# RefOsc10MHz_3V0_bga-escaped.net
KiCad netlist of a schematic drawn in EAGLE
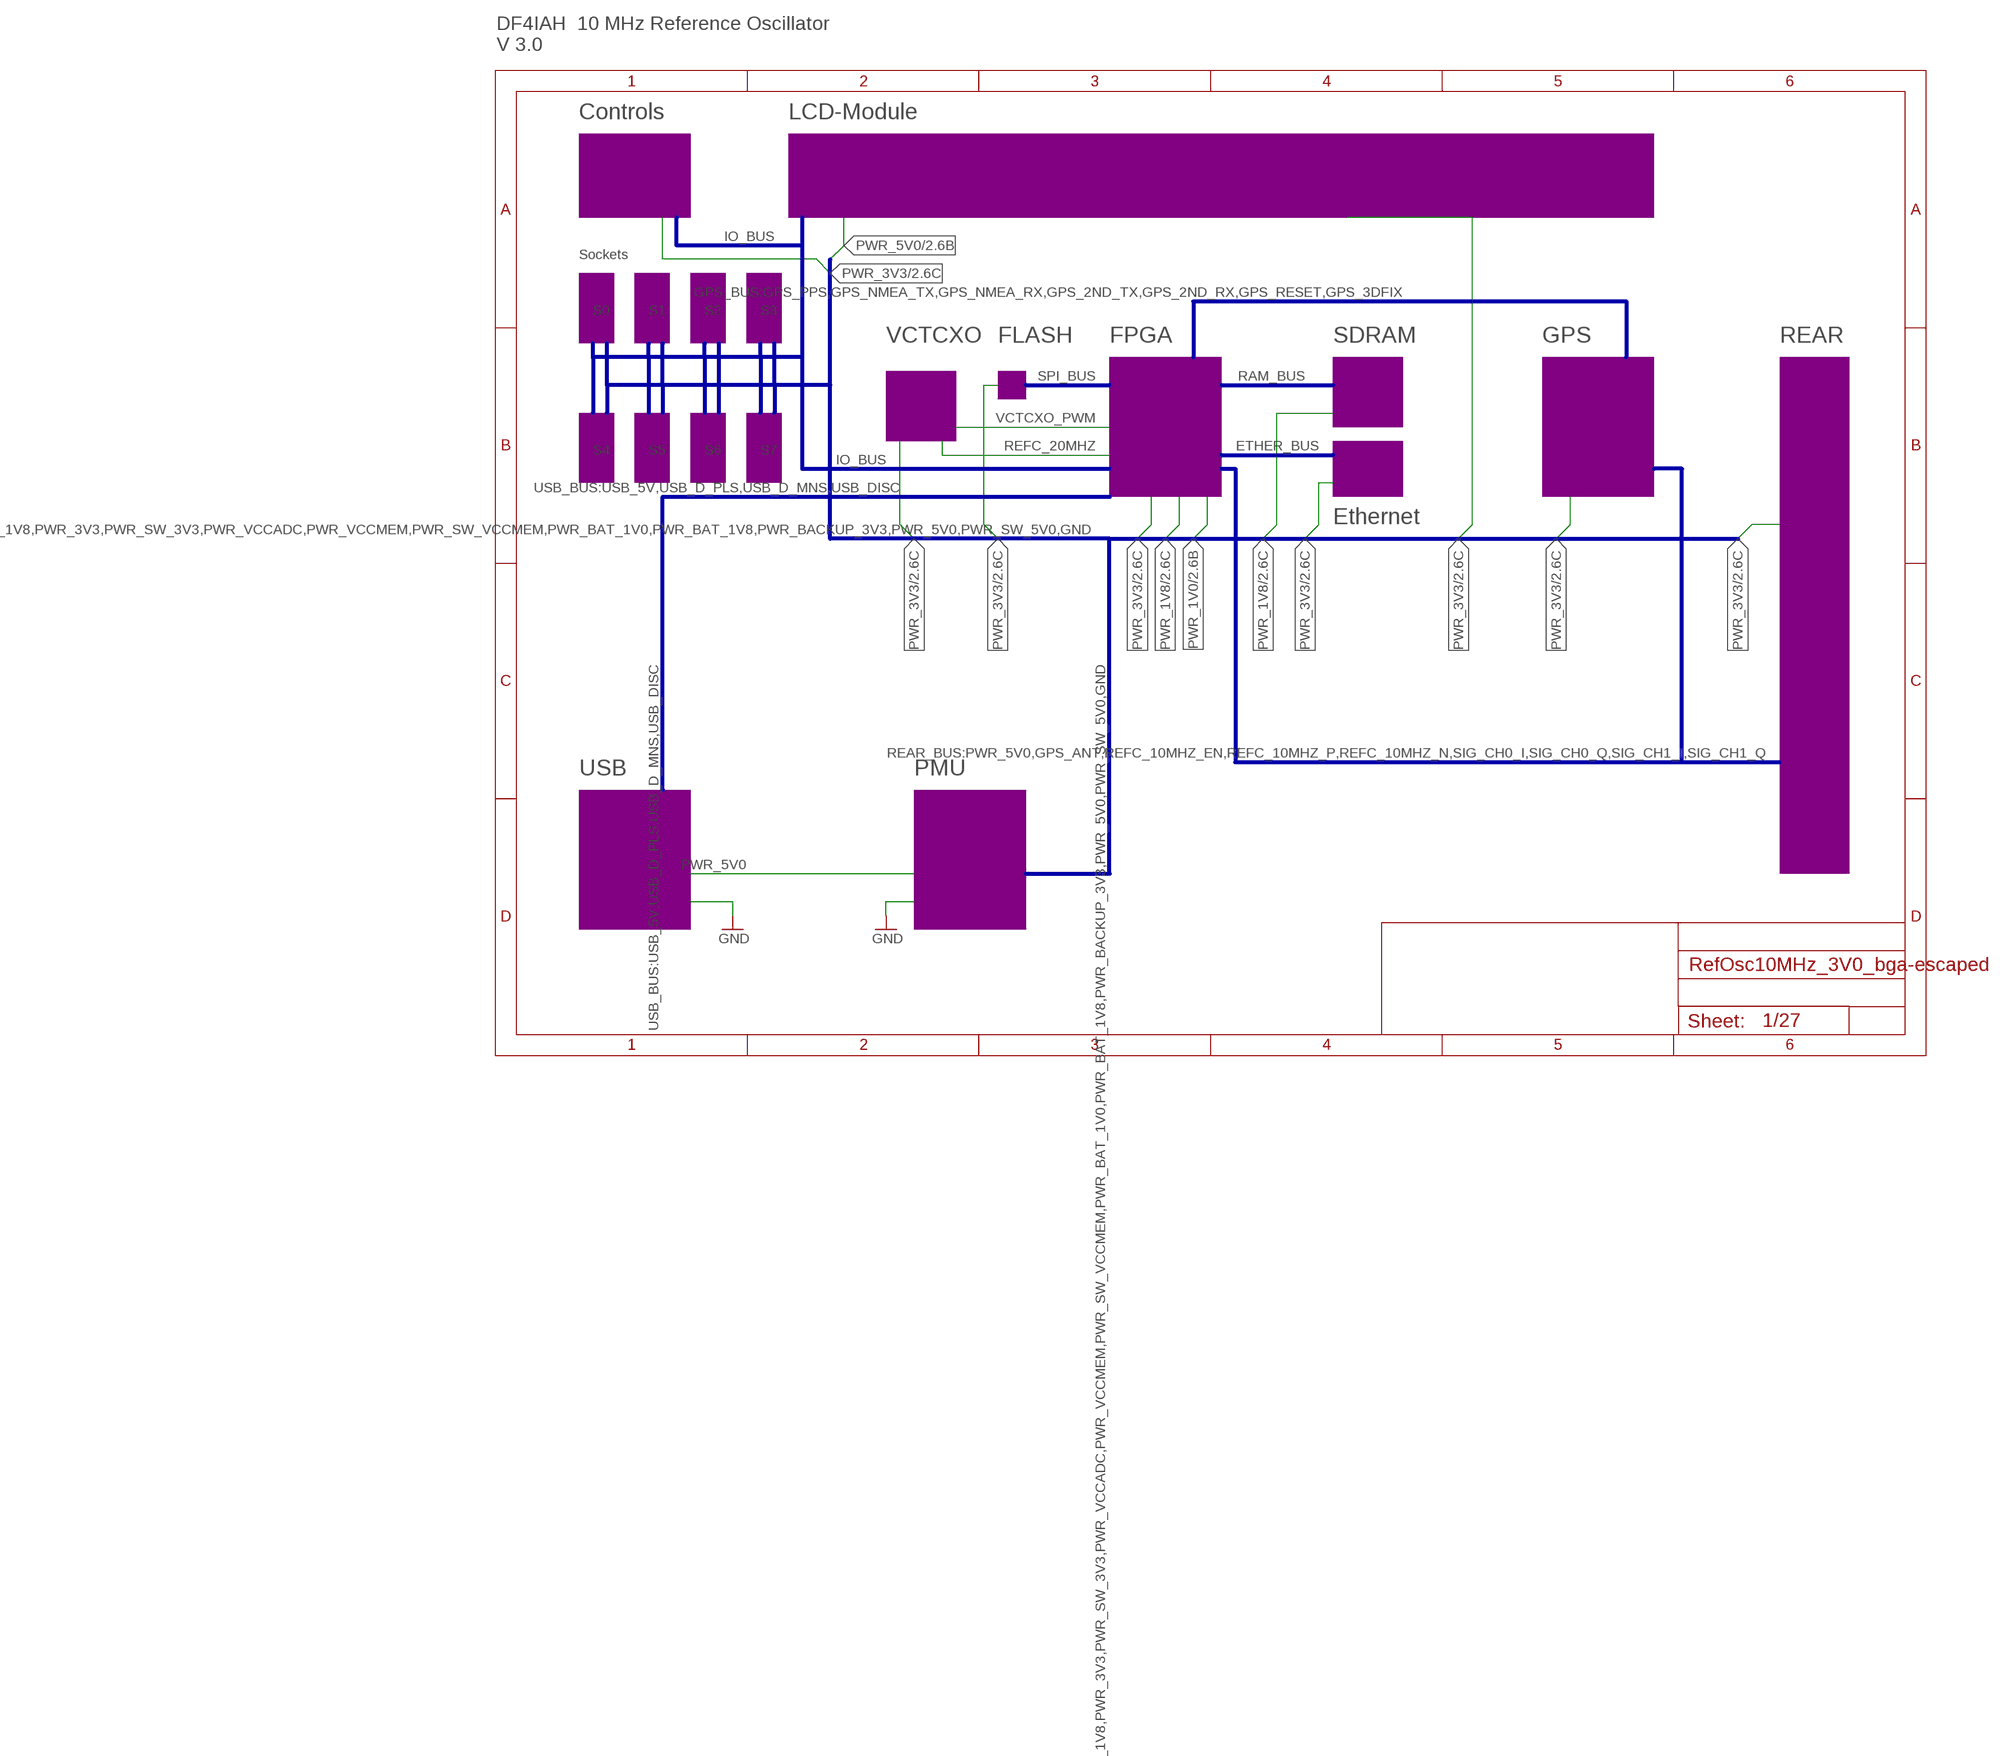
[diagram p0: schematic, sheet 1]
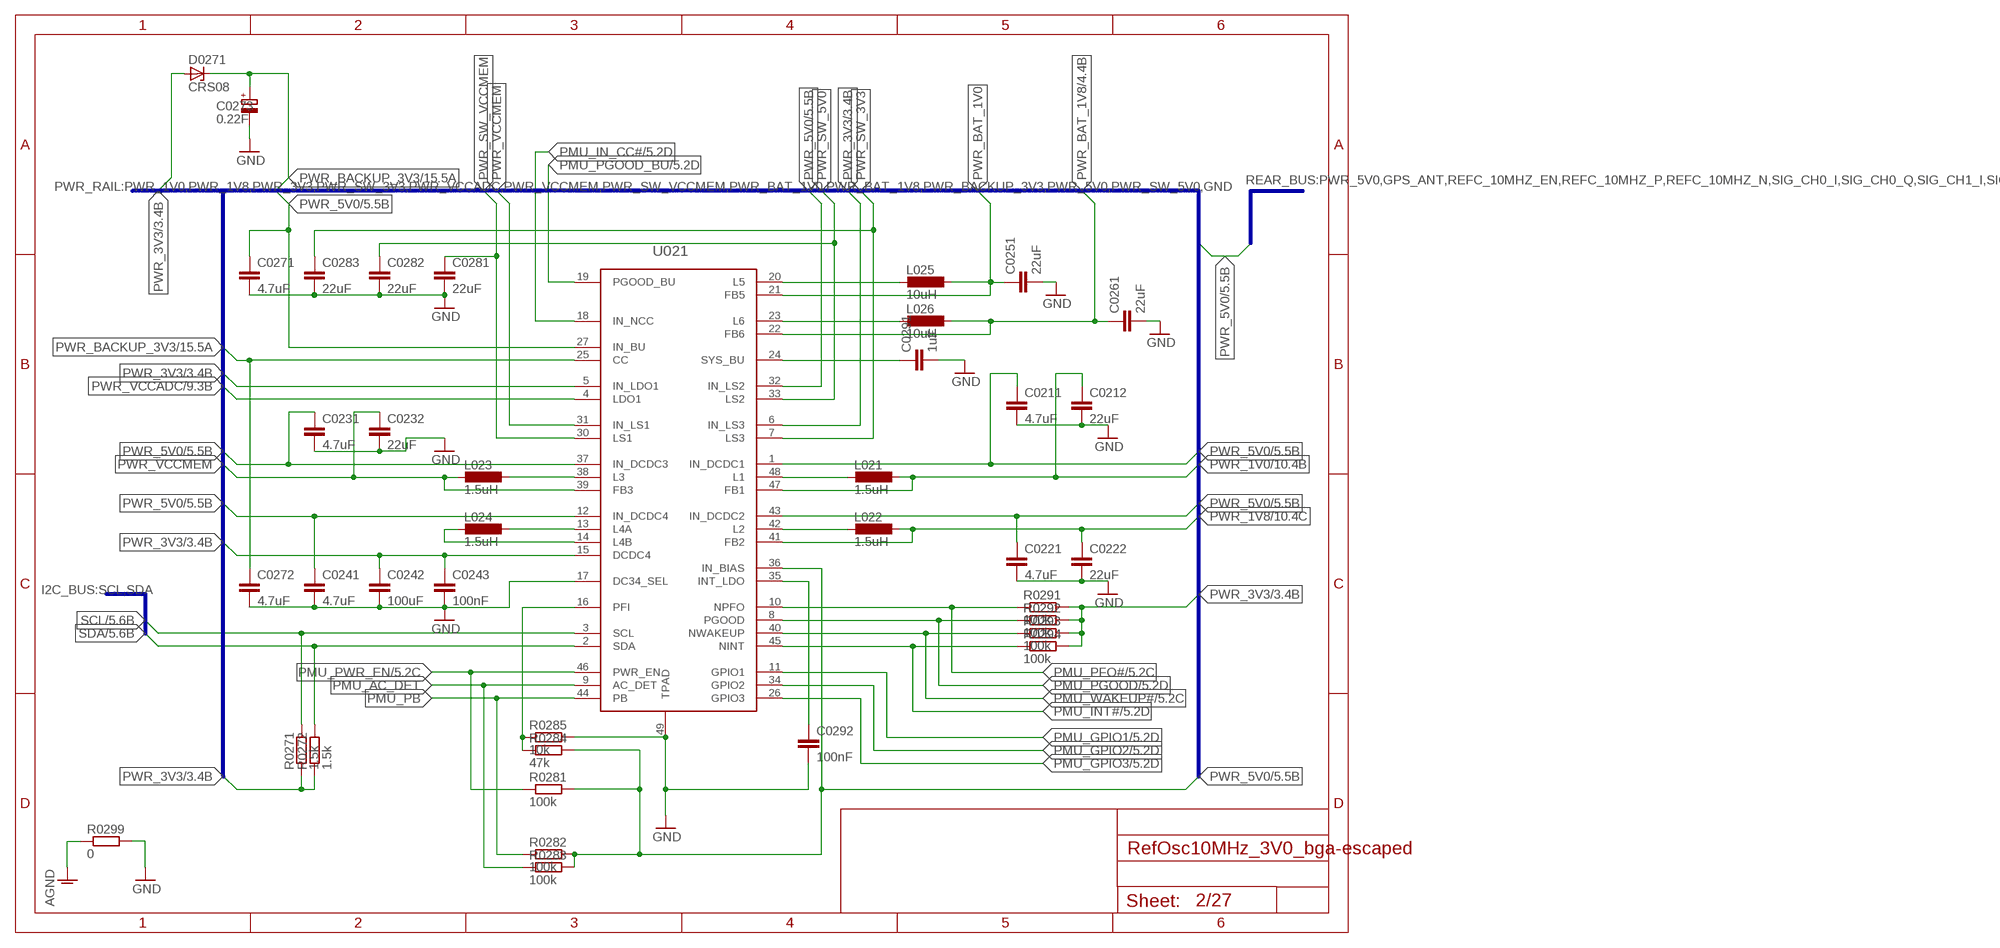
[diagram p1: schematic, sheet 2]
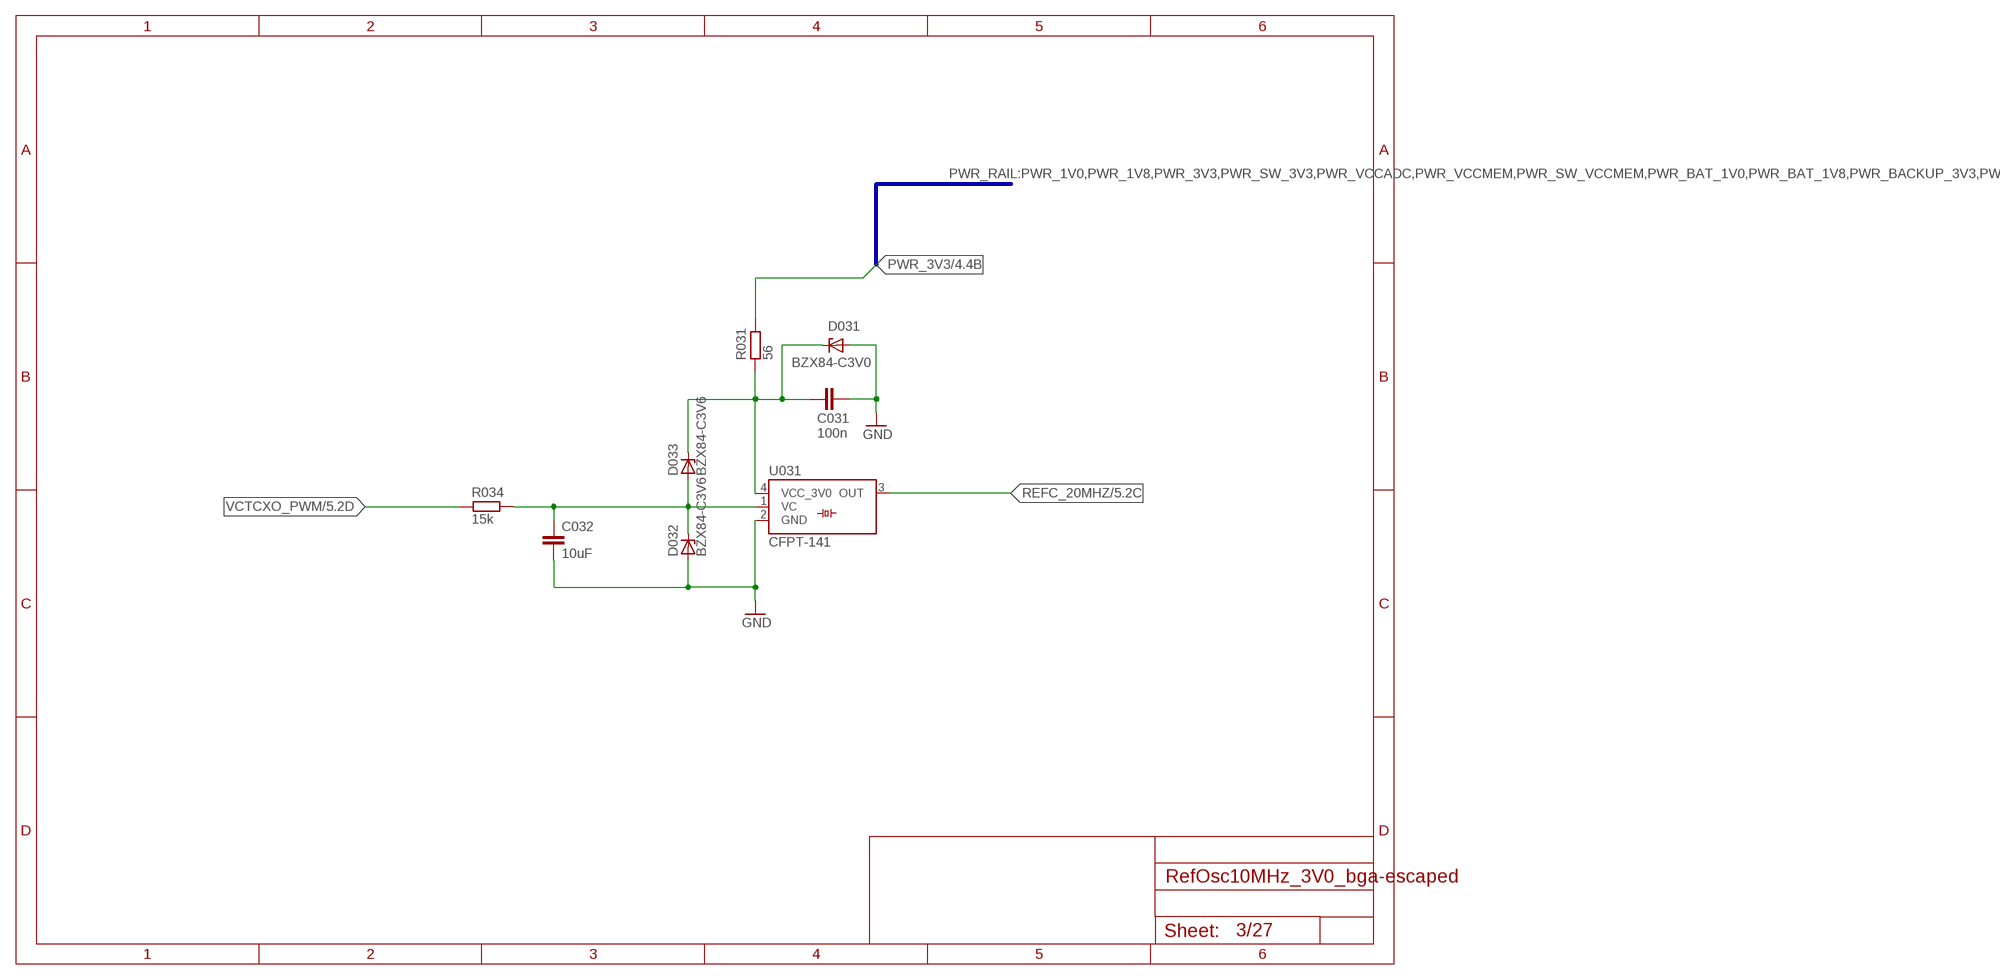
[diagram p2: schematic, sheet 3]
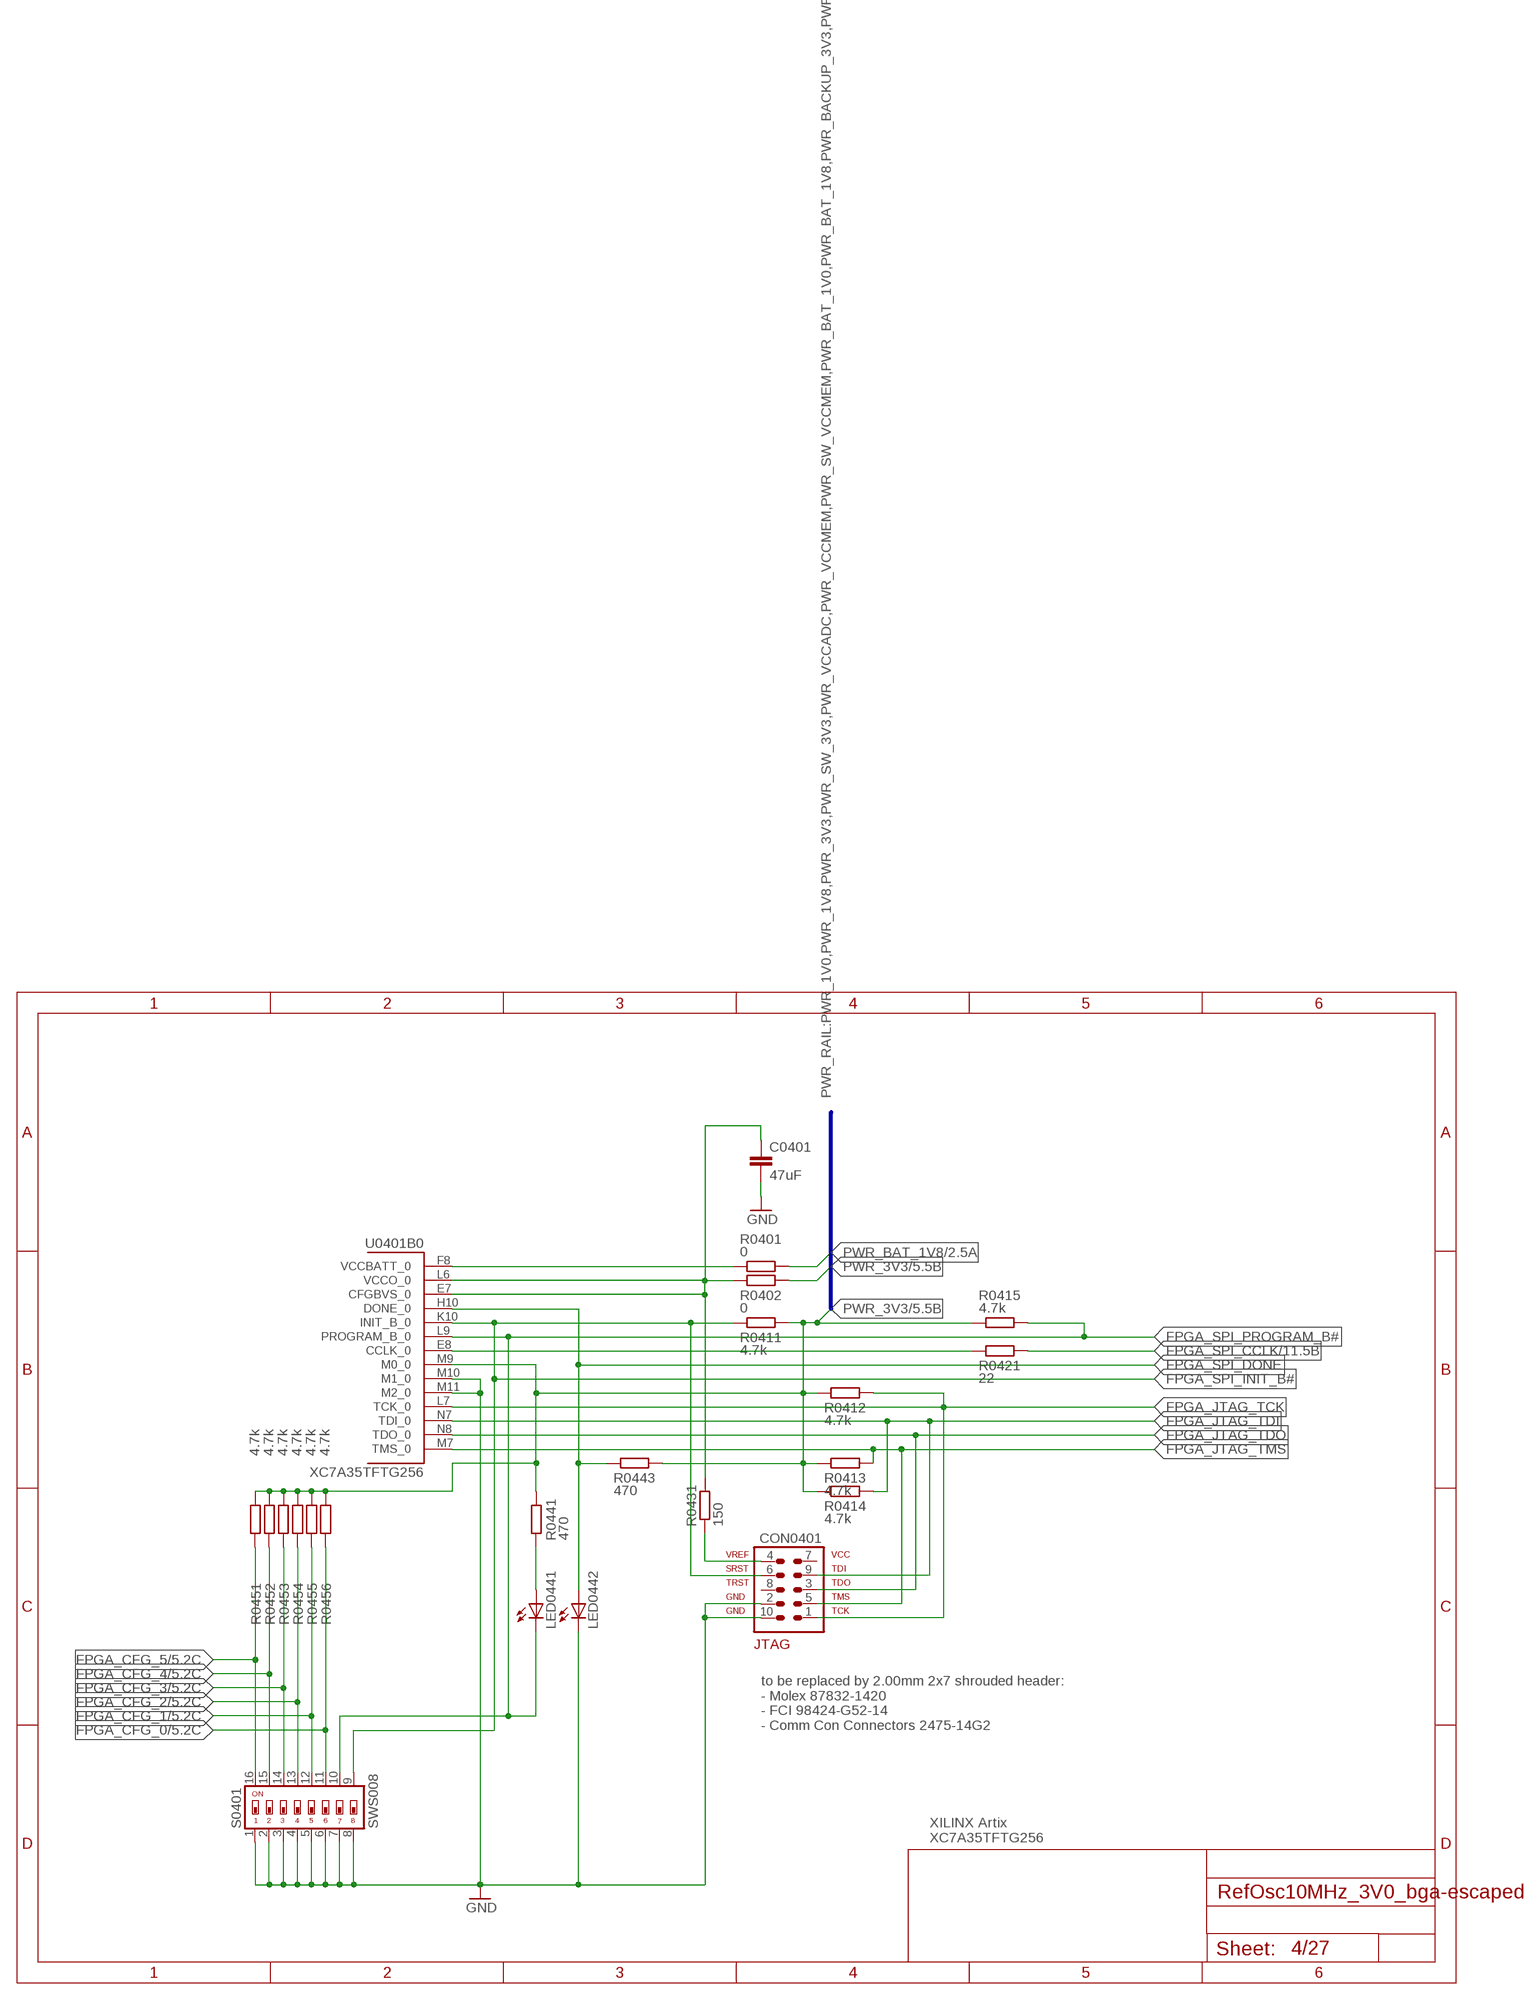
[diagram p3: schematic, sheet 4]
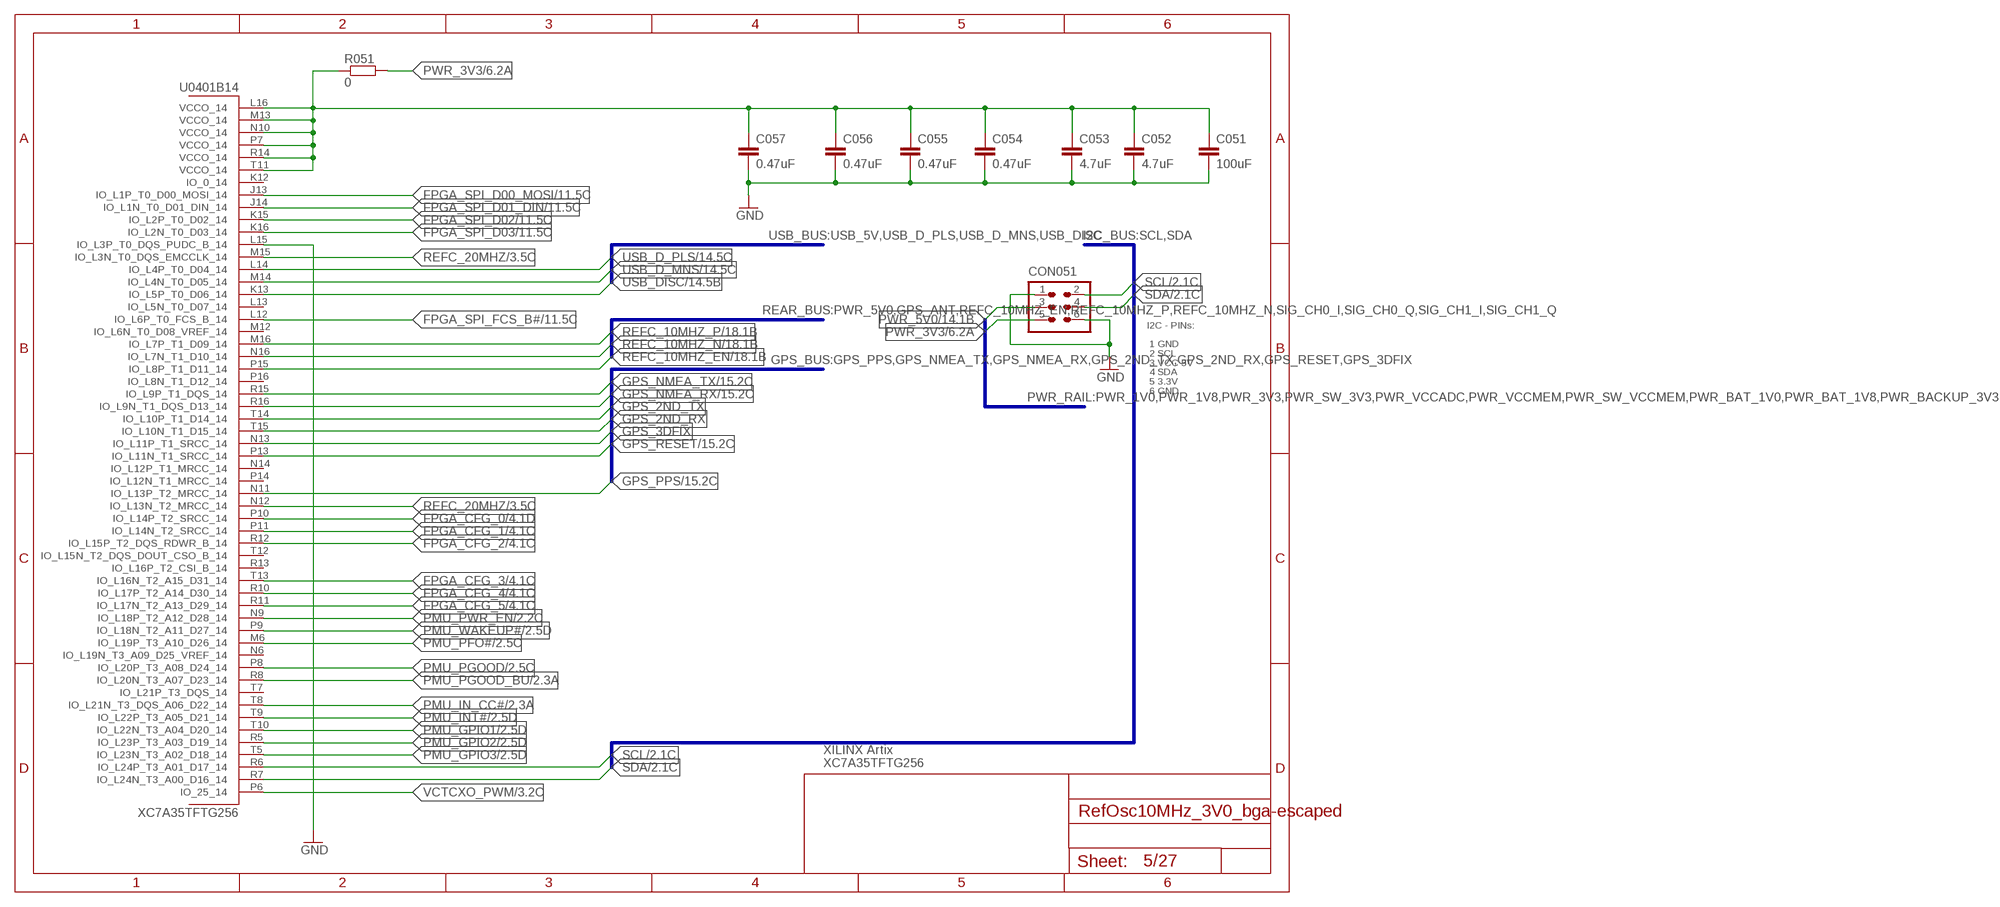
[diagram p4: schematic, sheet 5]
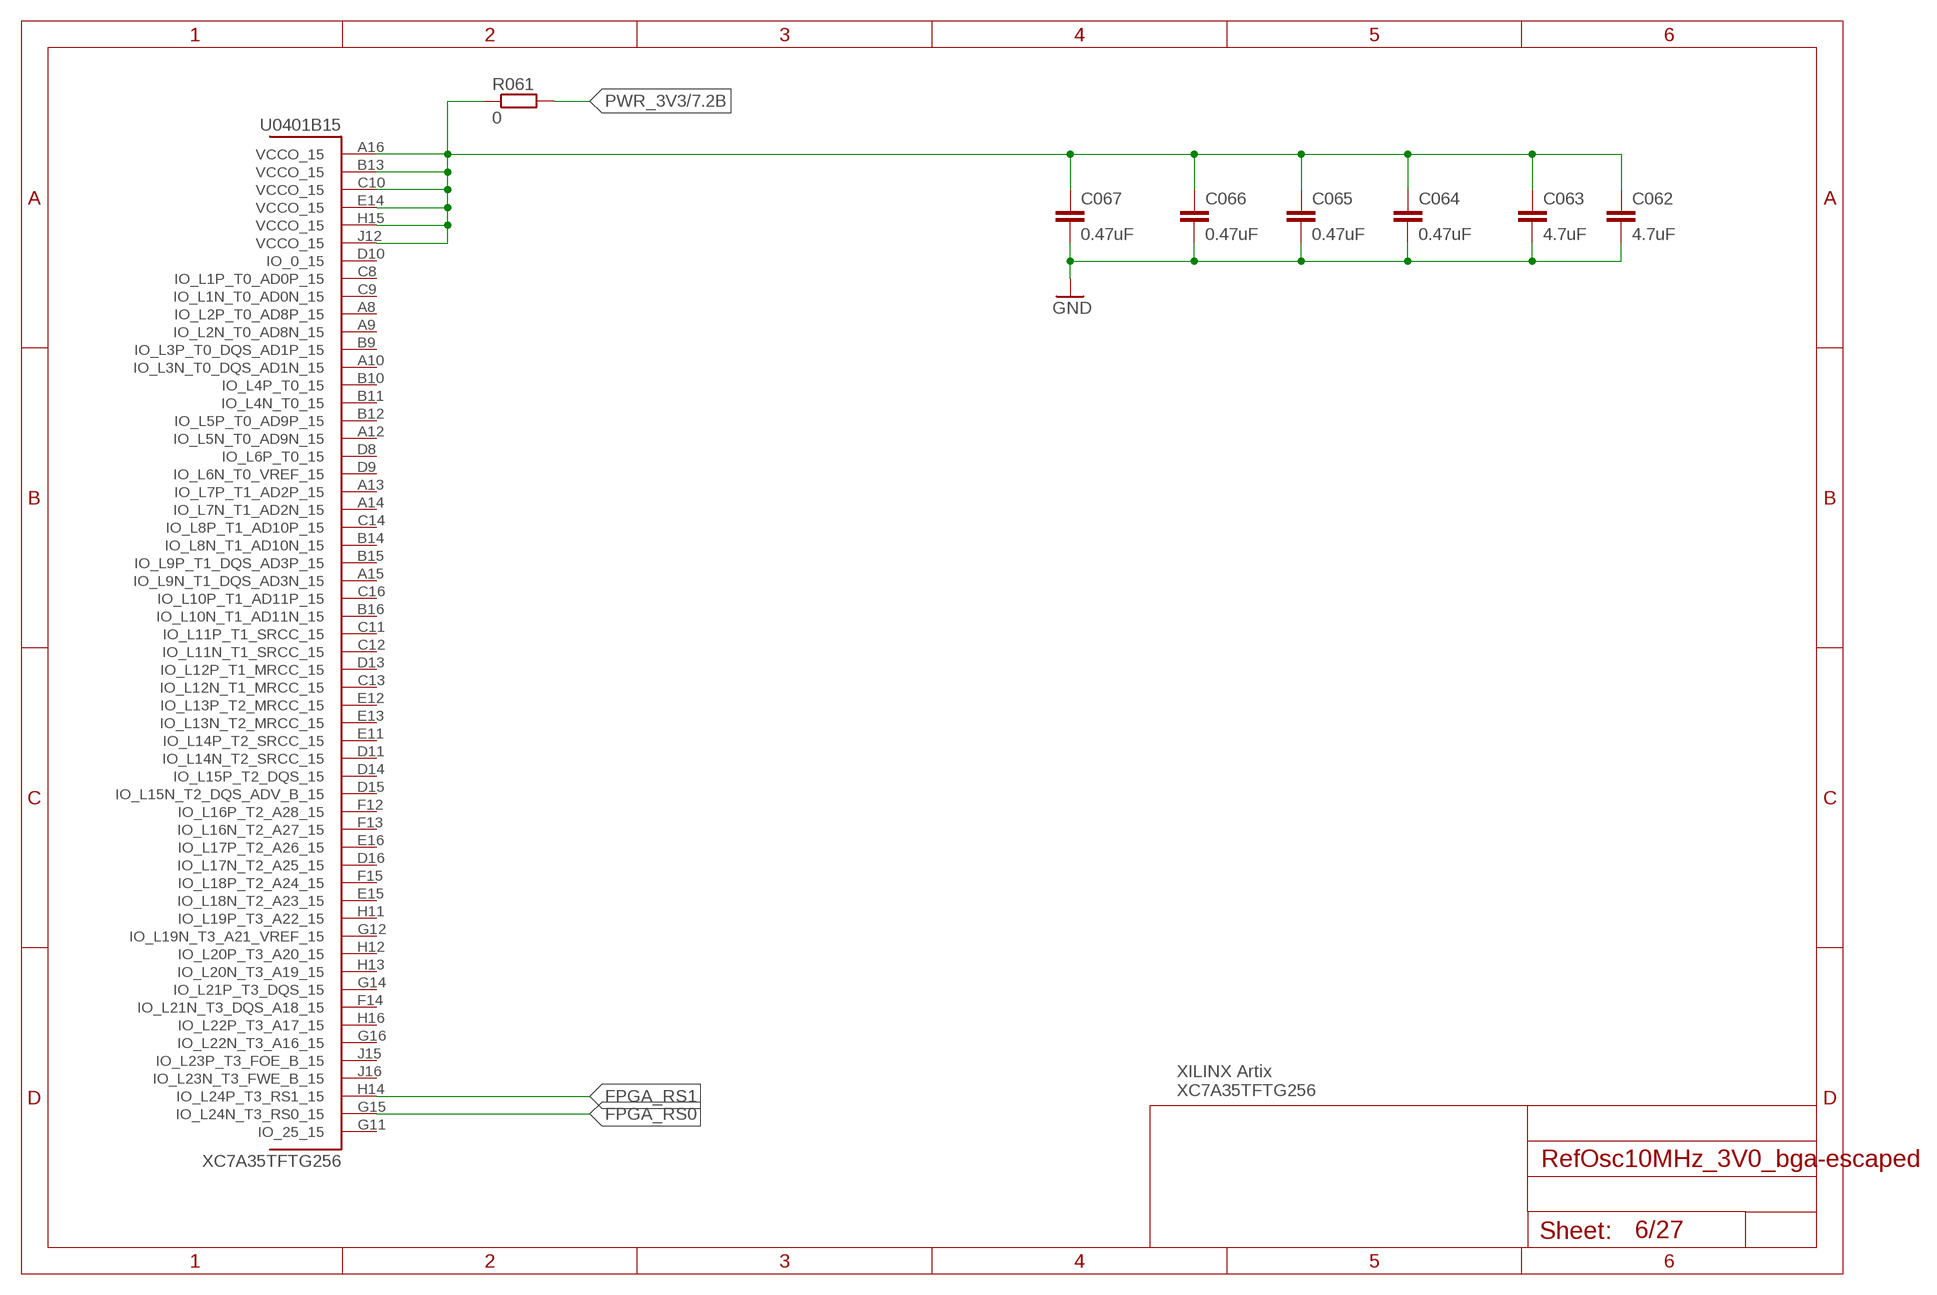
[diagram p5: schematic, sheet 6]
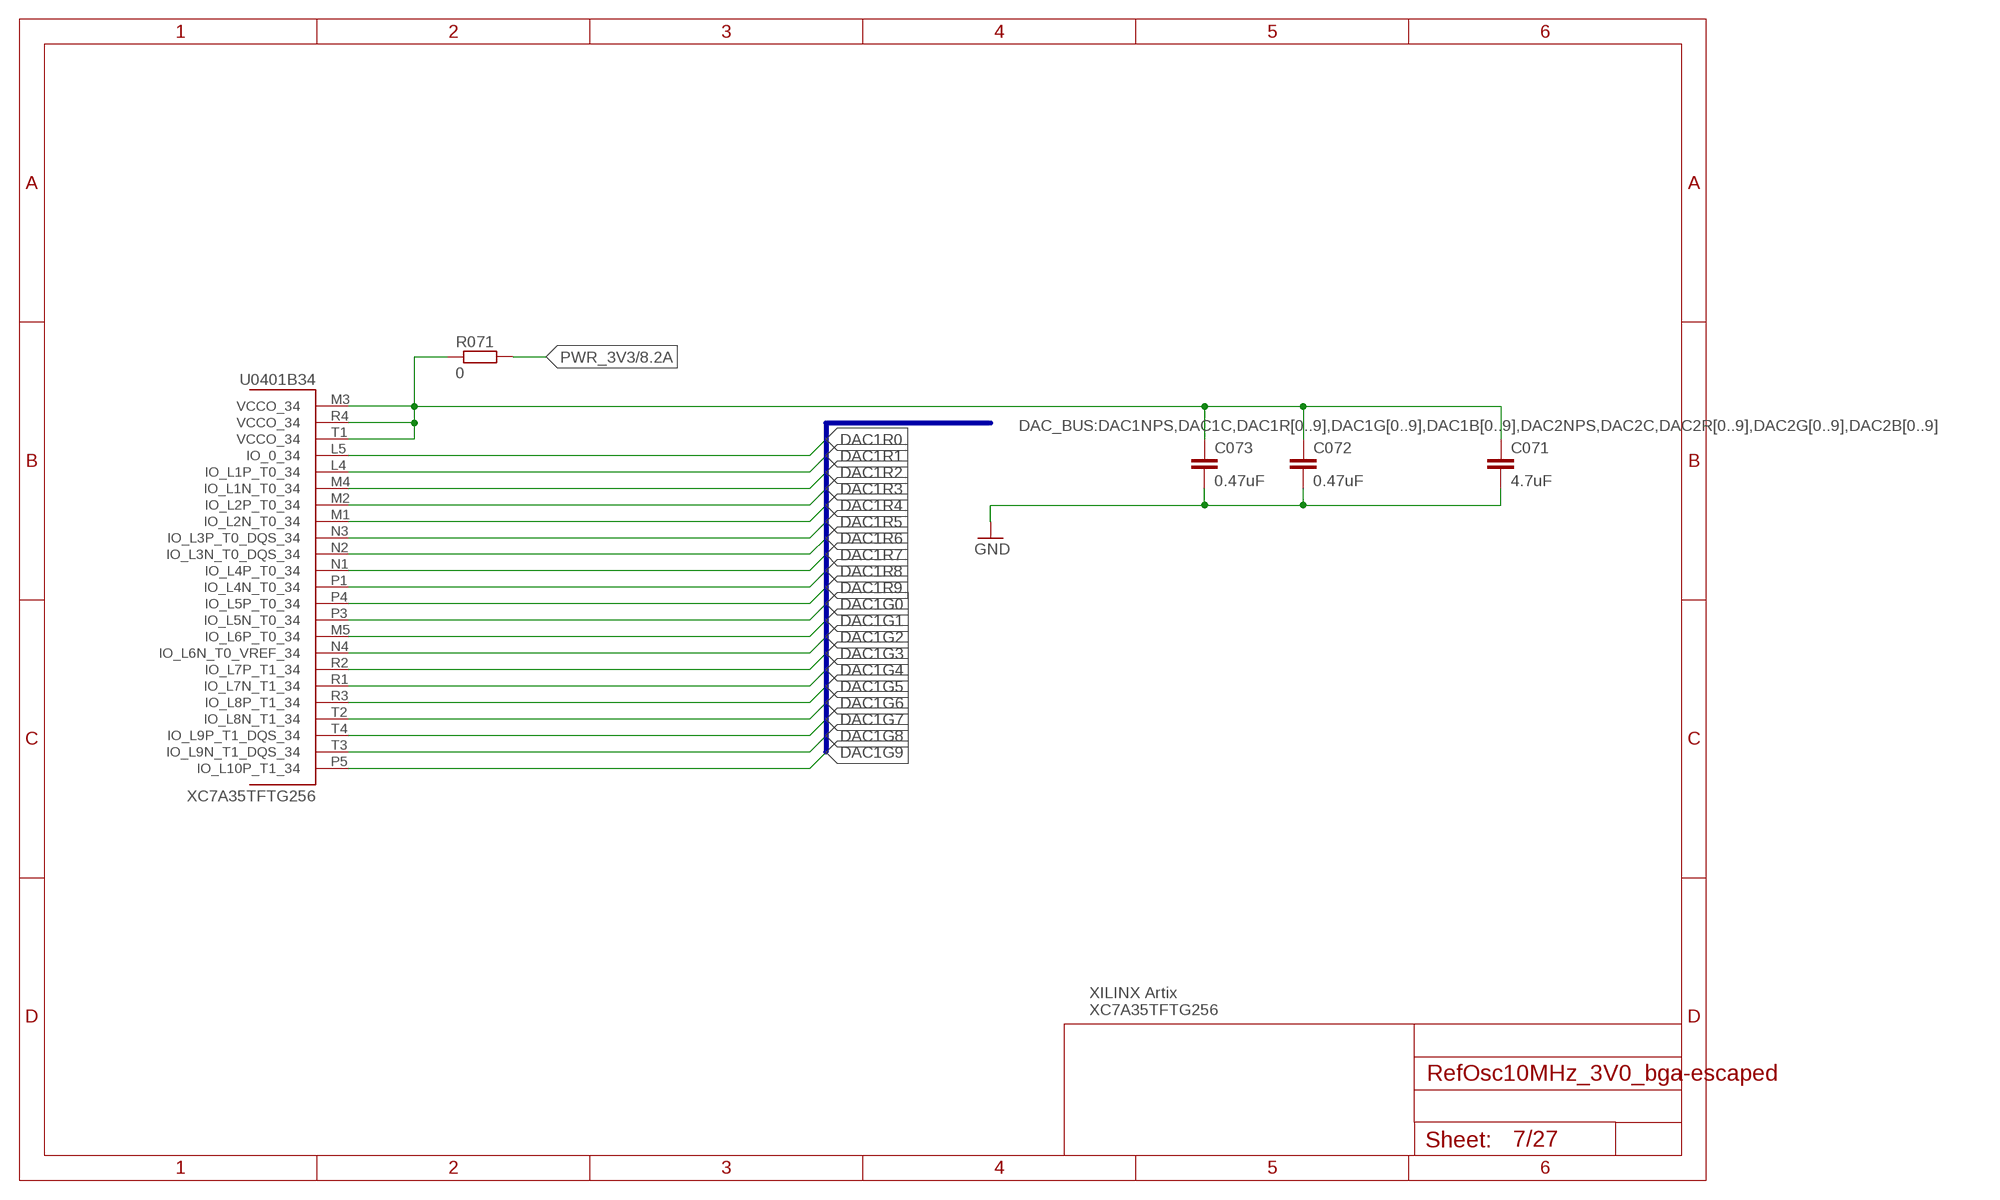
[diagram p6: schematic, sheet 7]
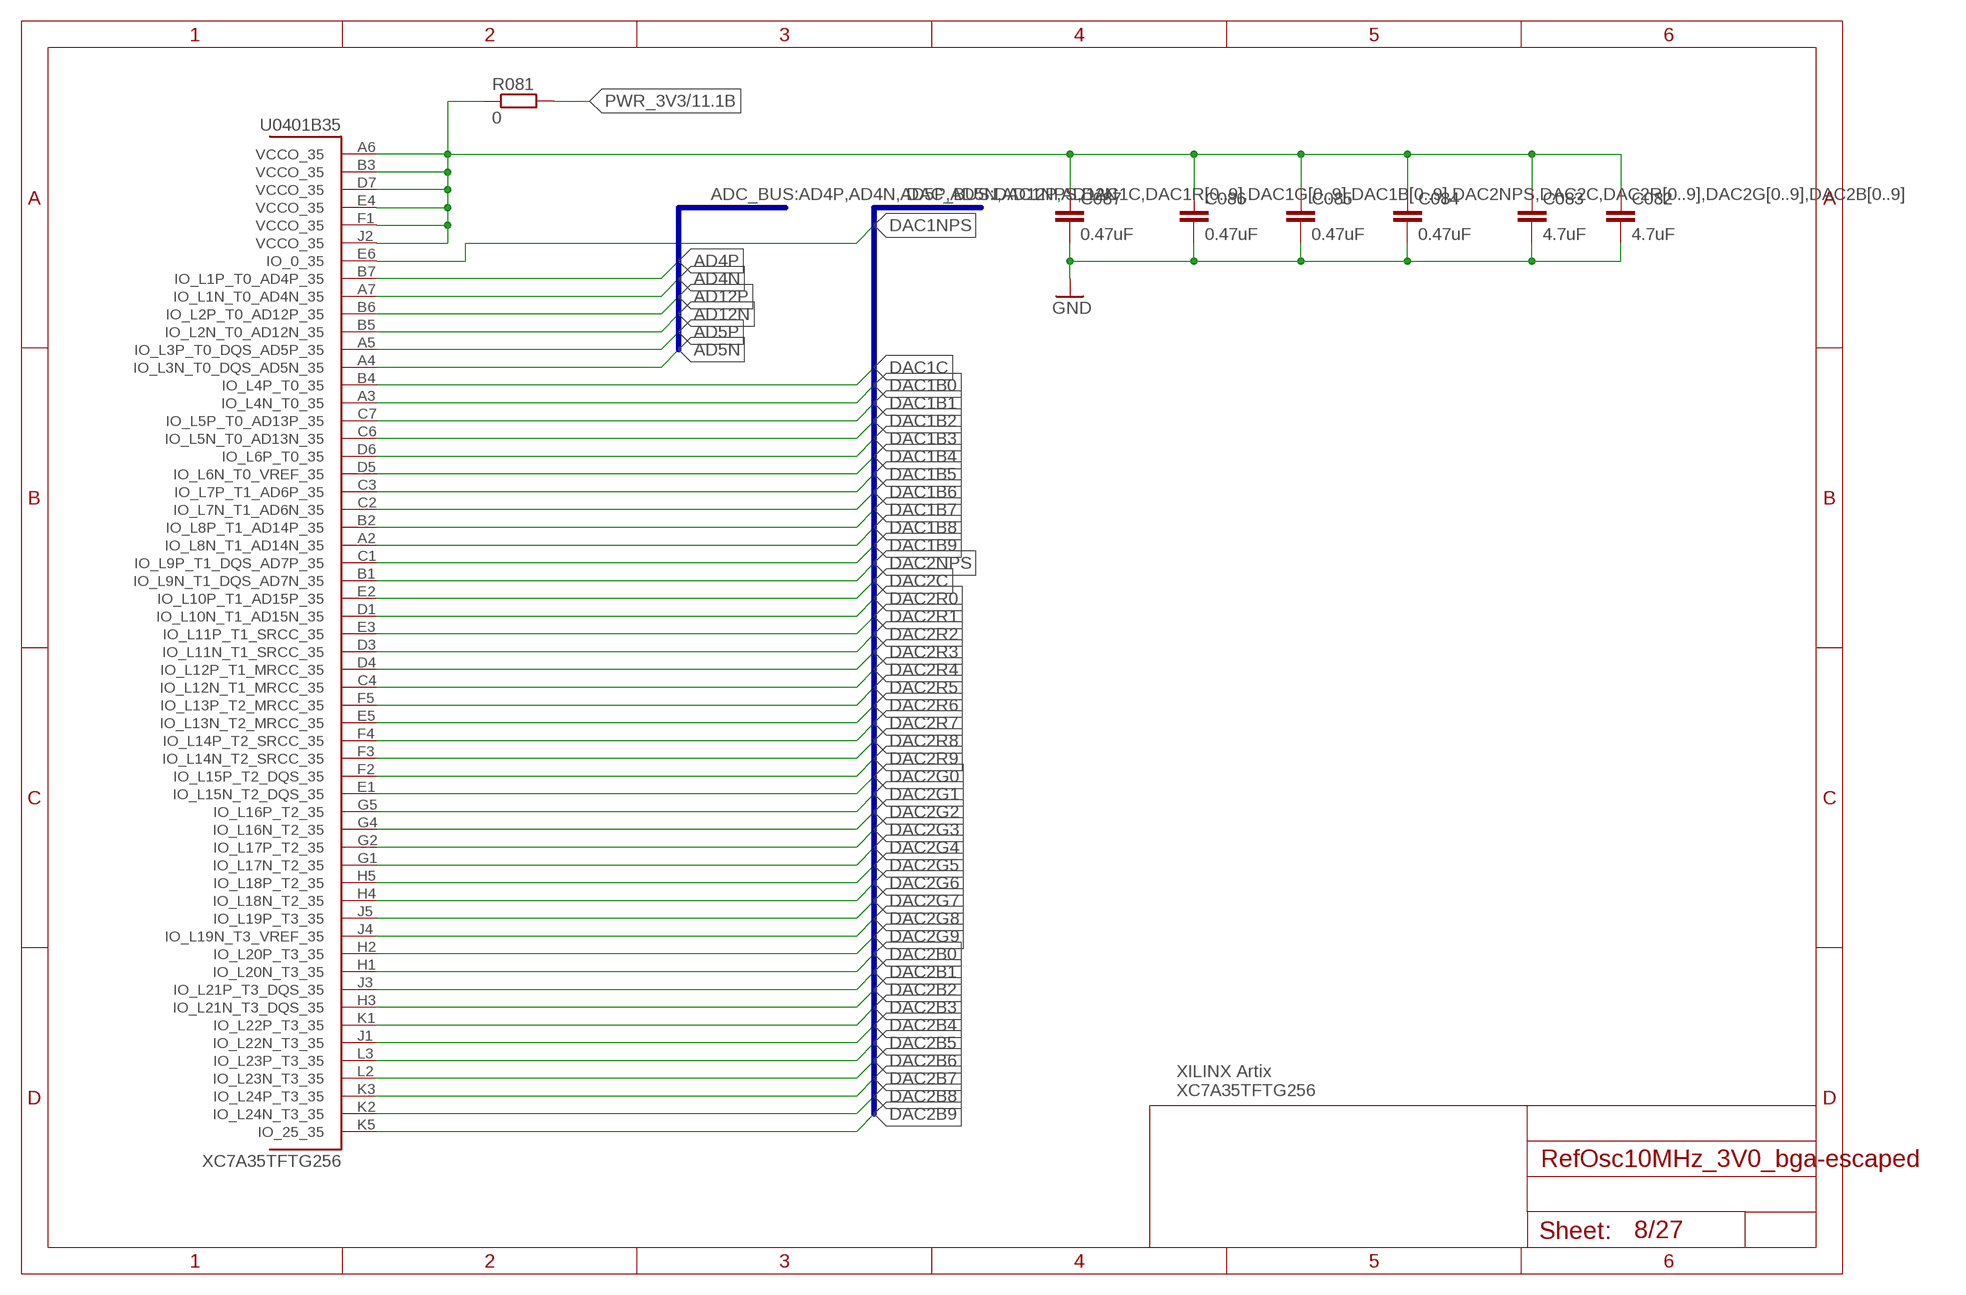
[diagram p7: schematic, sheet 8]
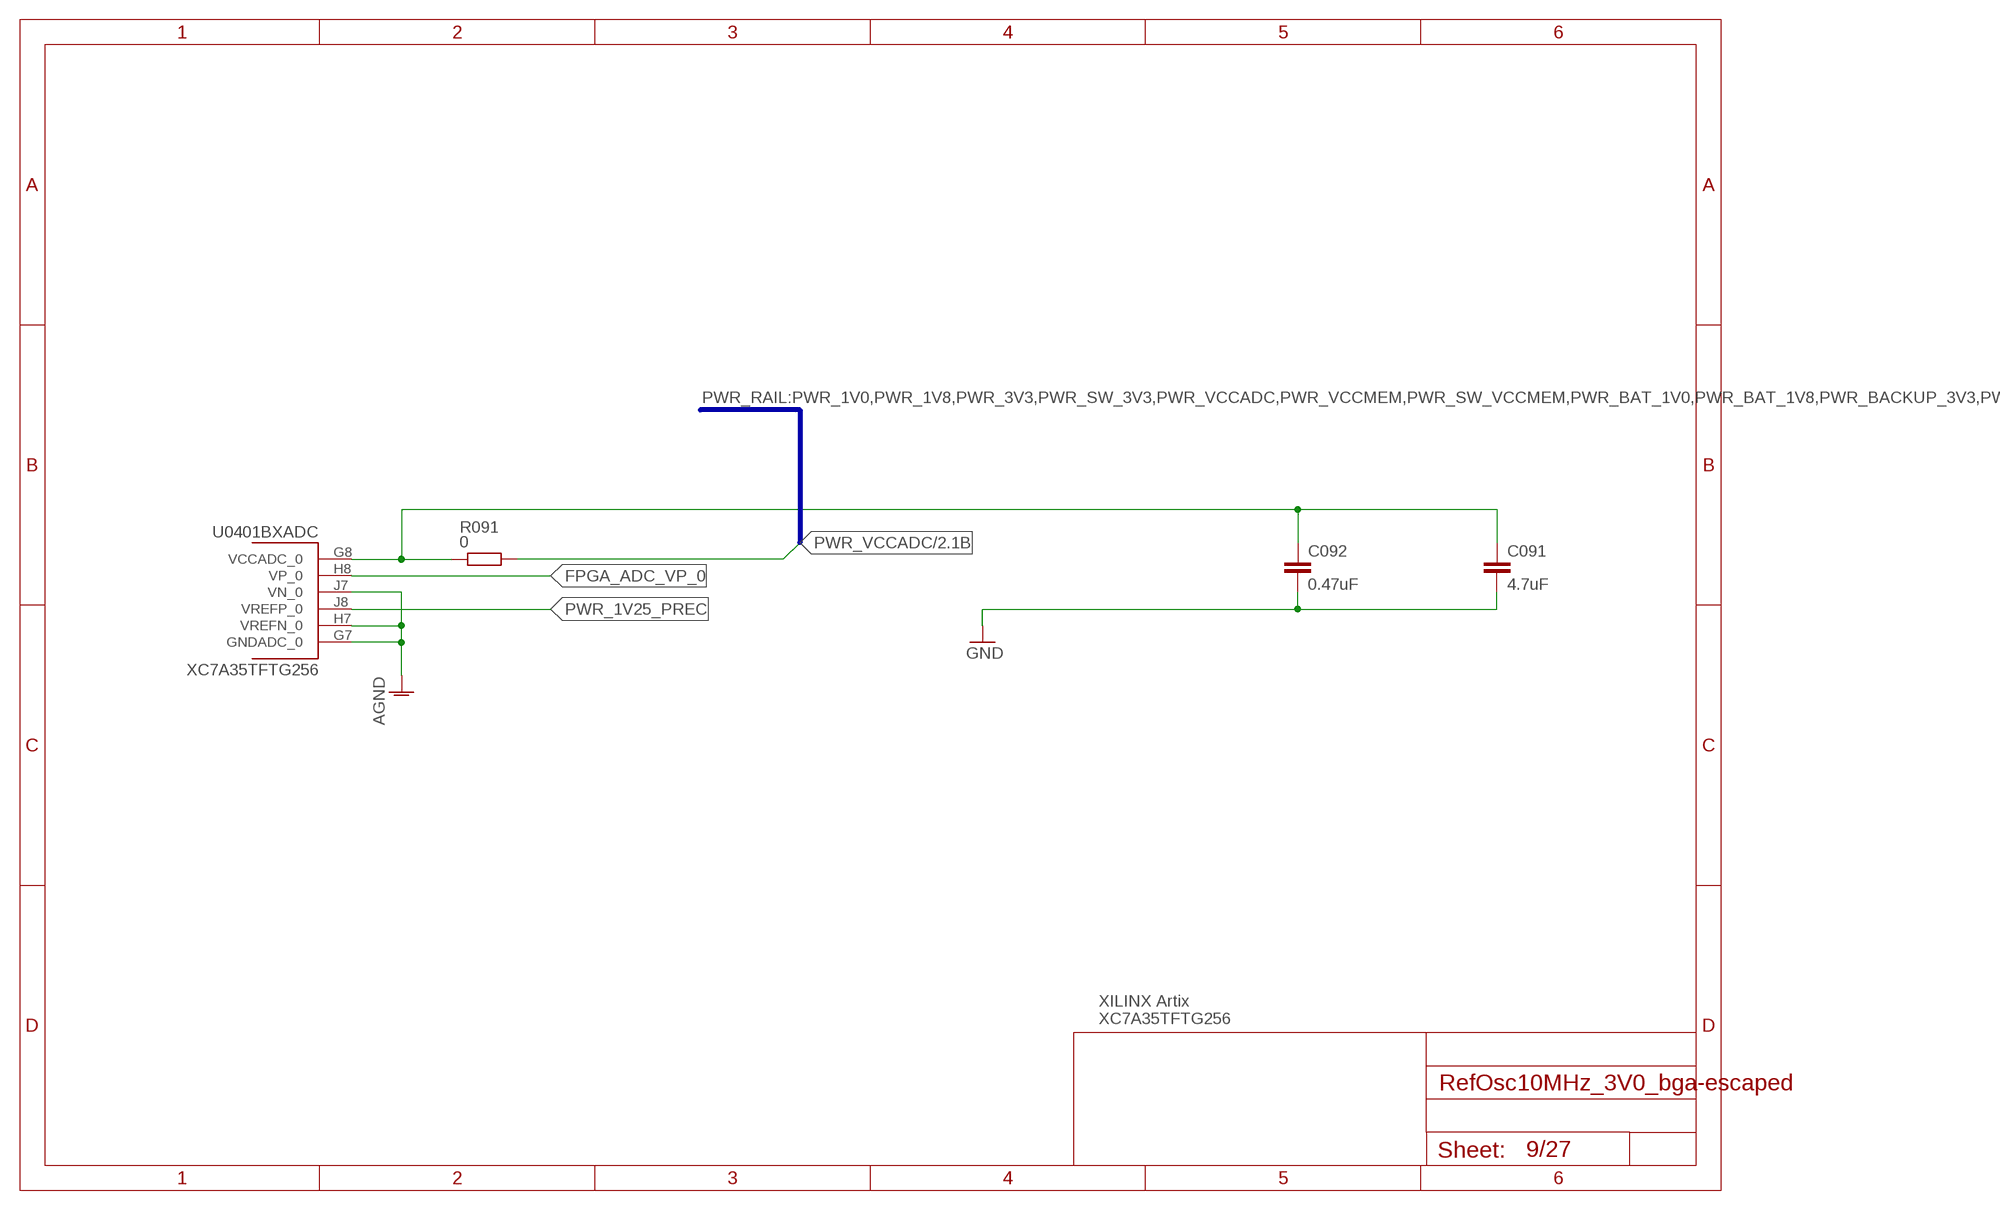
[diagram p8: schematic, sheet 9]
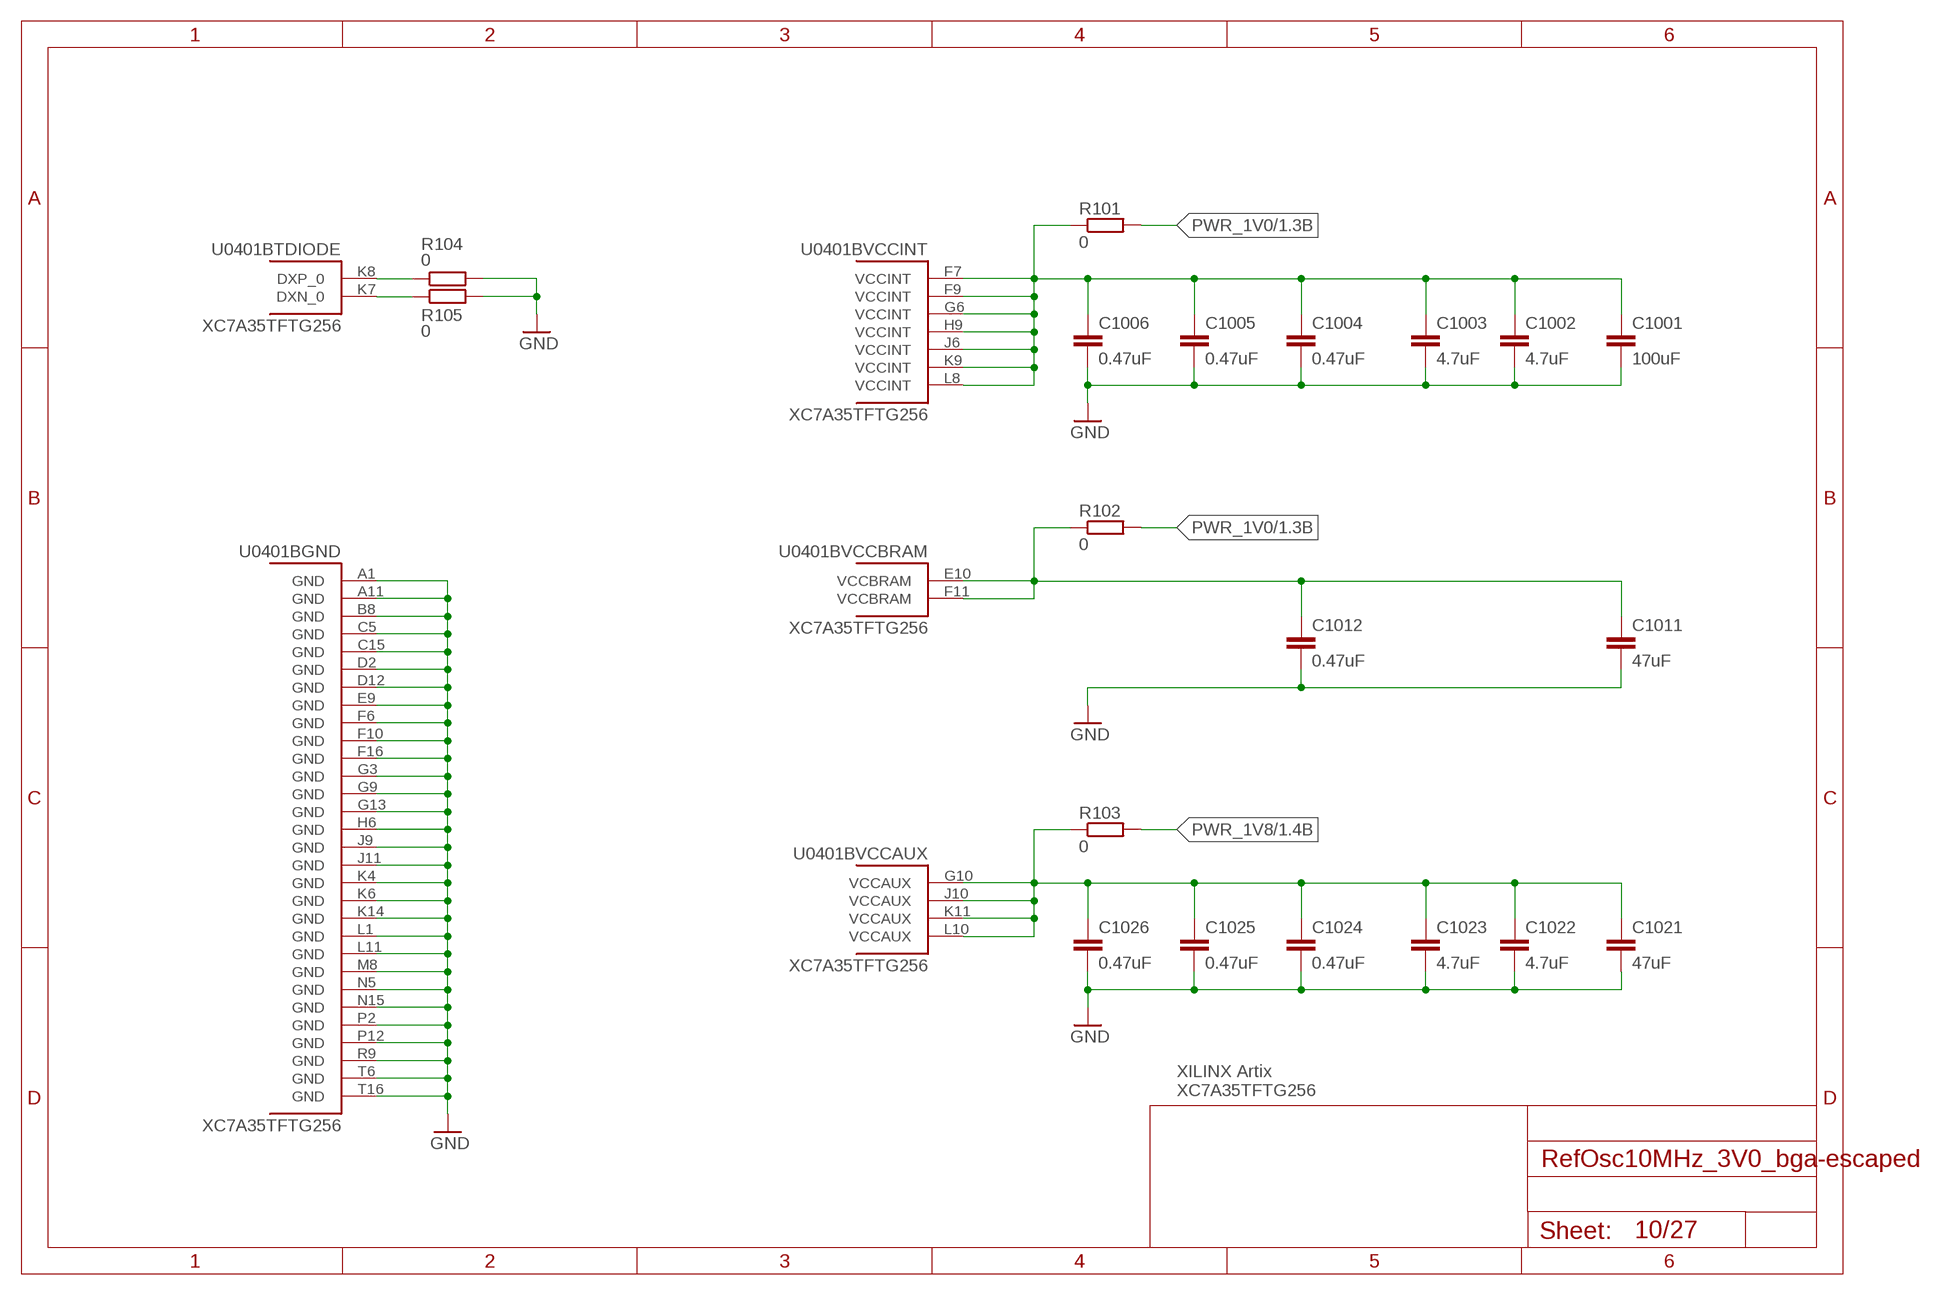
[diagram p9: schematic, sheet 10]
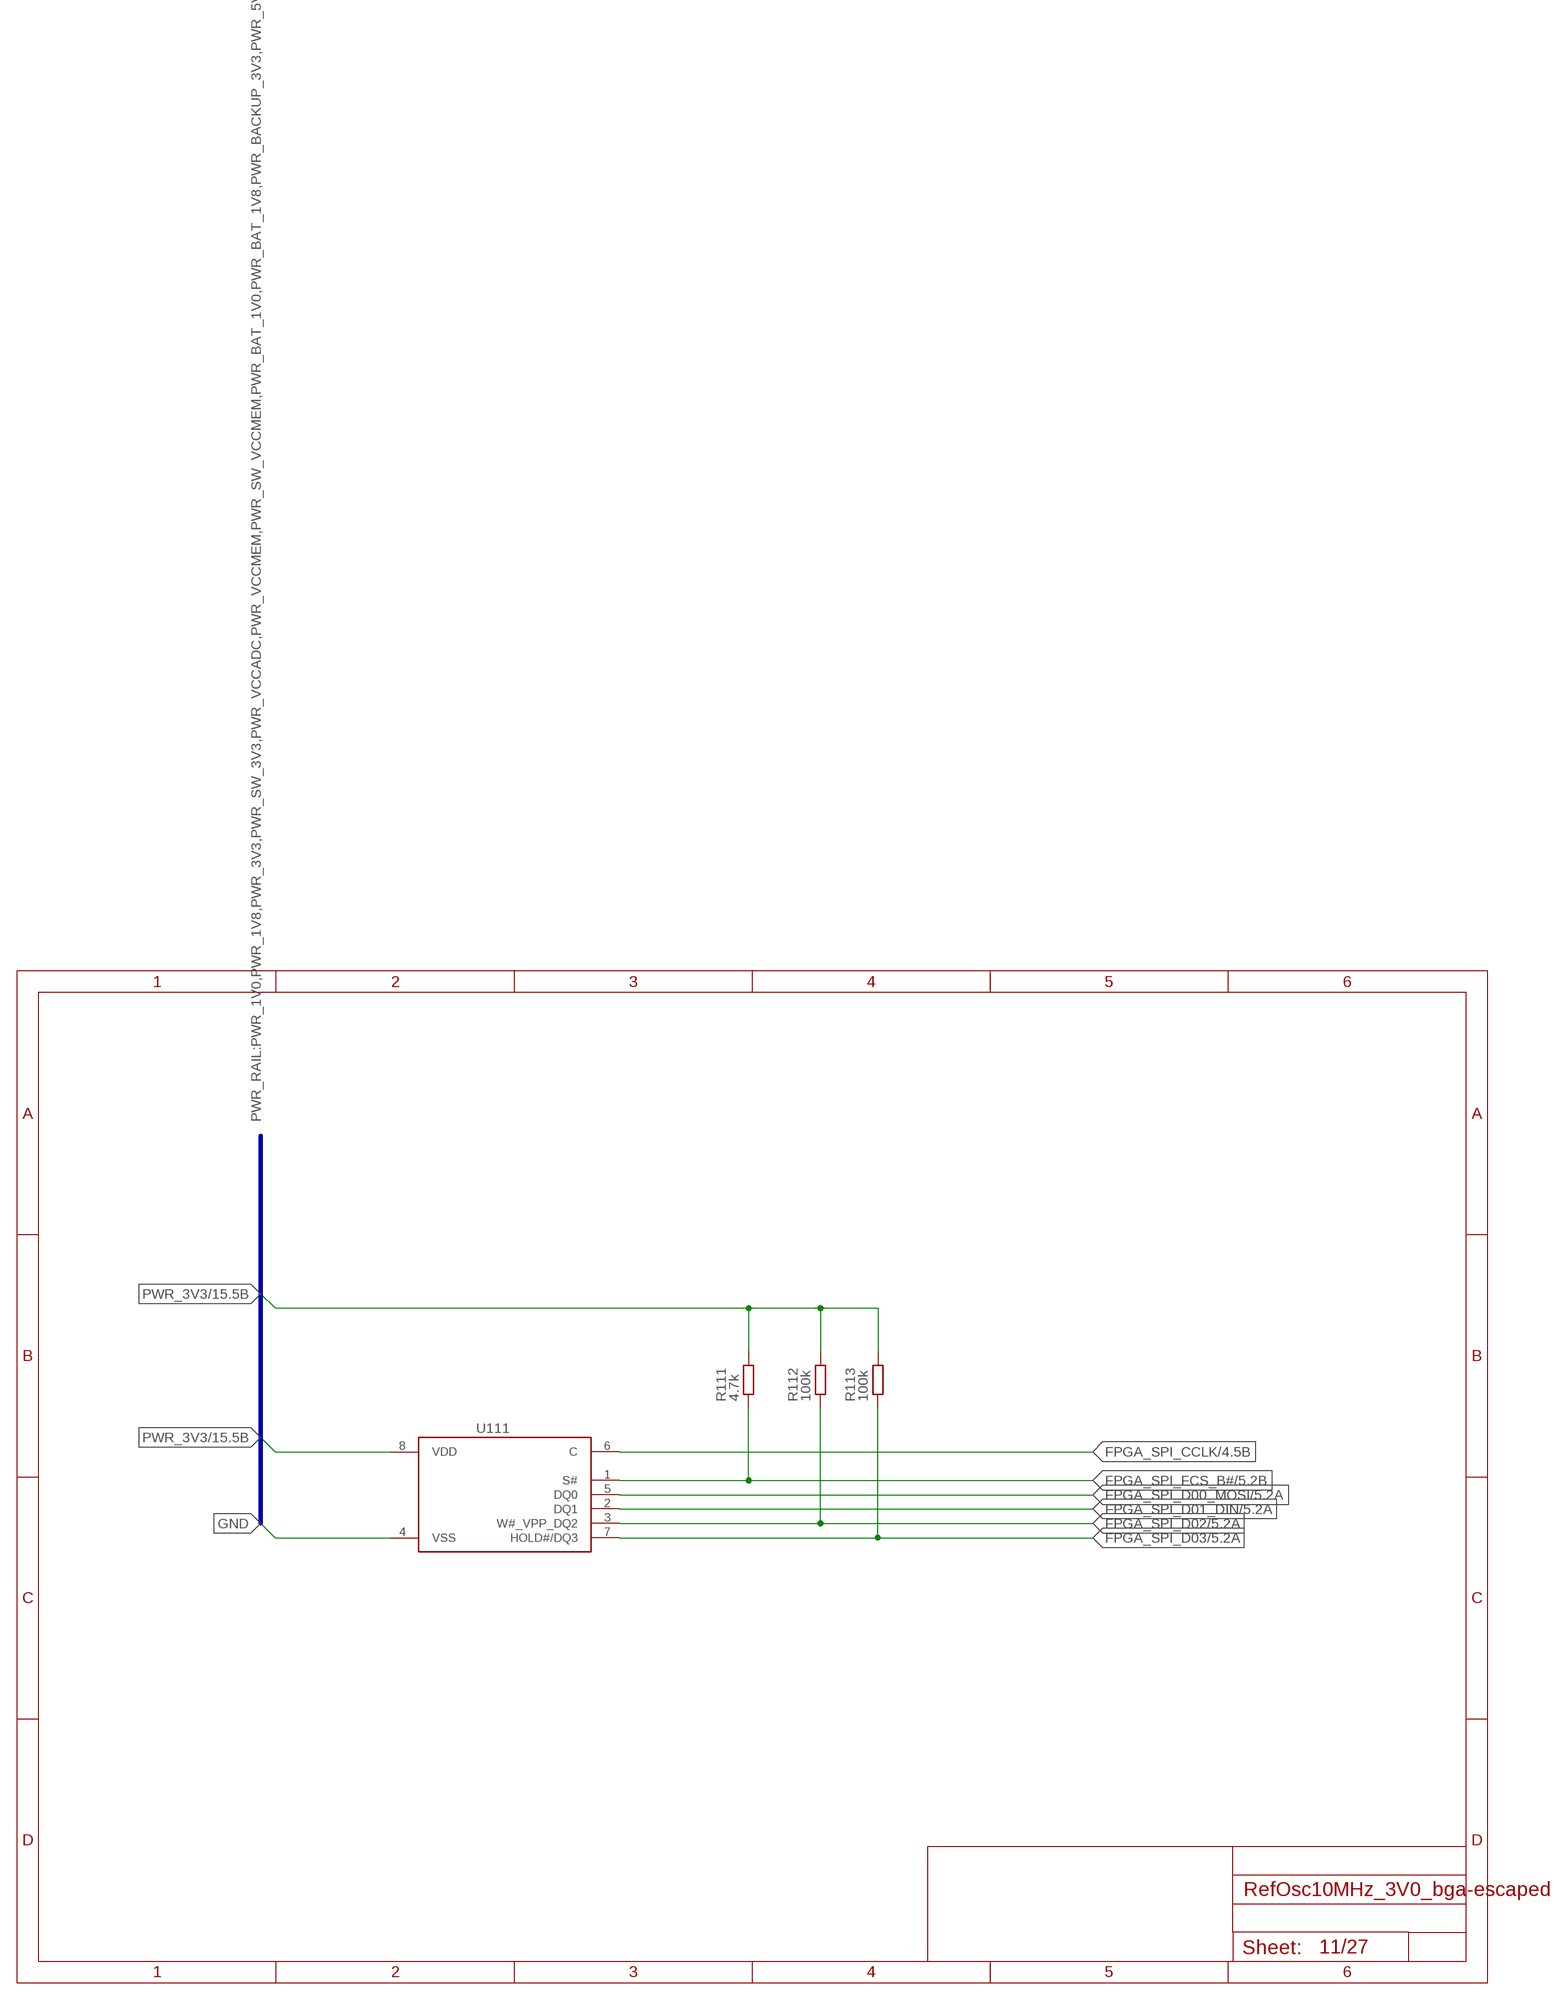
[diagram p10: schematic, sheet 11]
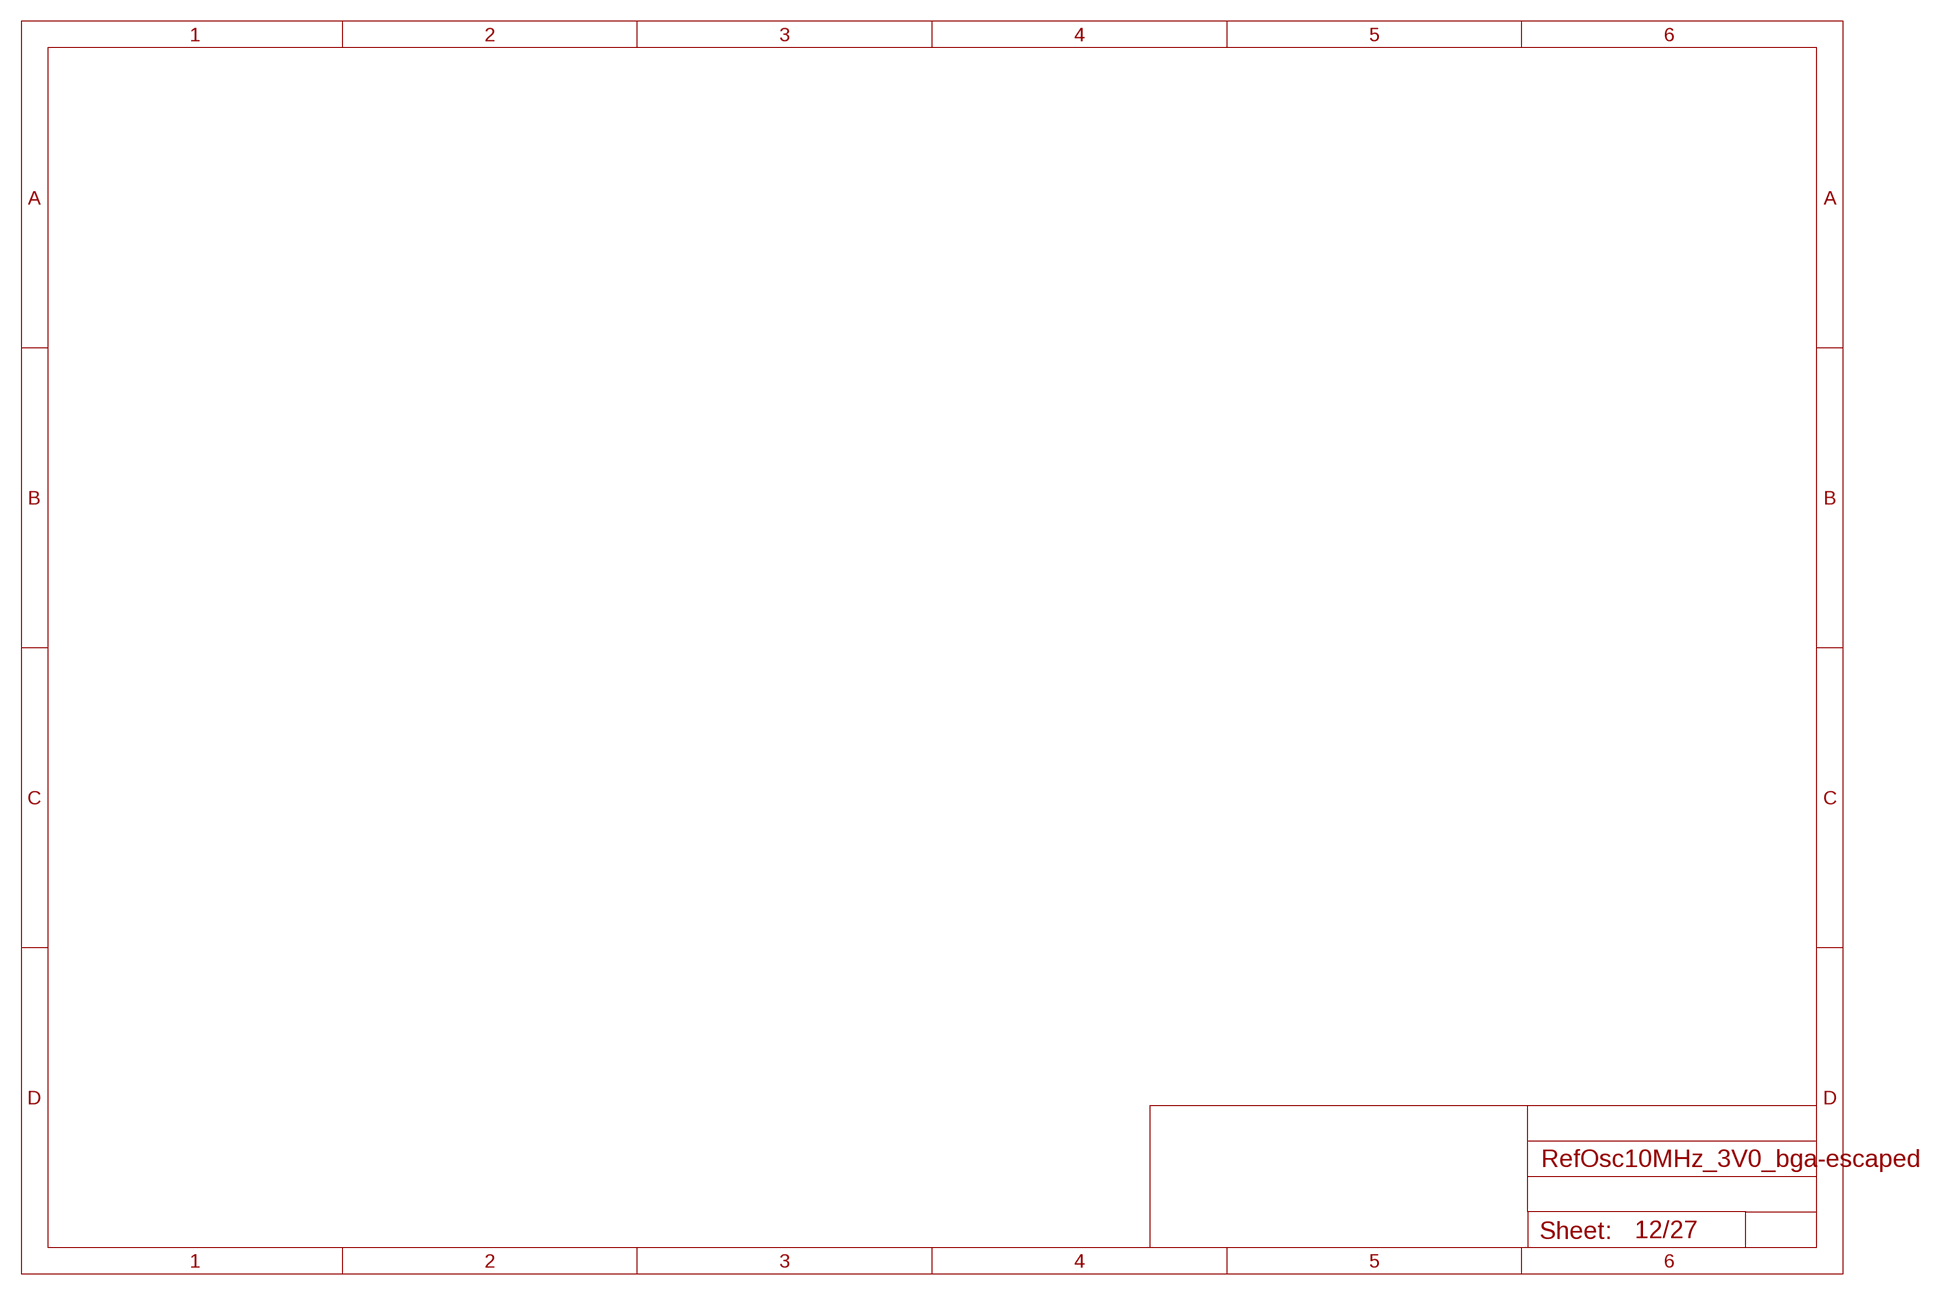
[diagram p11: schematic, sheet 12]
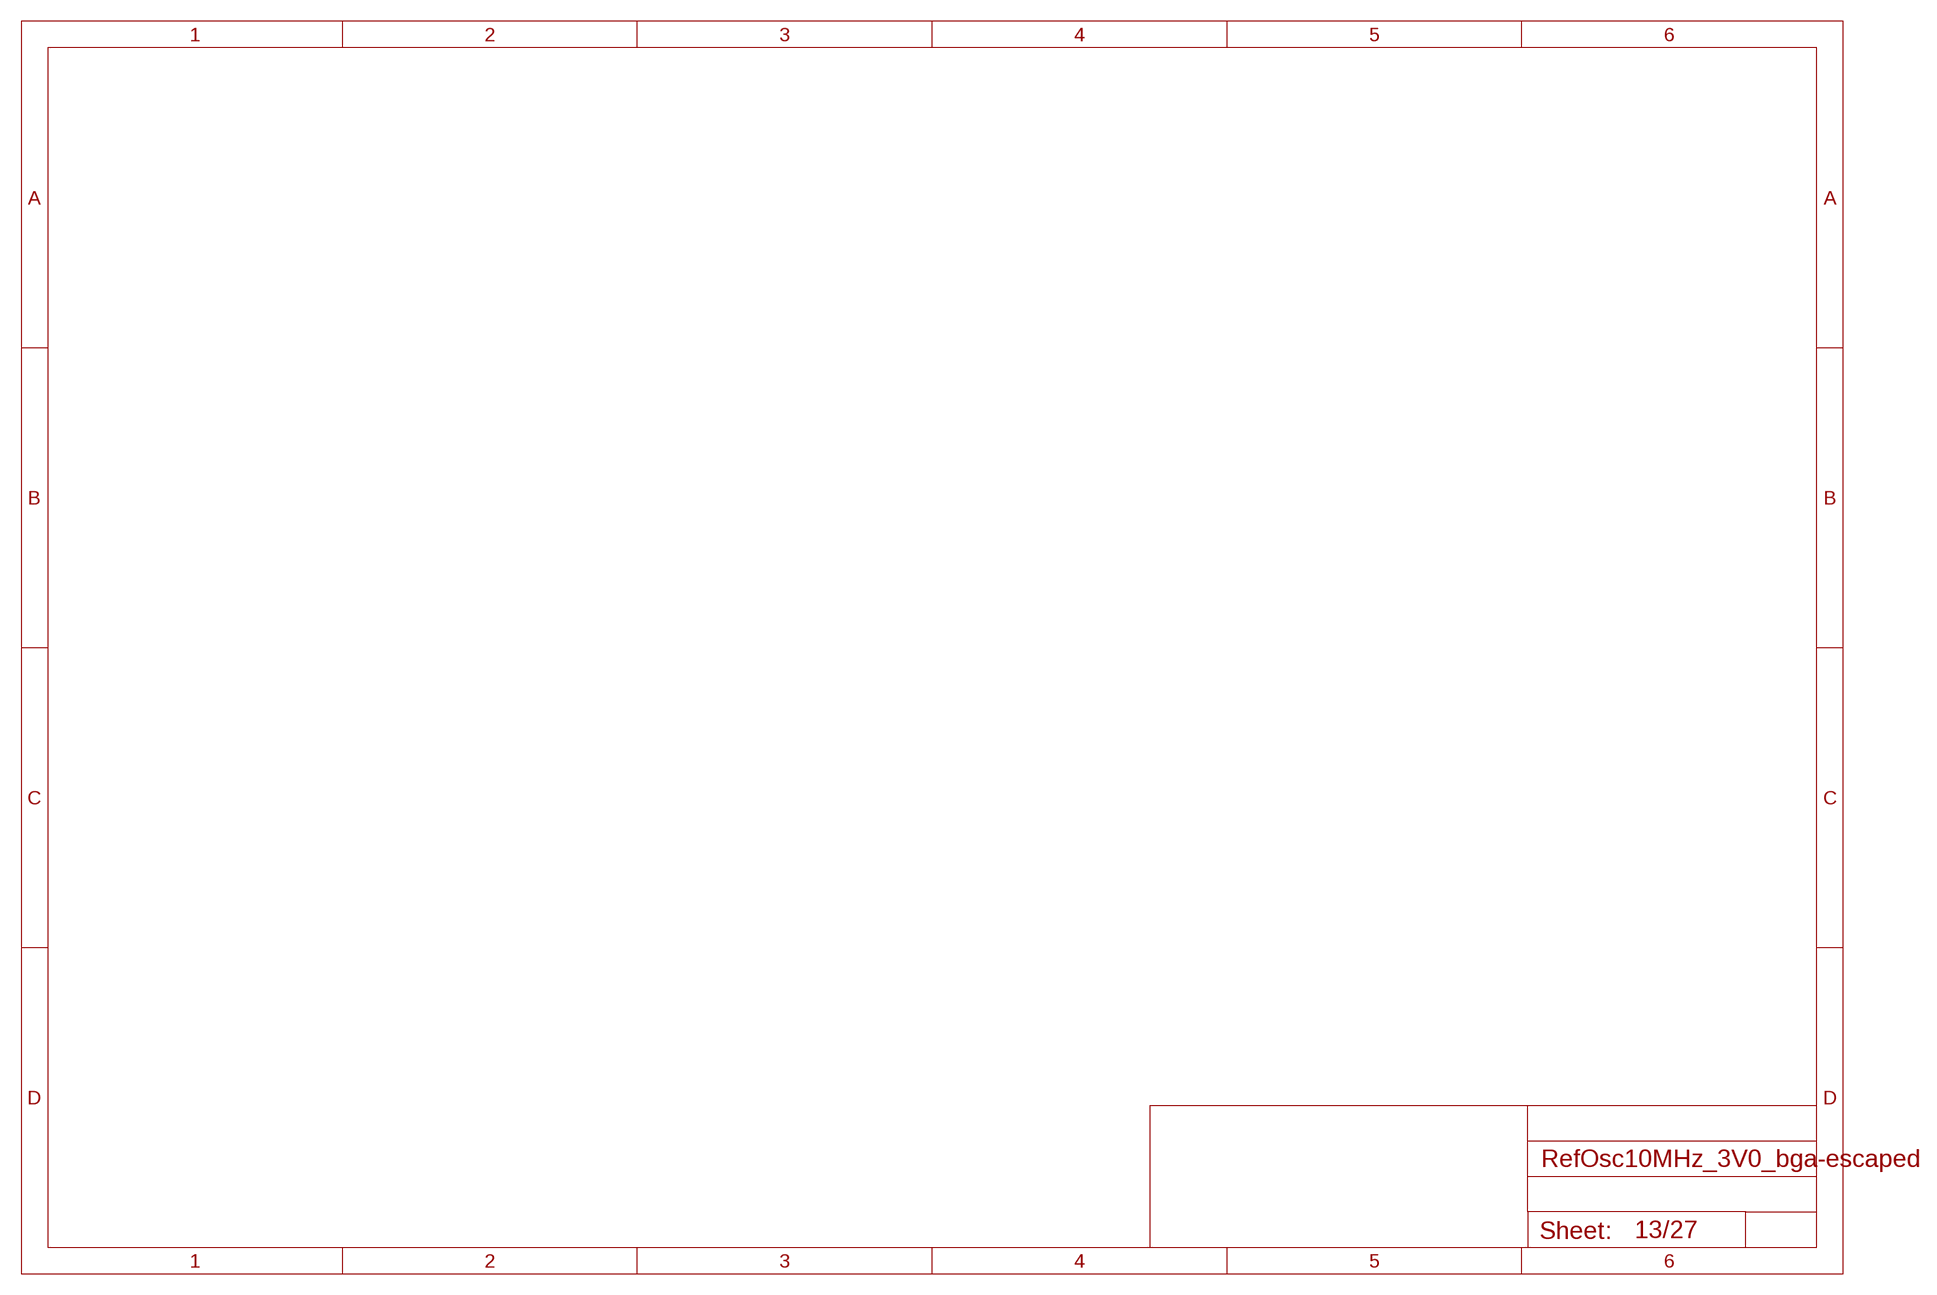
[diagram p12: schematic, sheet 13]
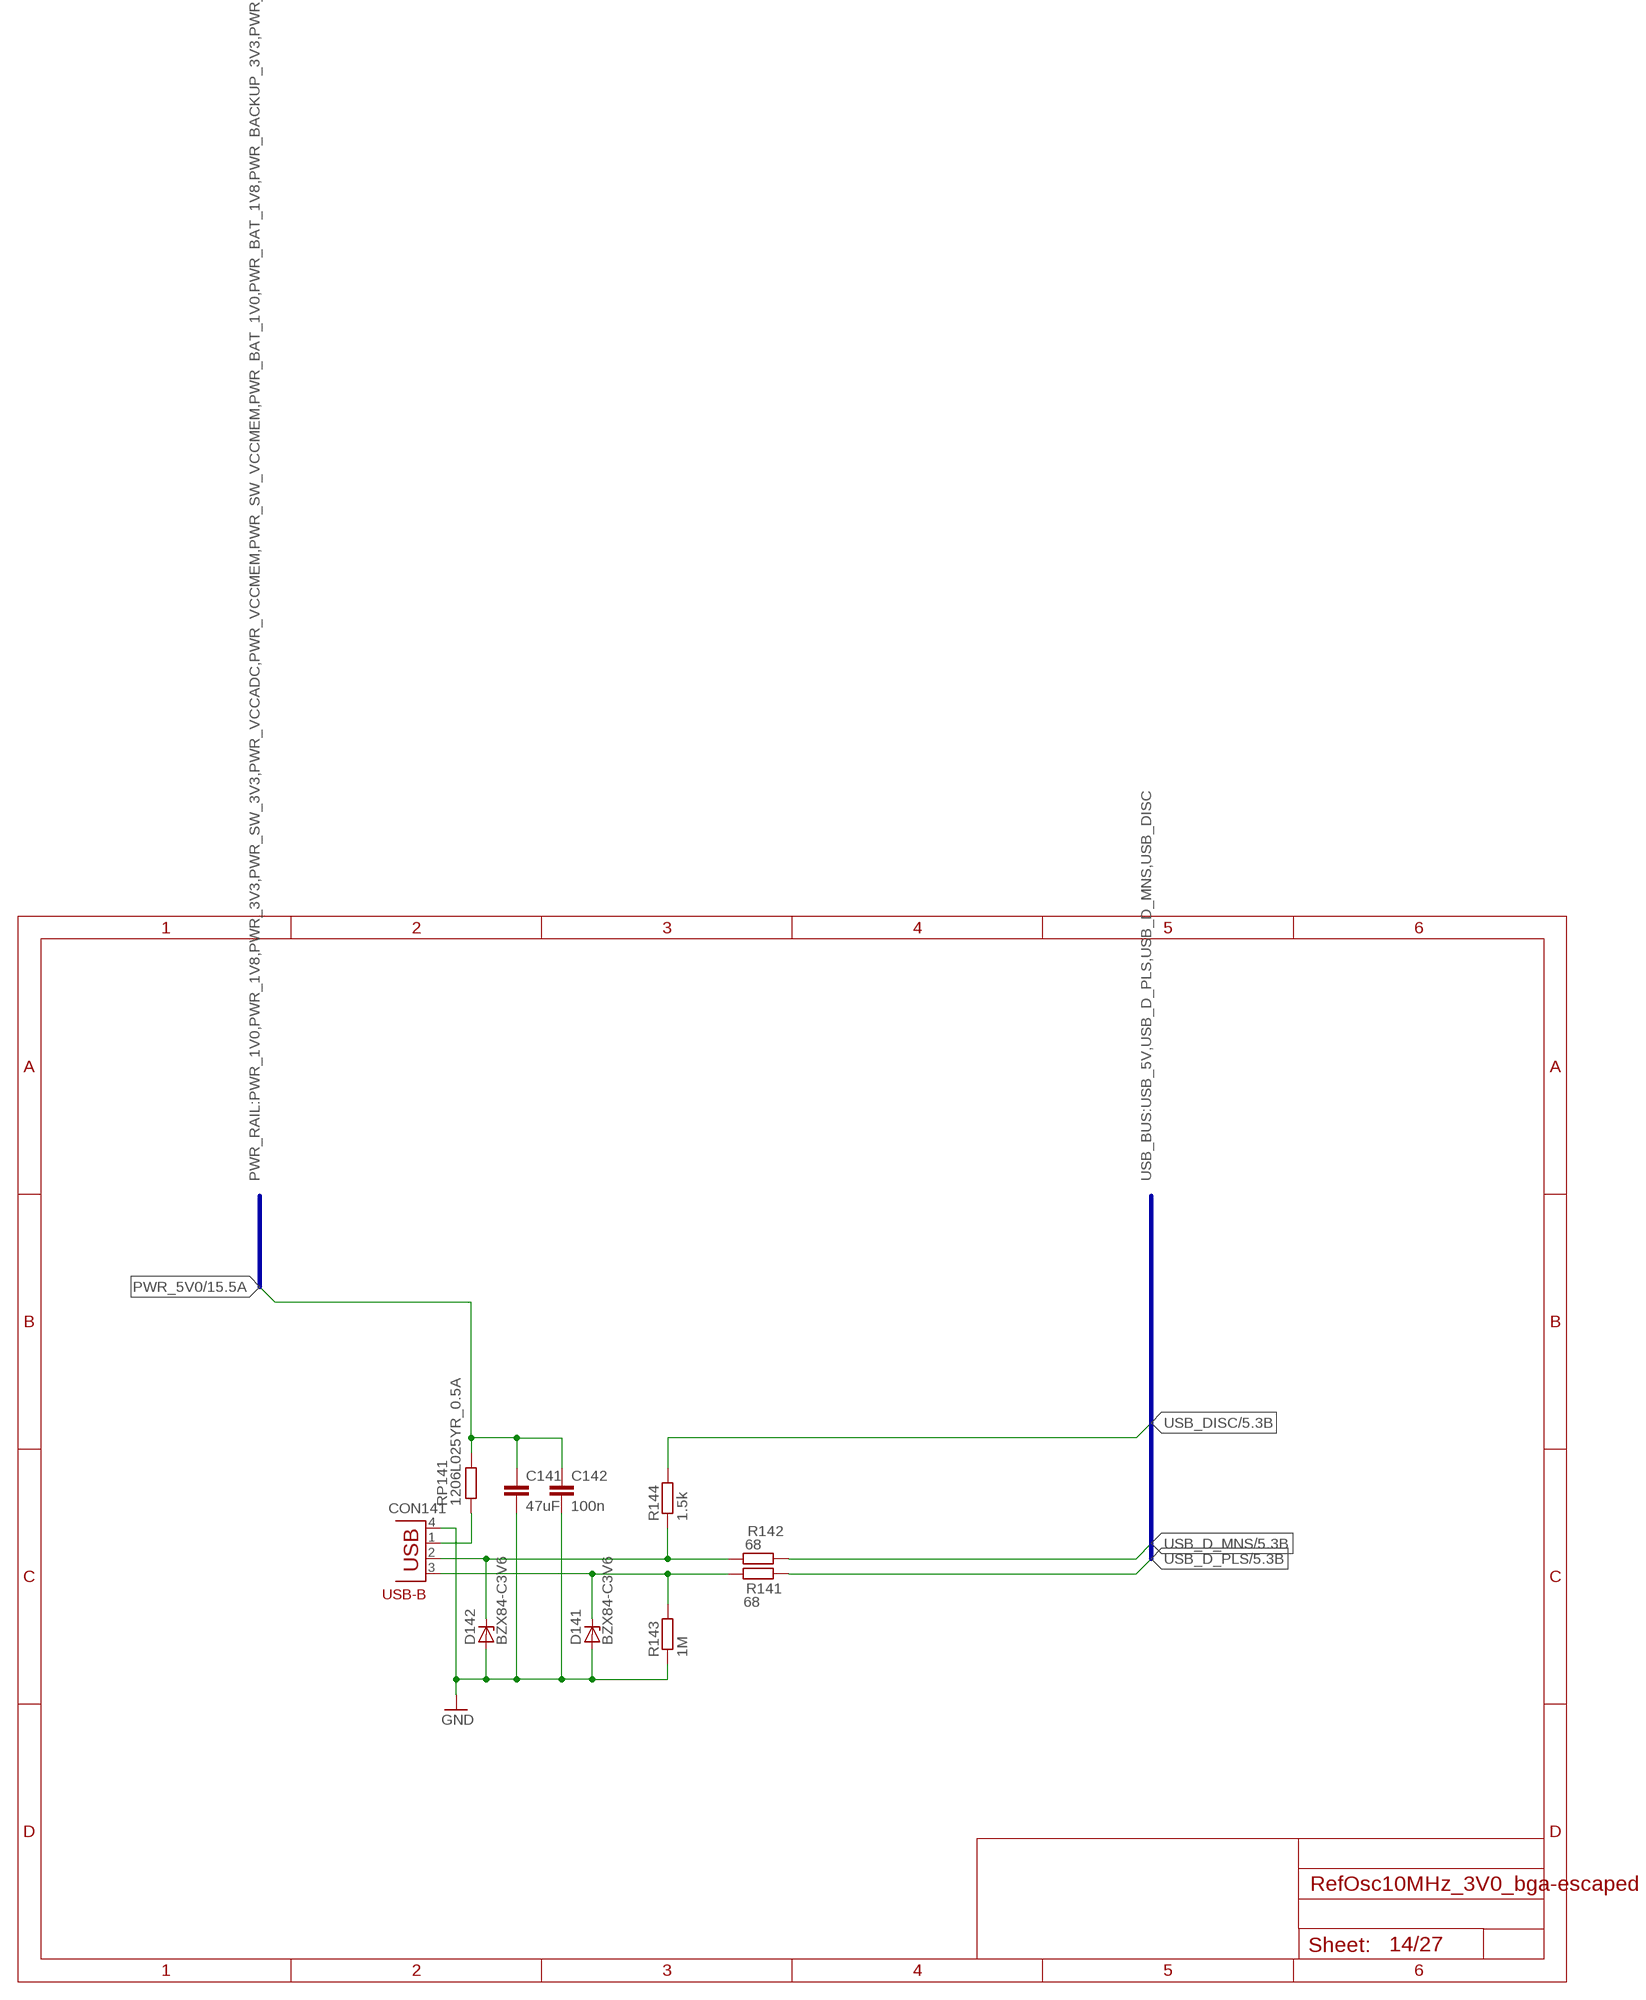
[diagram p13: schematic, sheet 14]
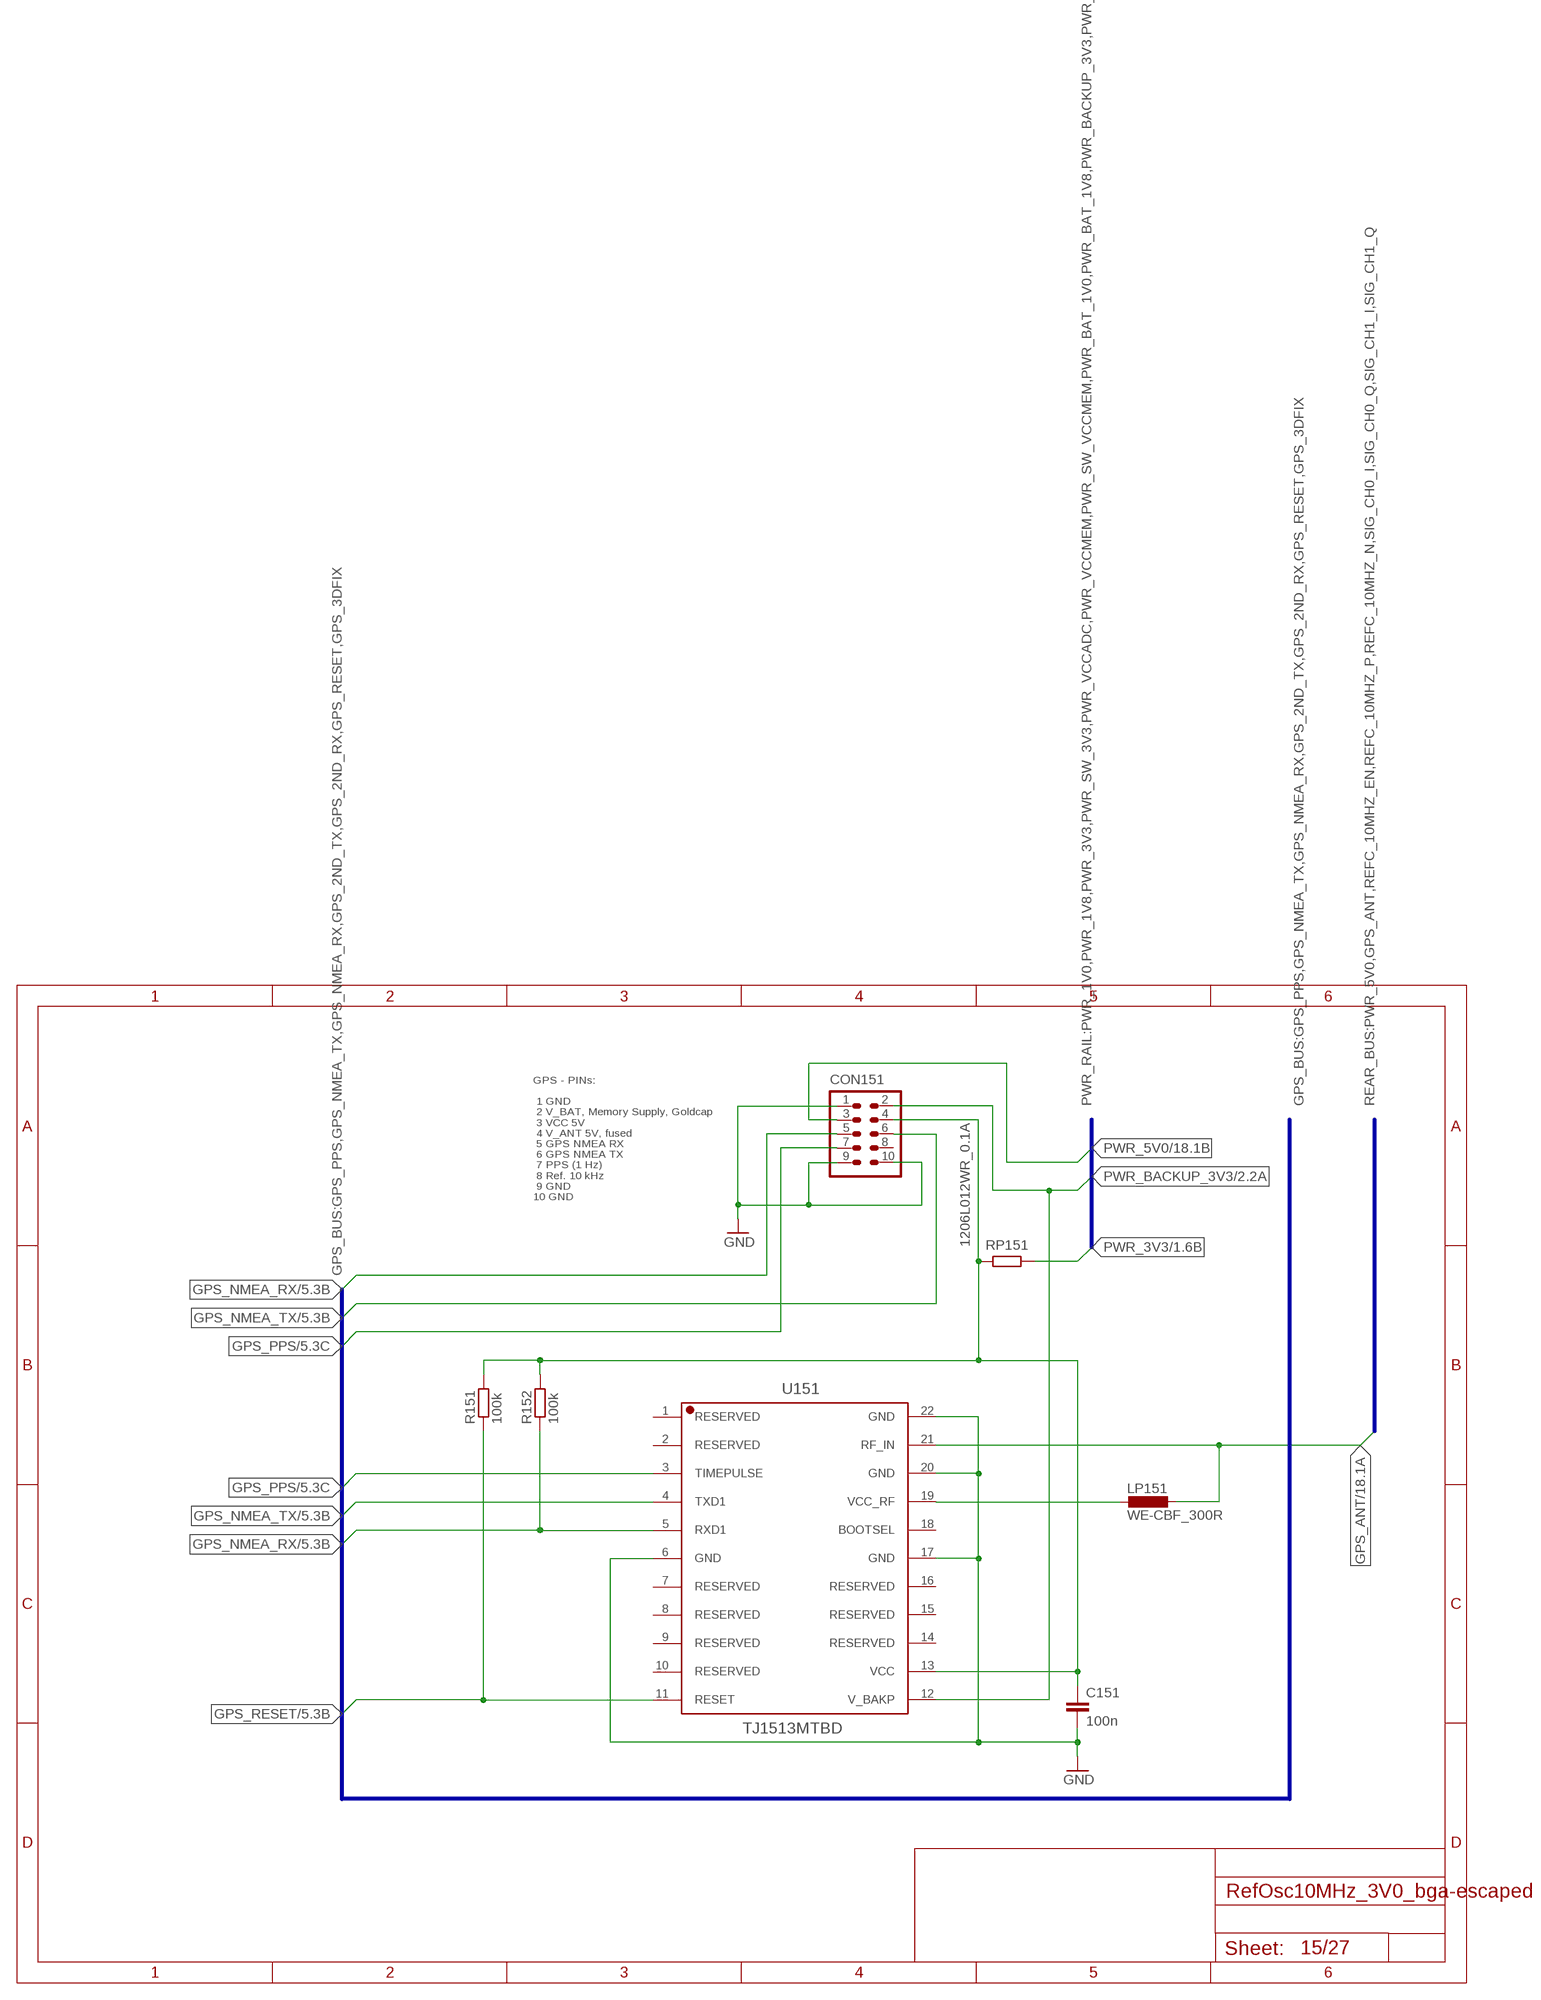
[diagram p14: schematic, sheet 15]
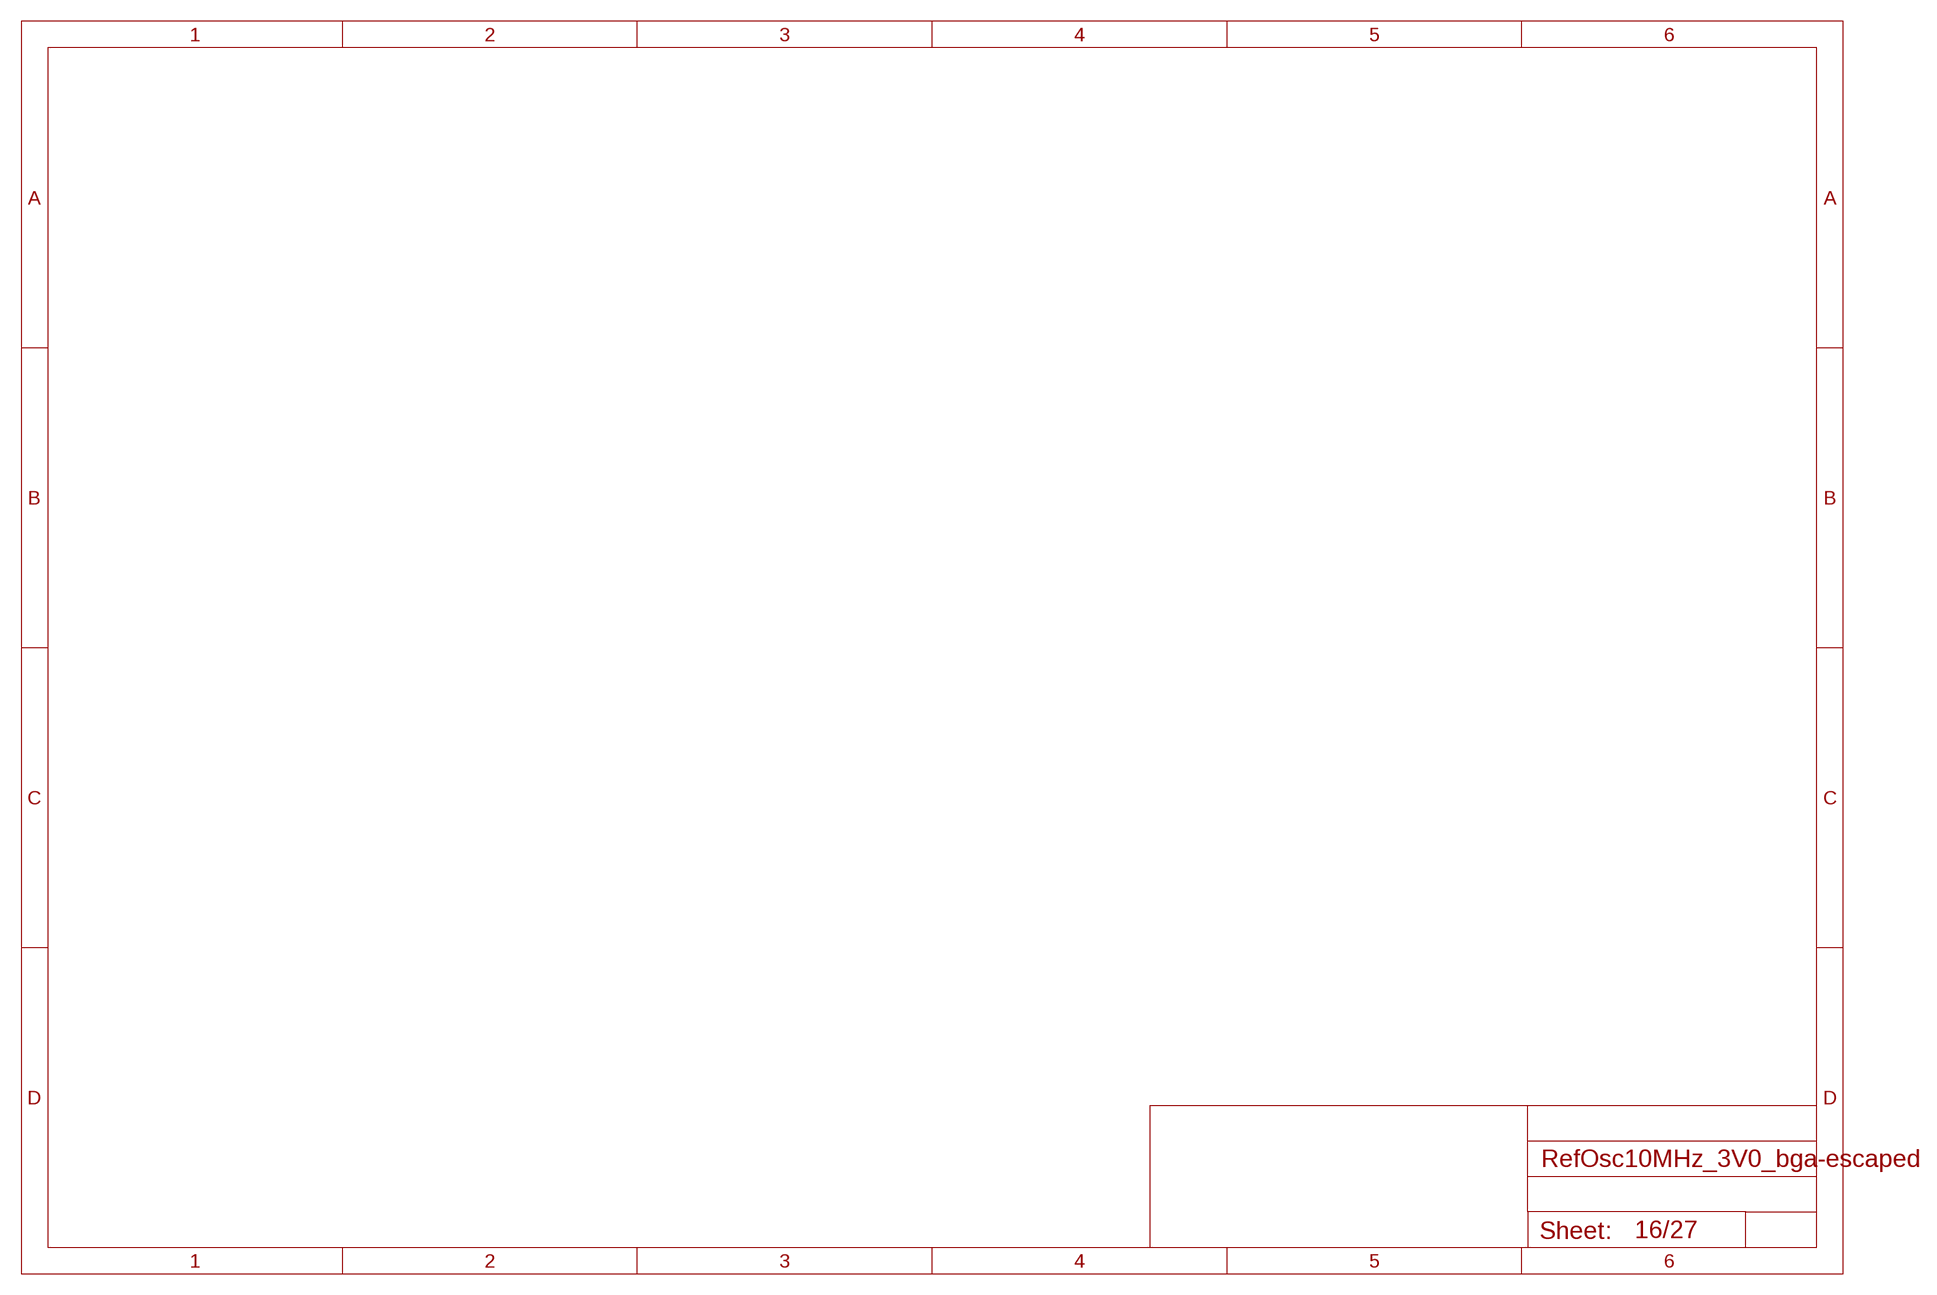
[diagram p15: schematic, sheet 16]
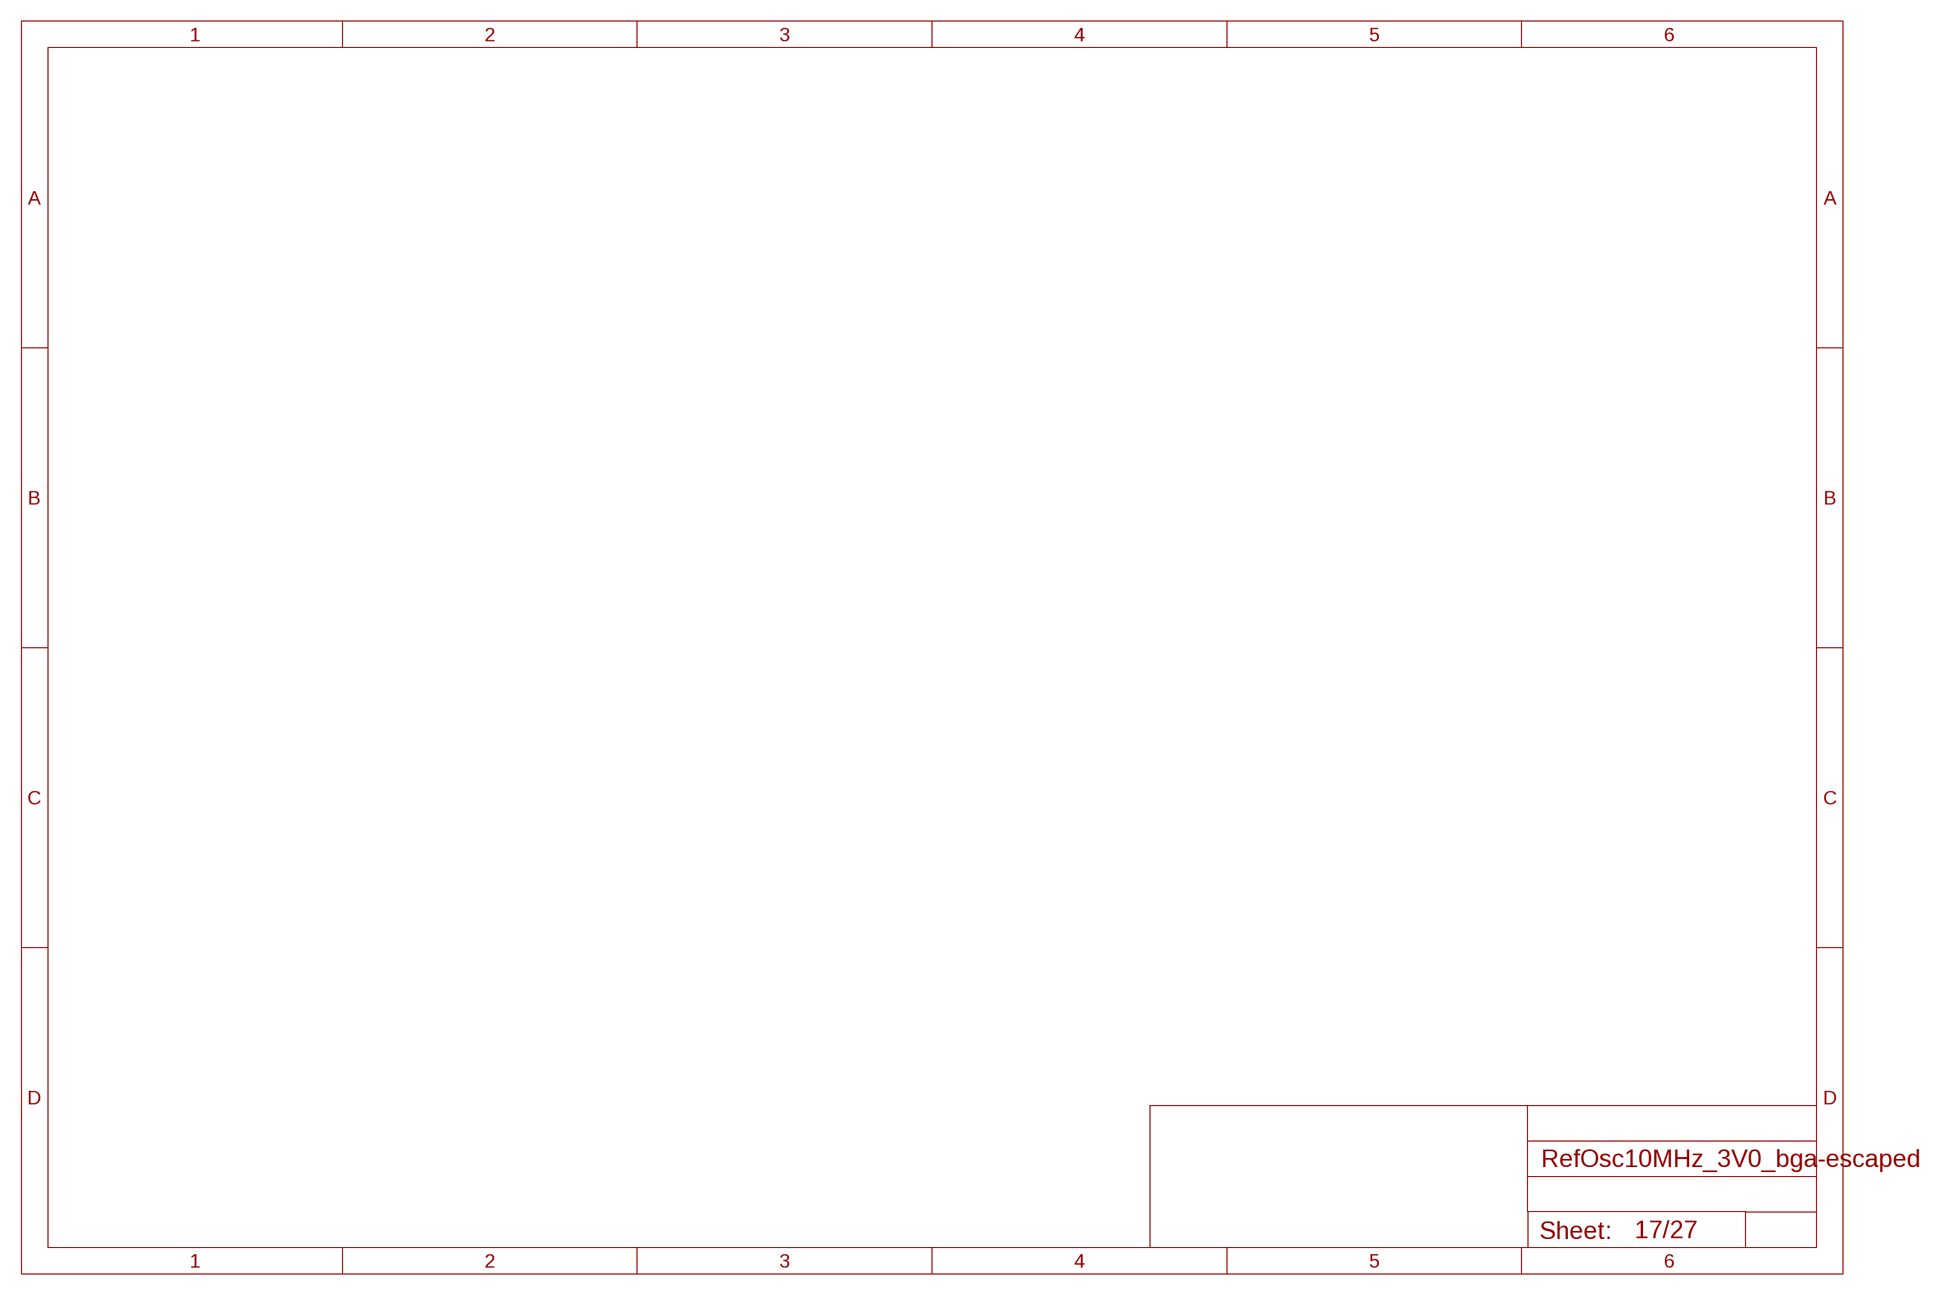
[diagram p16: schematic, sheet 17]
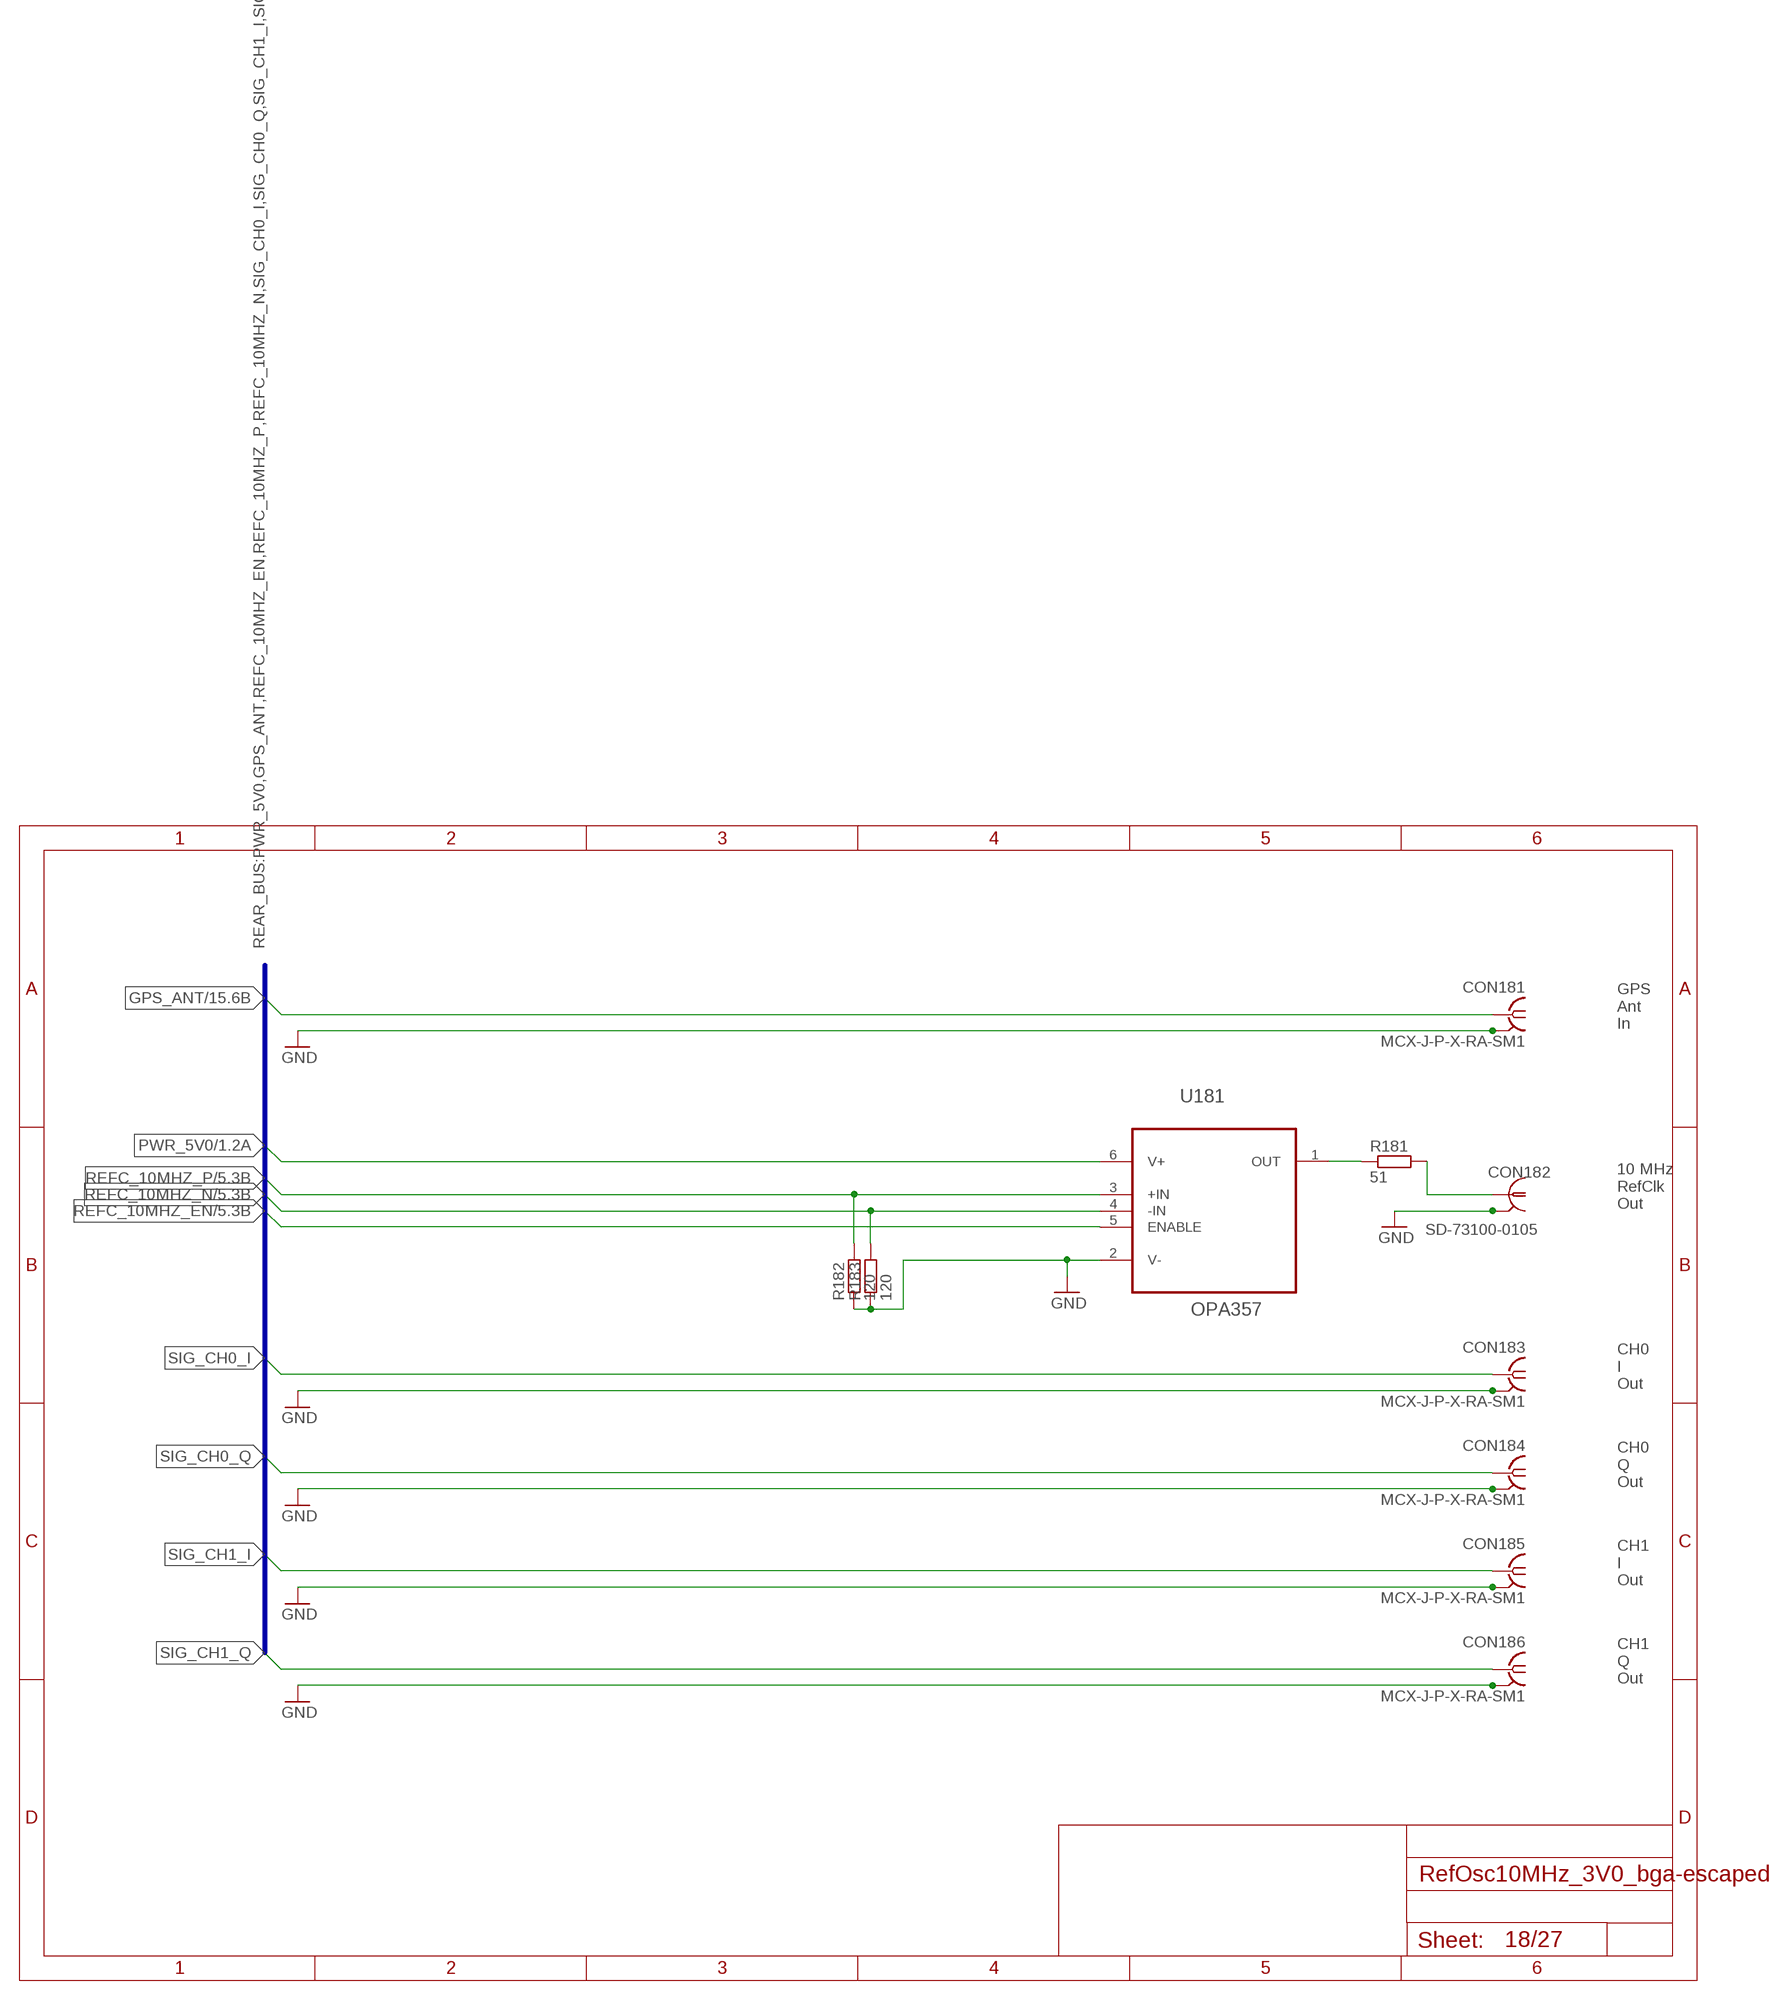
[diagram p17: schematic, sheet 18]
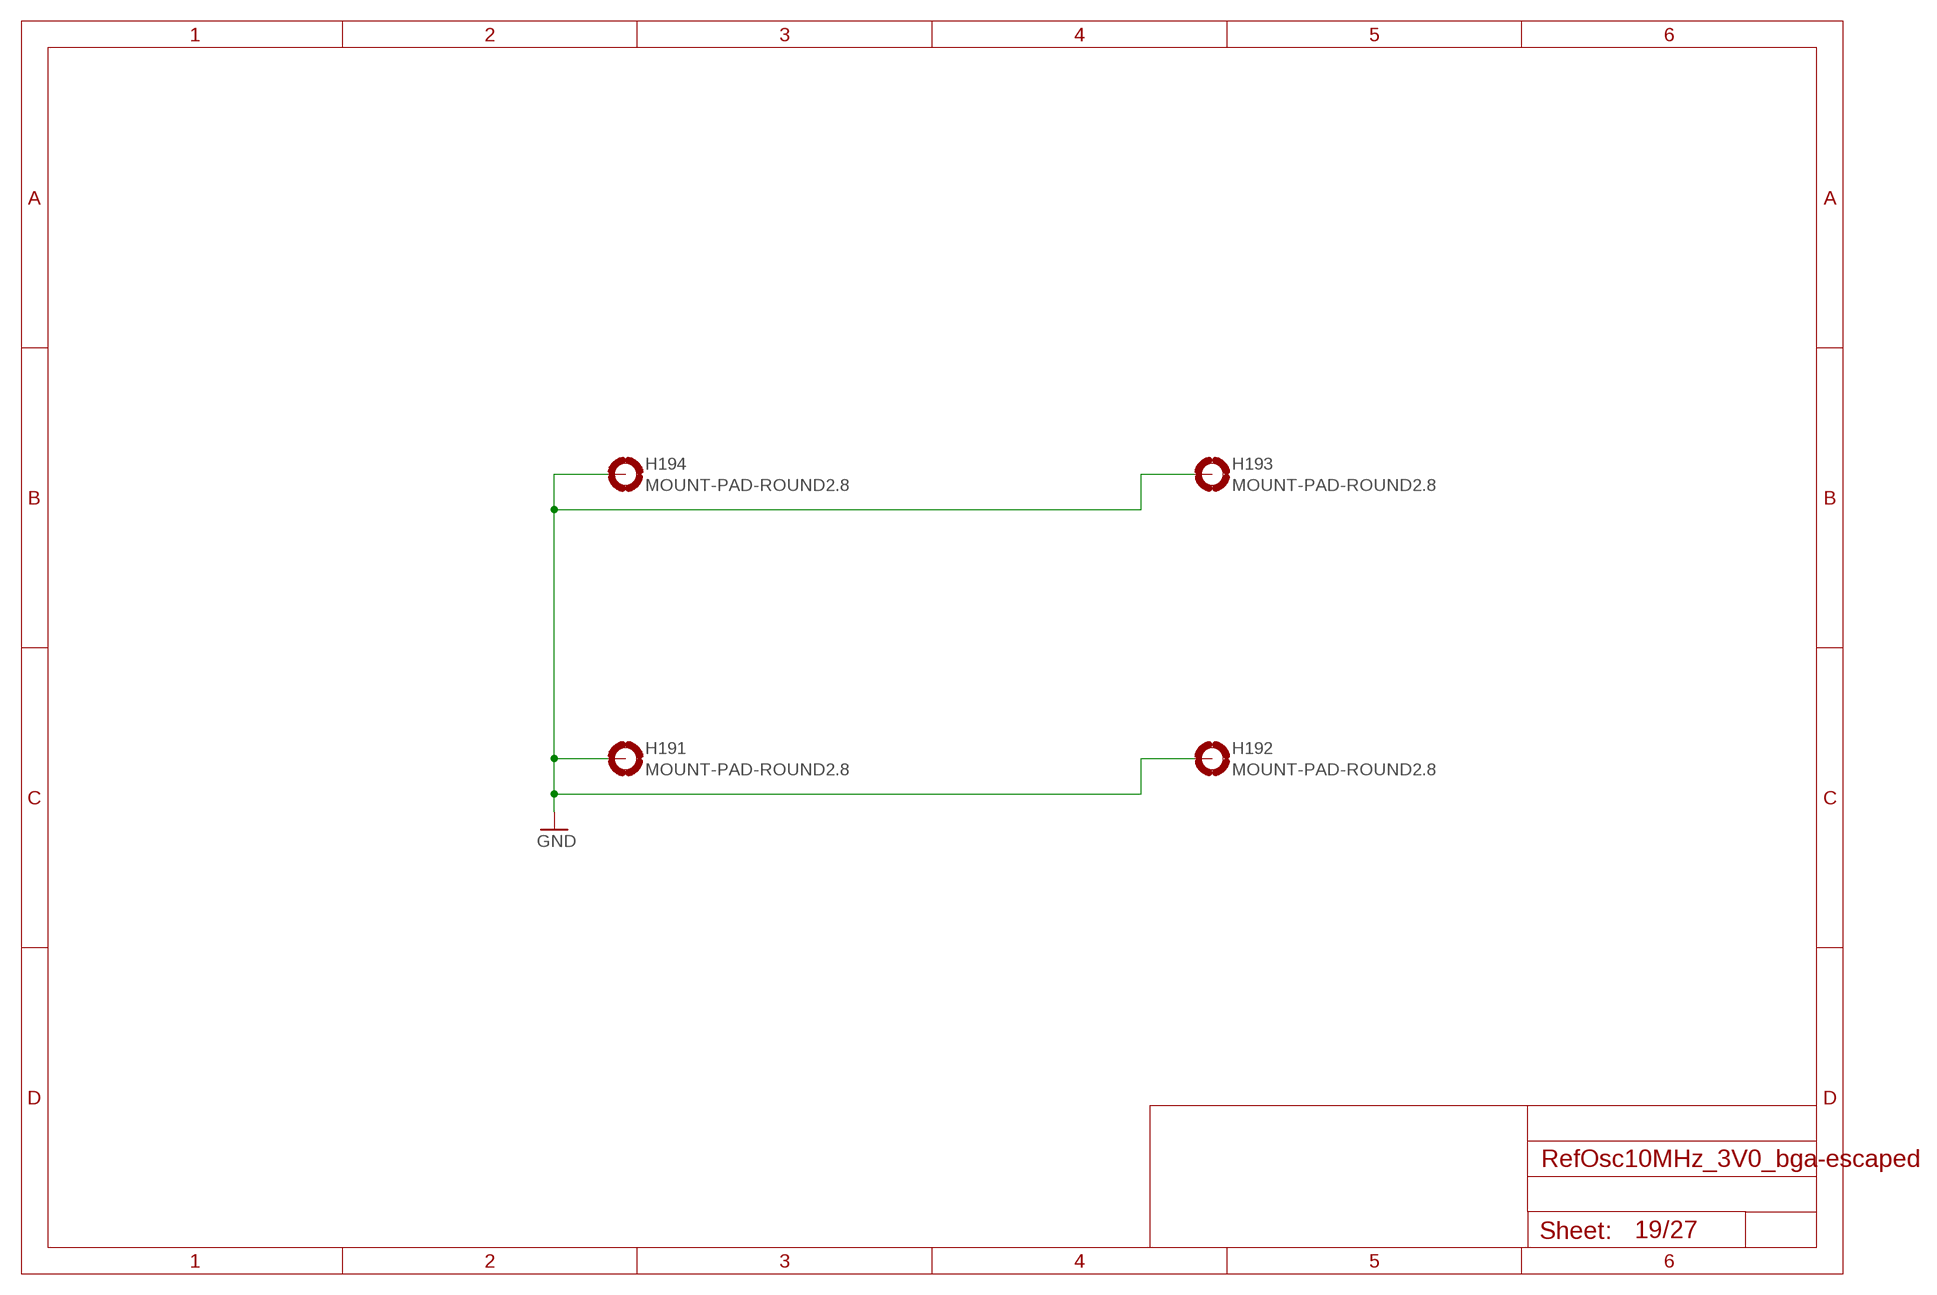
[diagram p18: schematic, sheet 19]
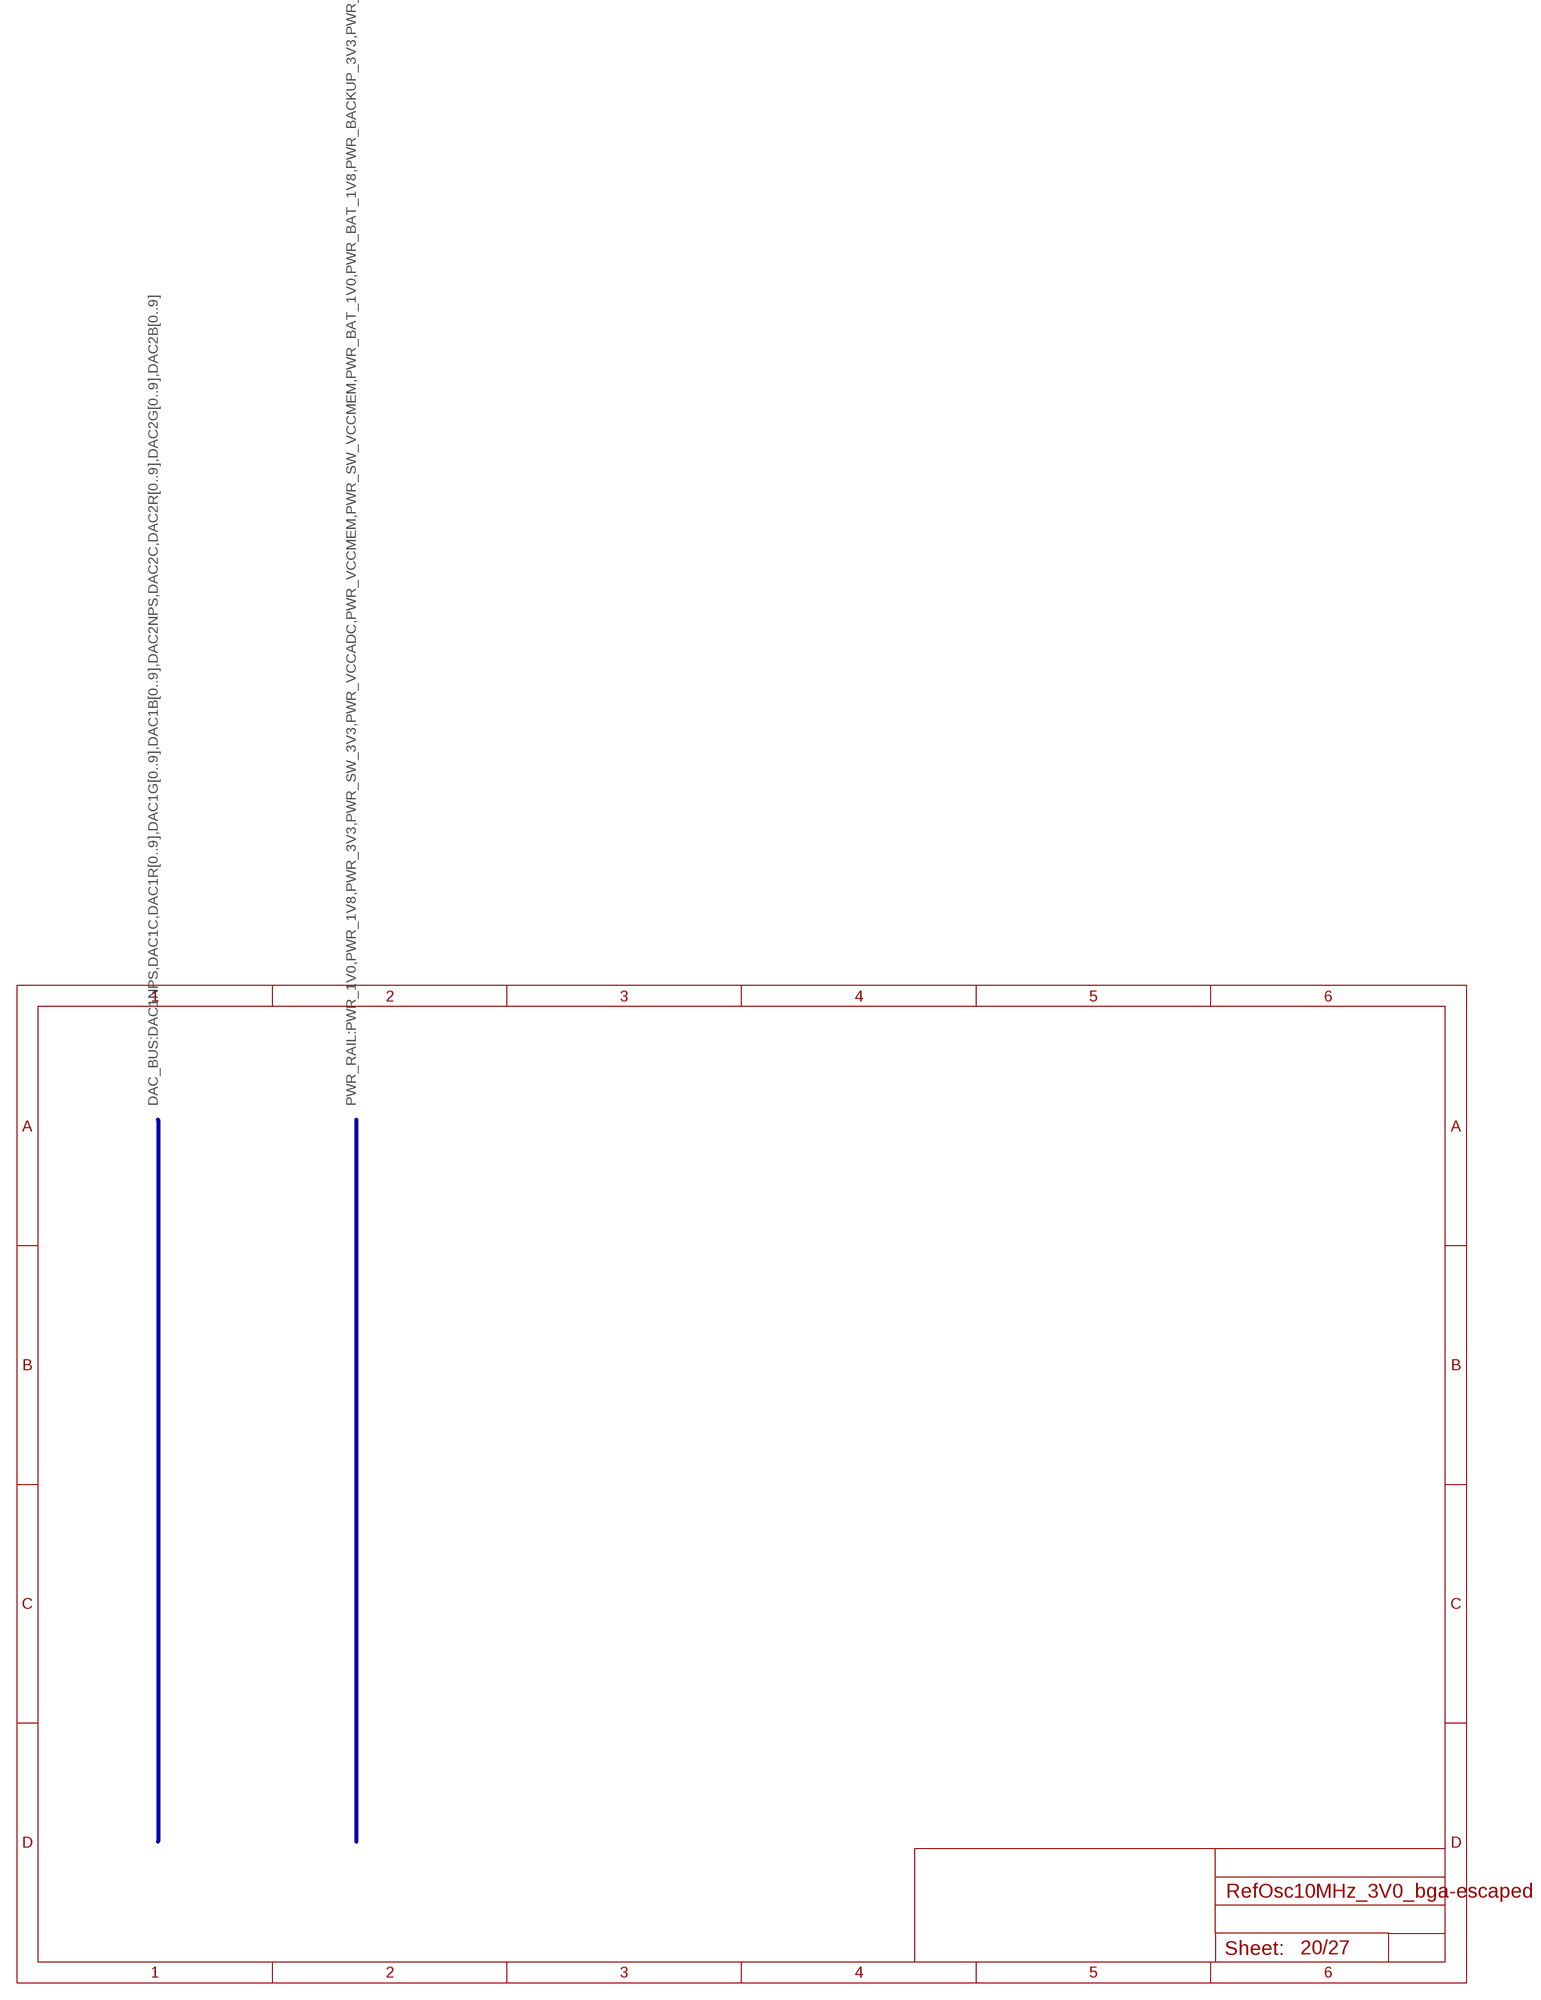
[diagram p19: schematic, sheet 20]
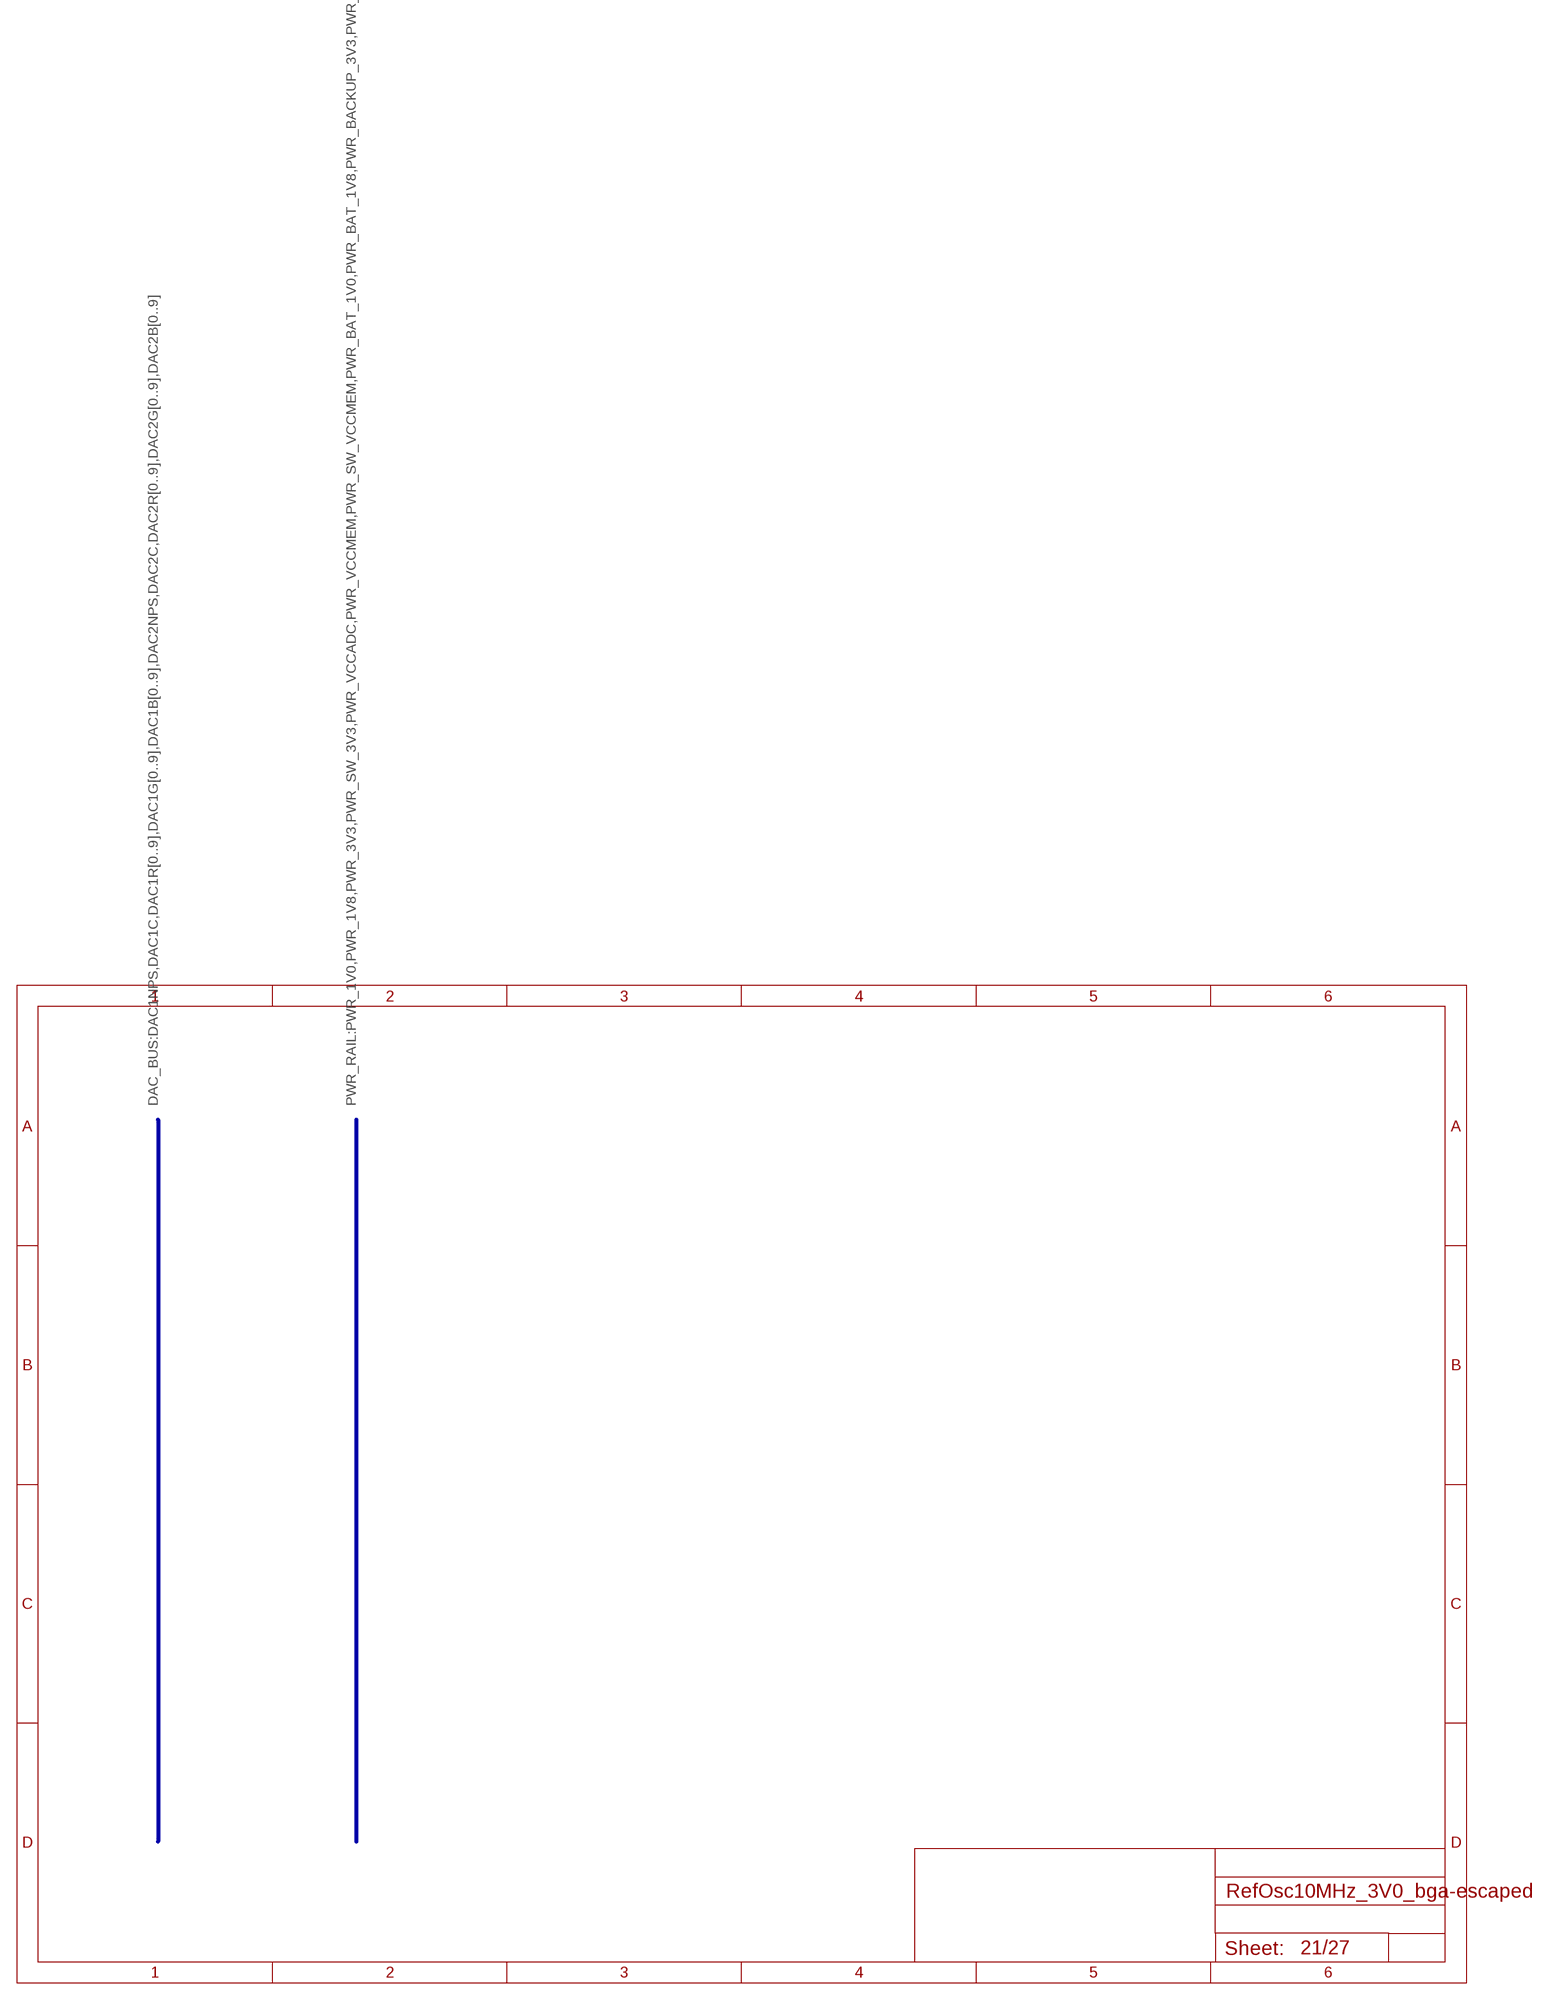
[diagram p20: schematic, sheet 21]
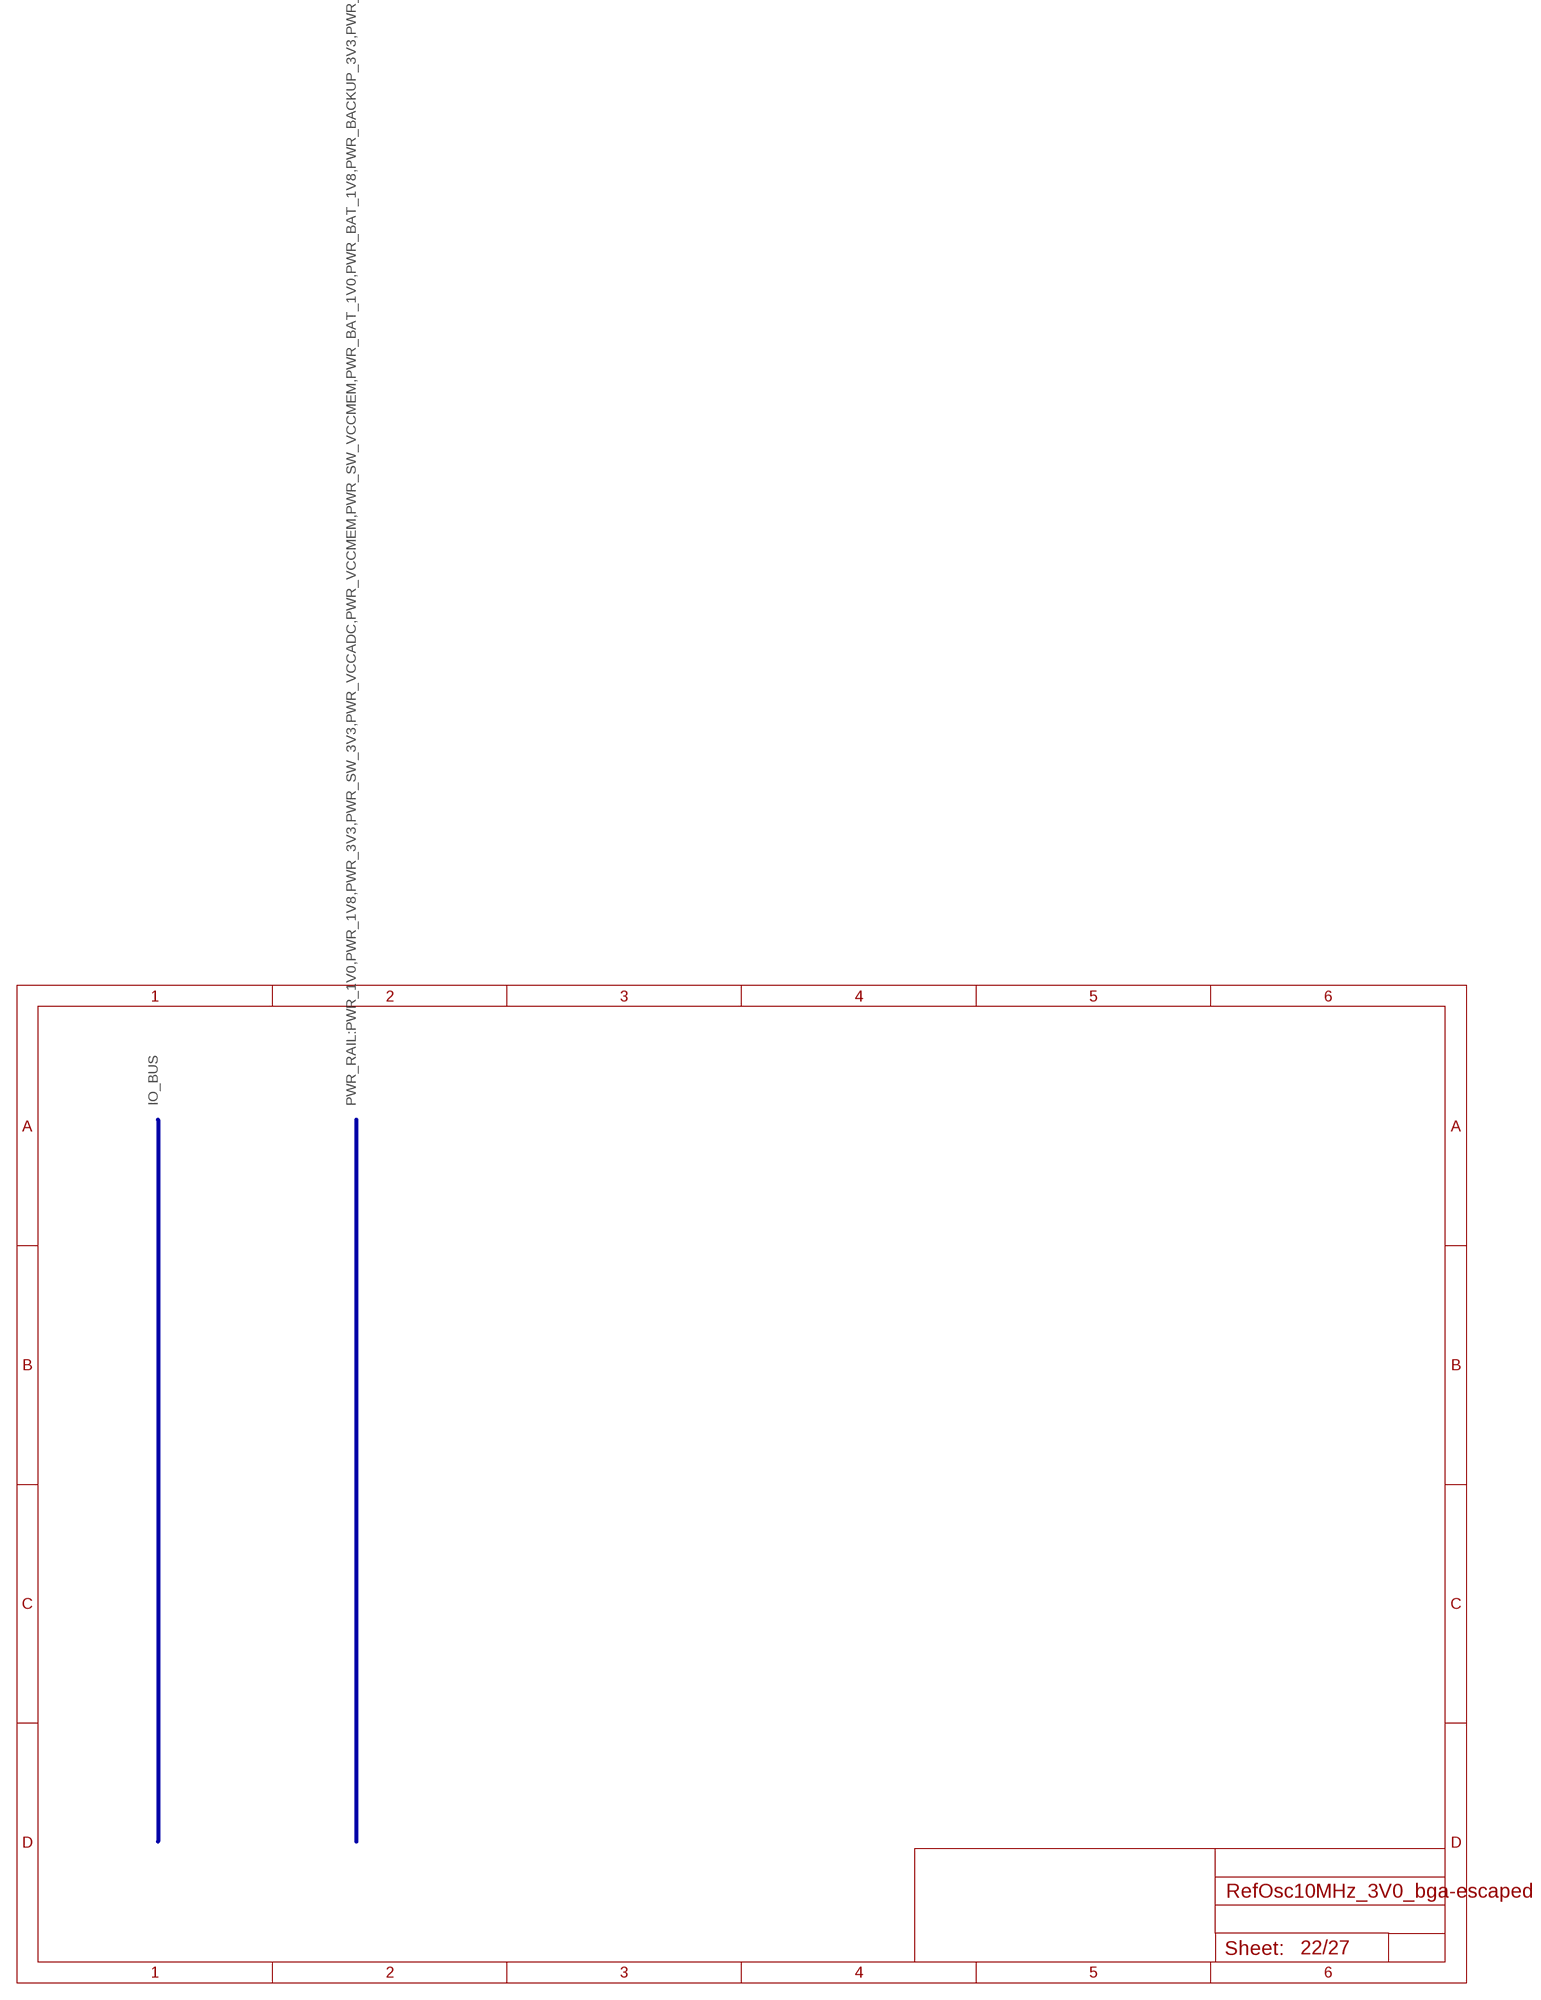
[diagram p21: schematic, sheet 22]
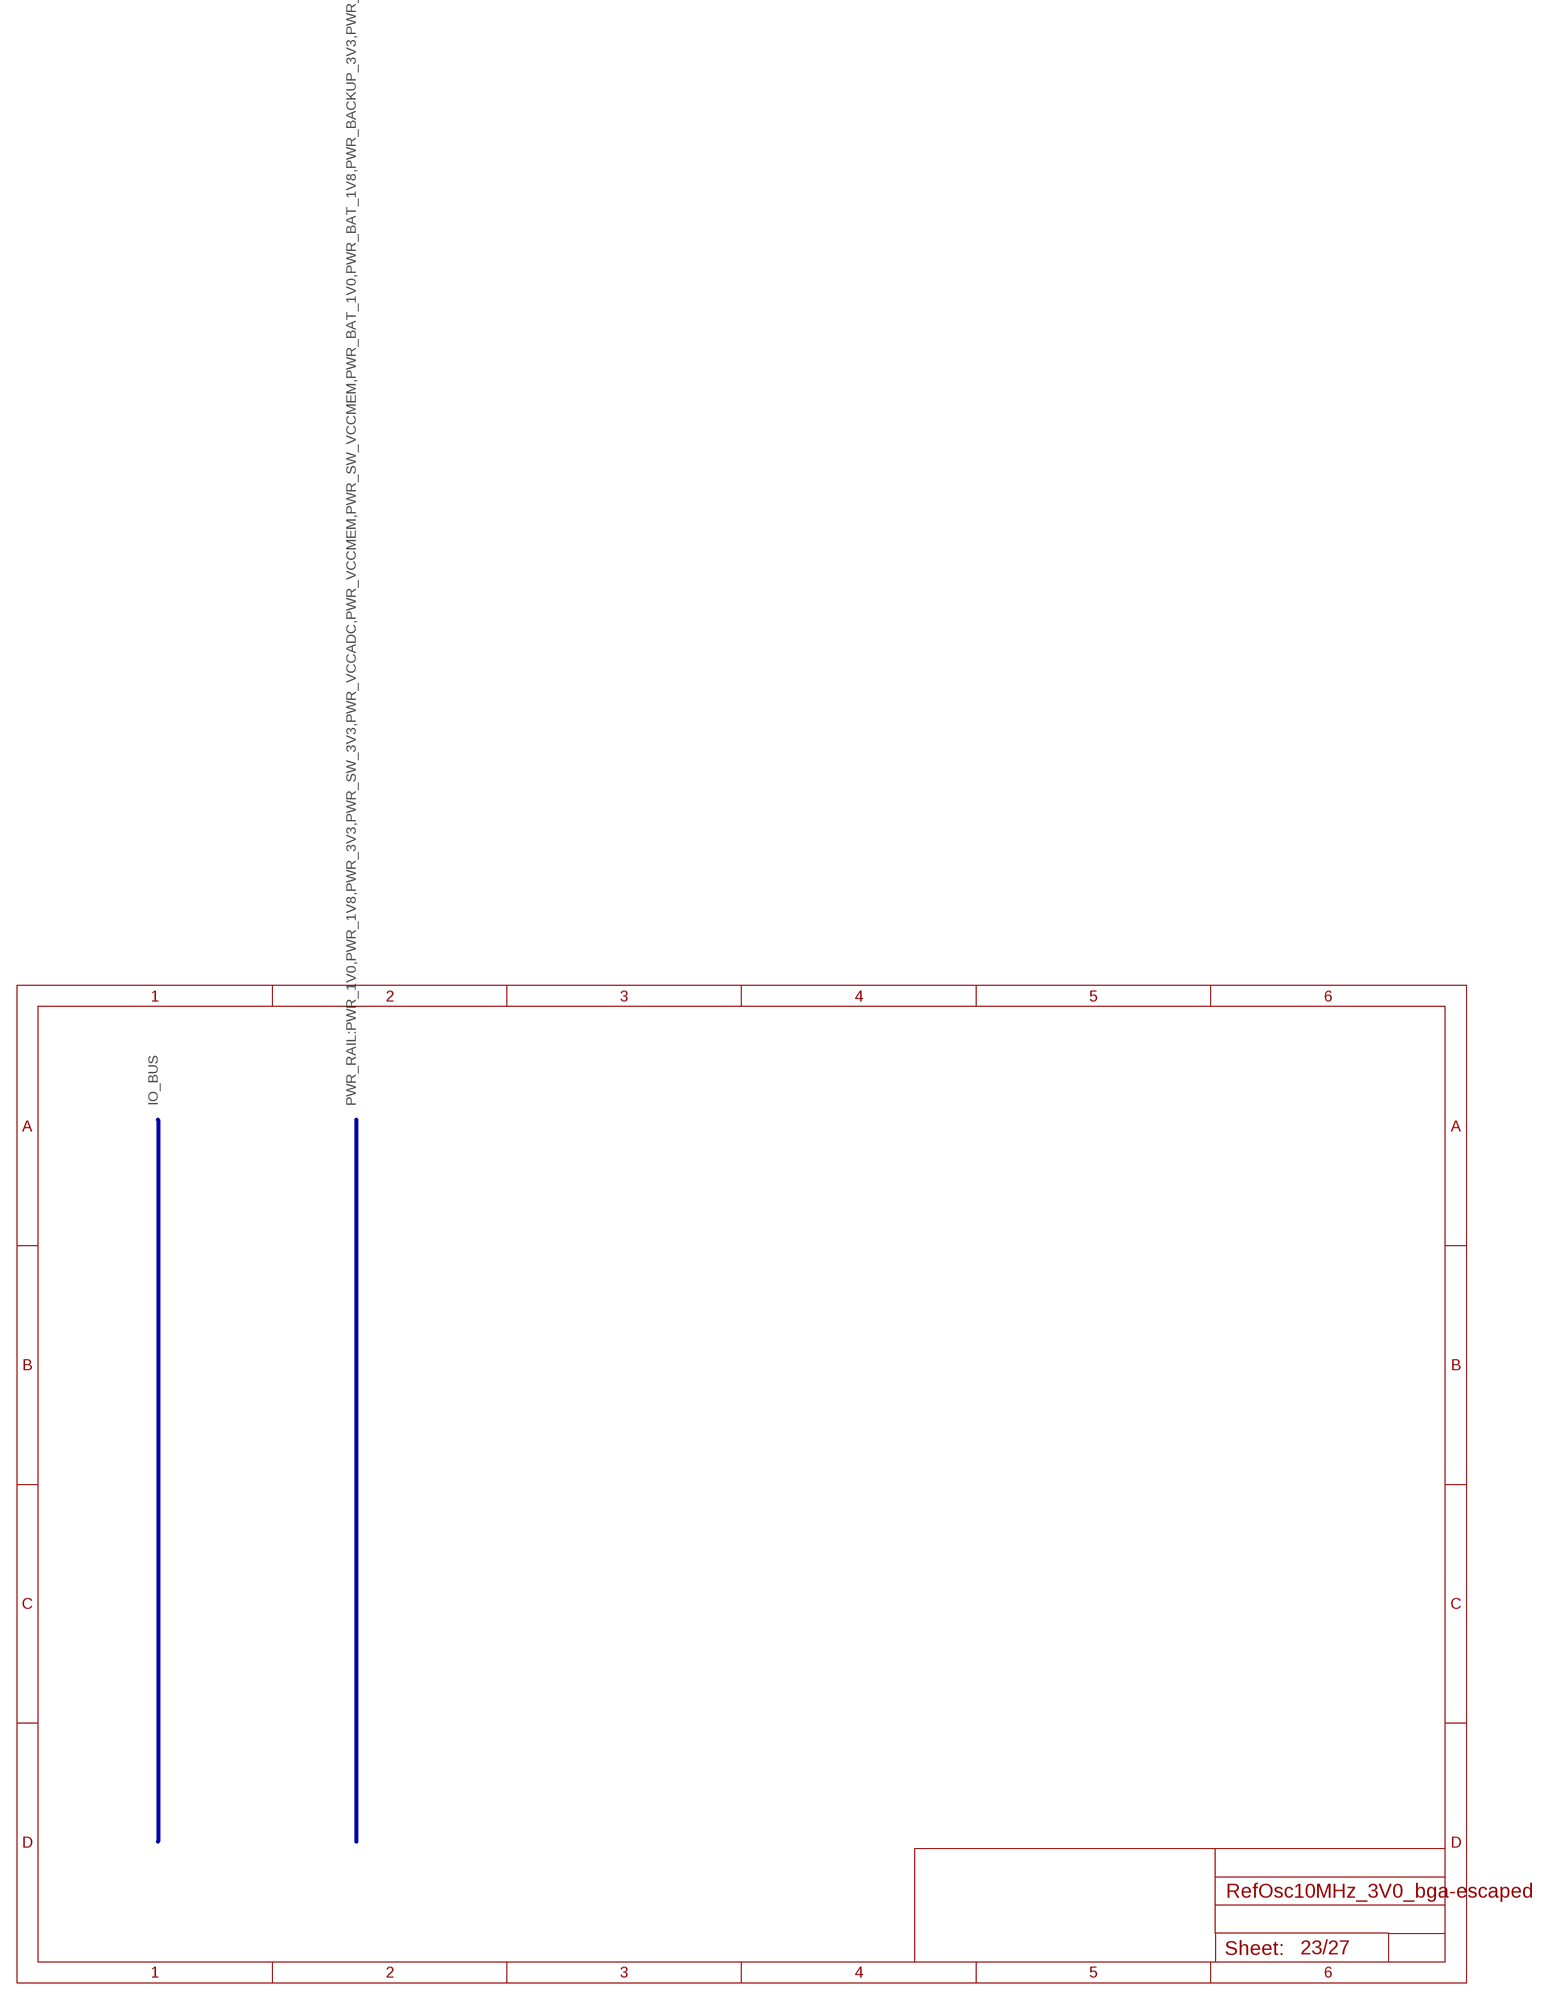
[diagram p22: schematic, sheet 23]
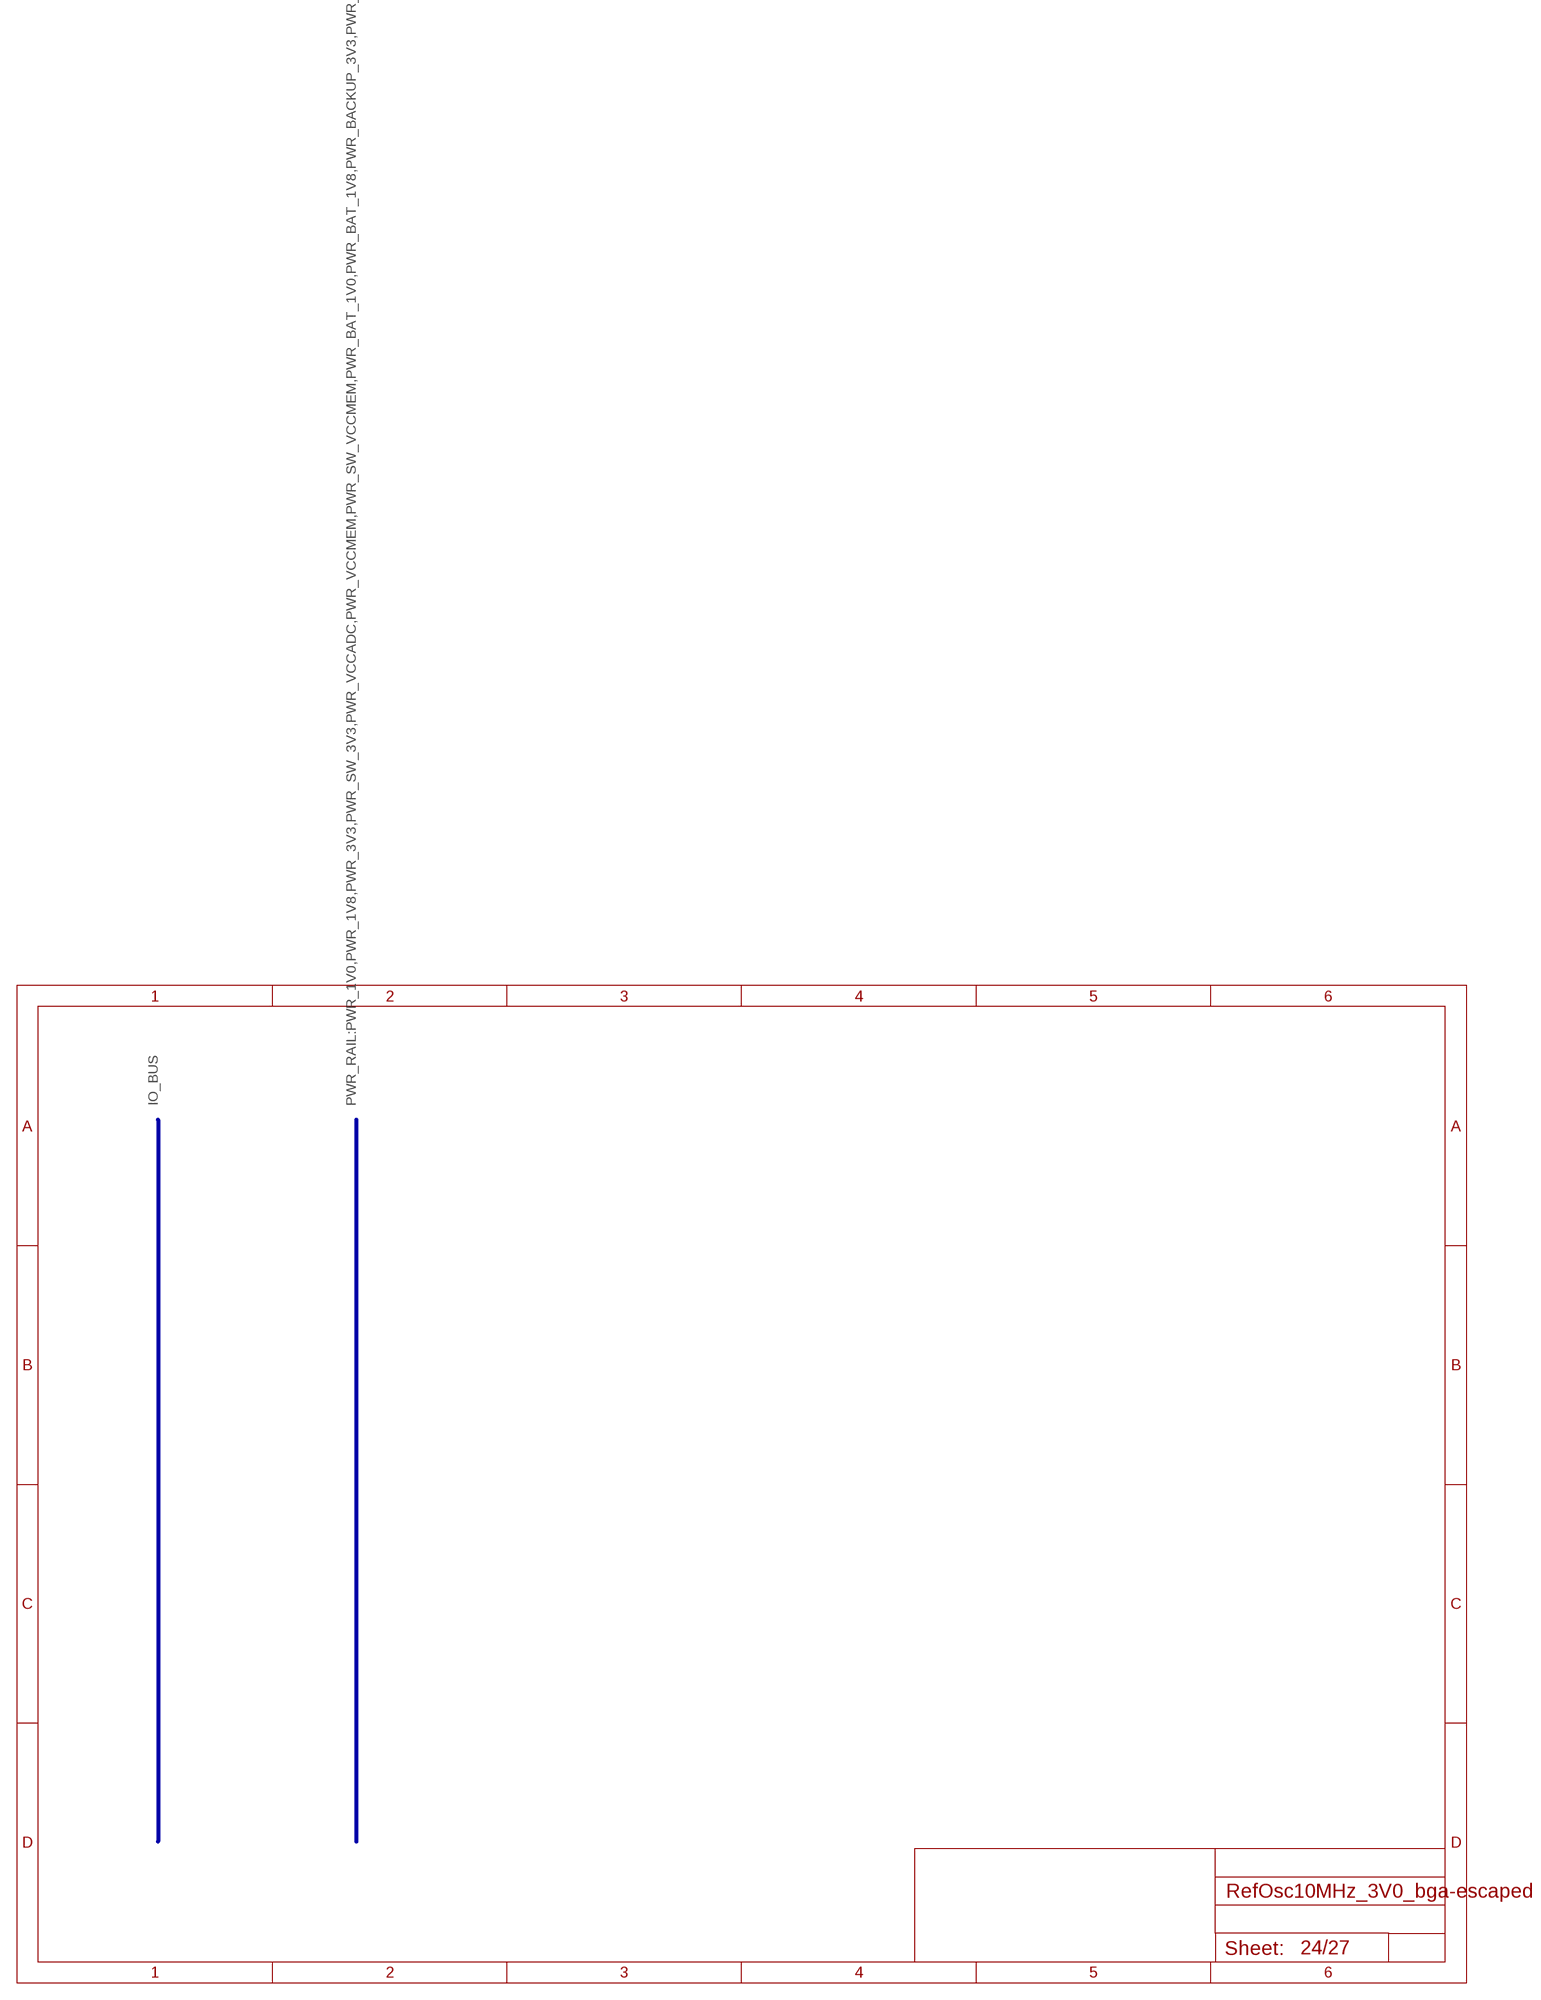
[diagram p23: schematic, sheet 24]
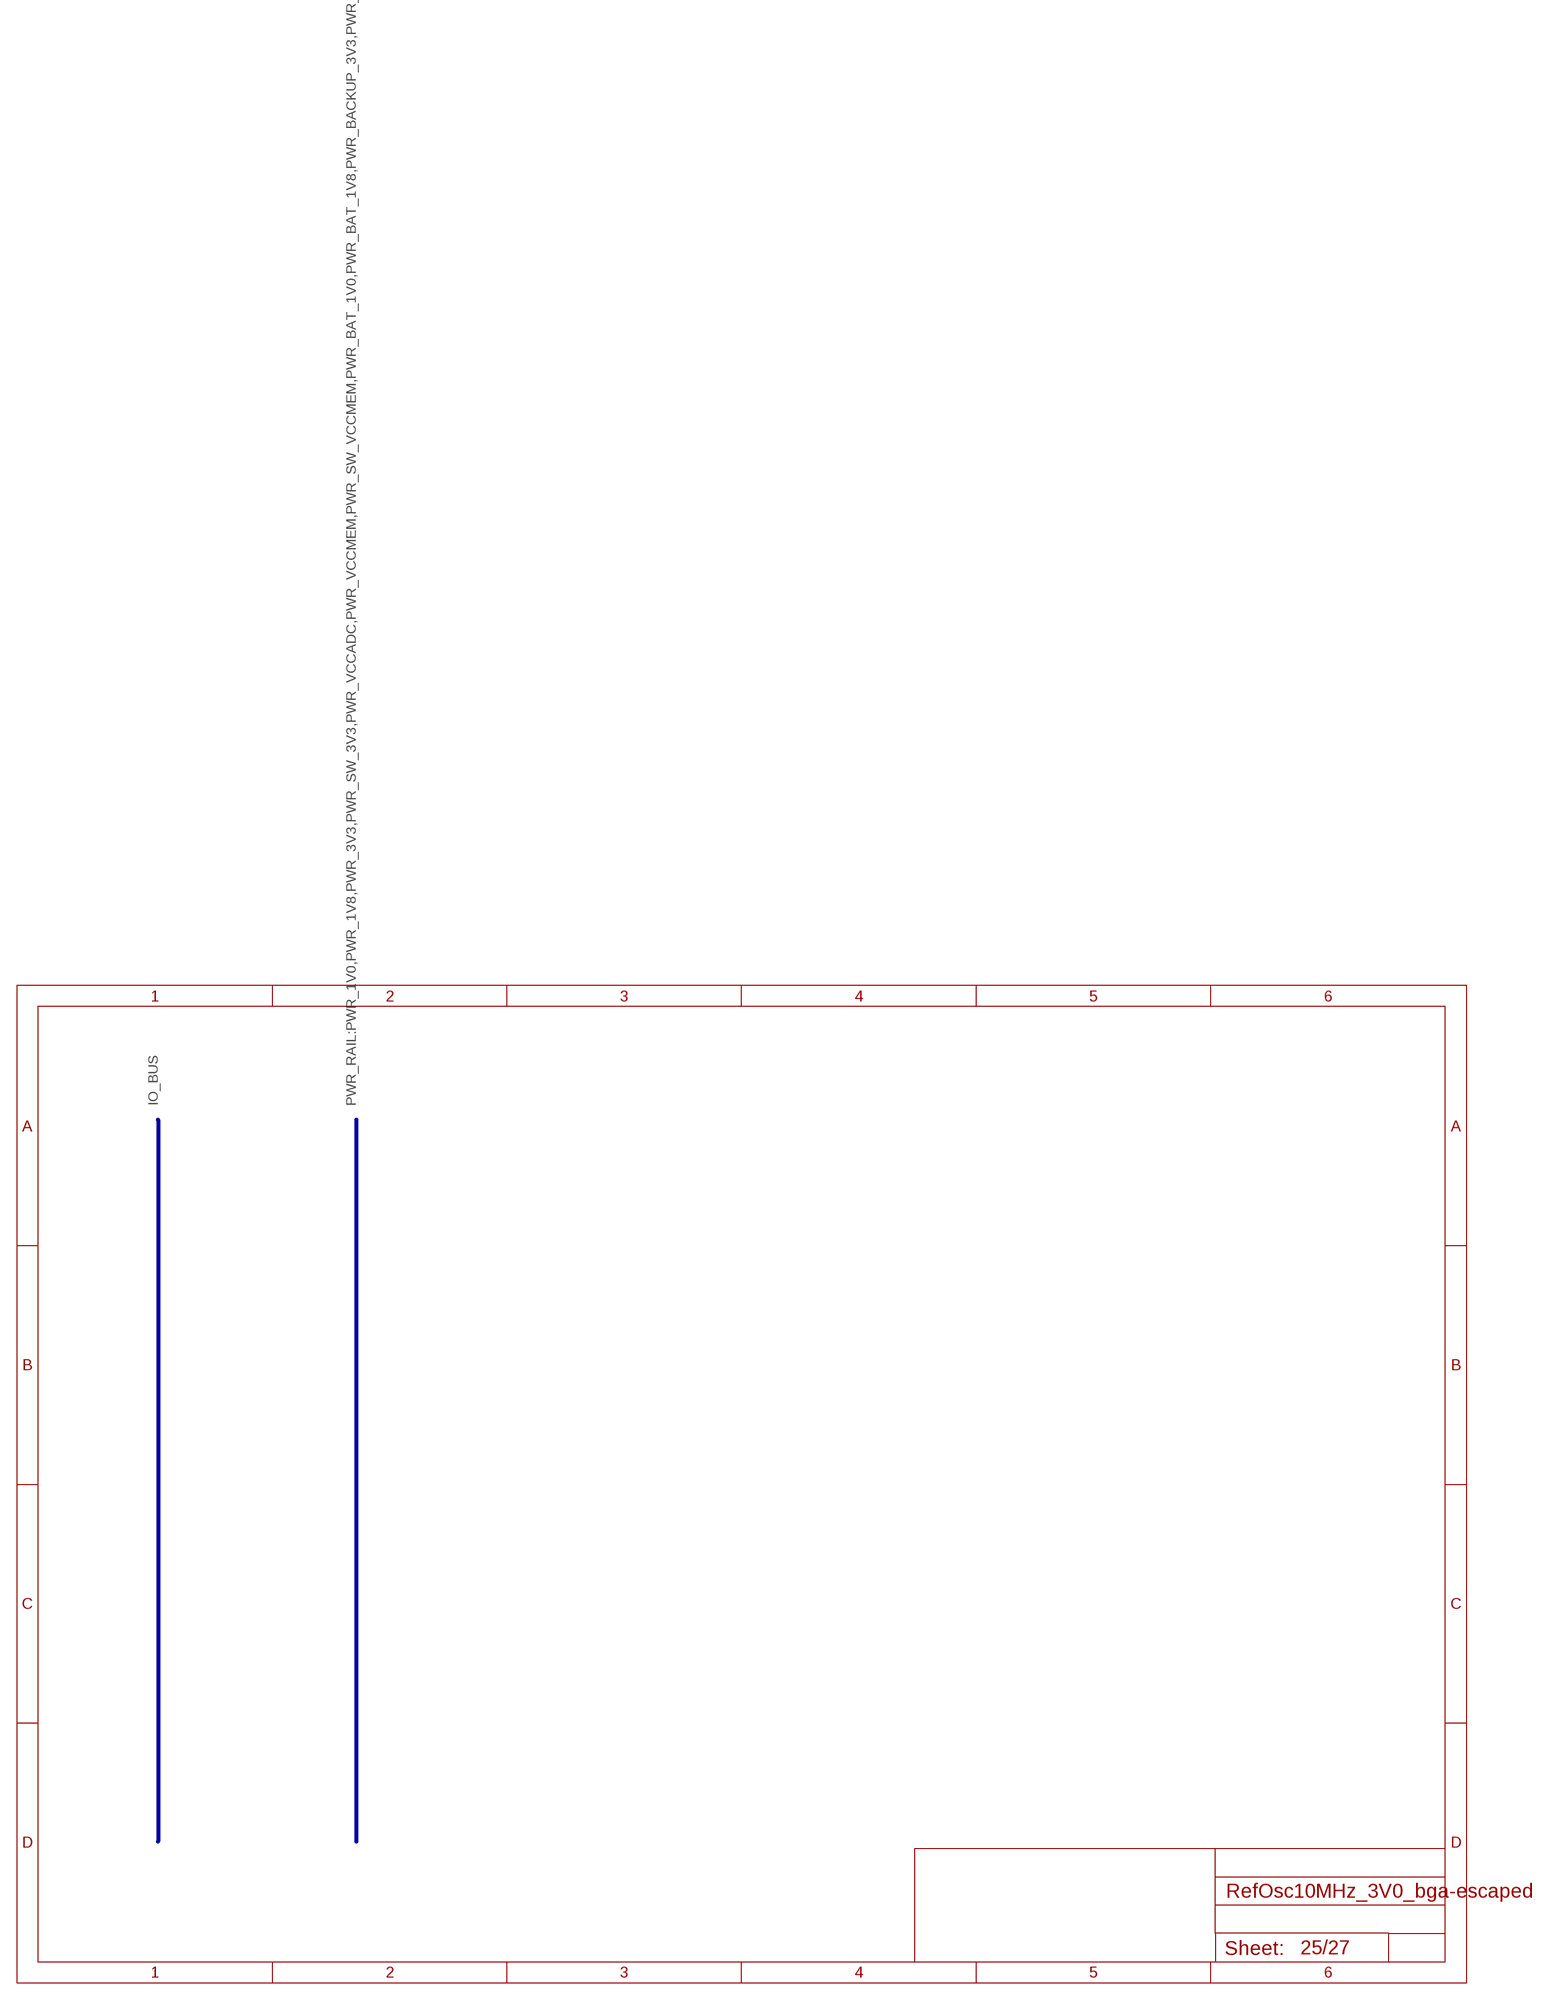
[diagram p24: schematic, sheet 25]
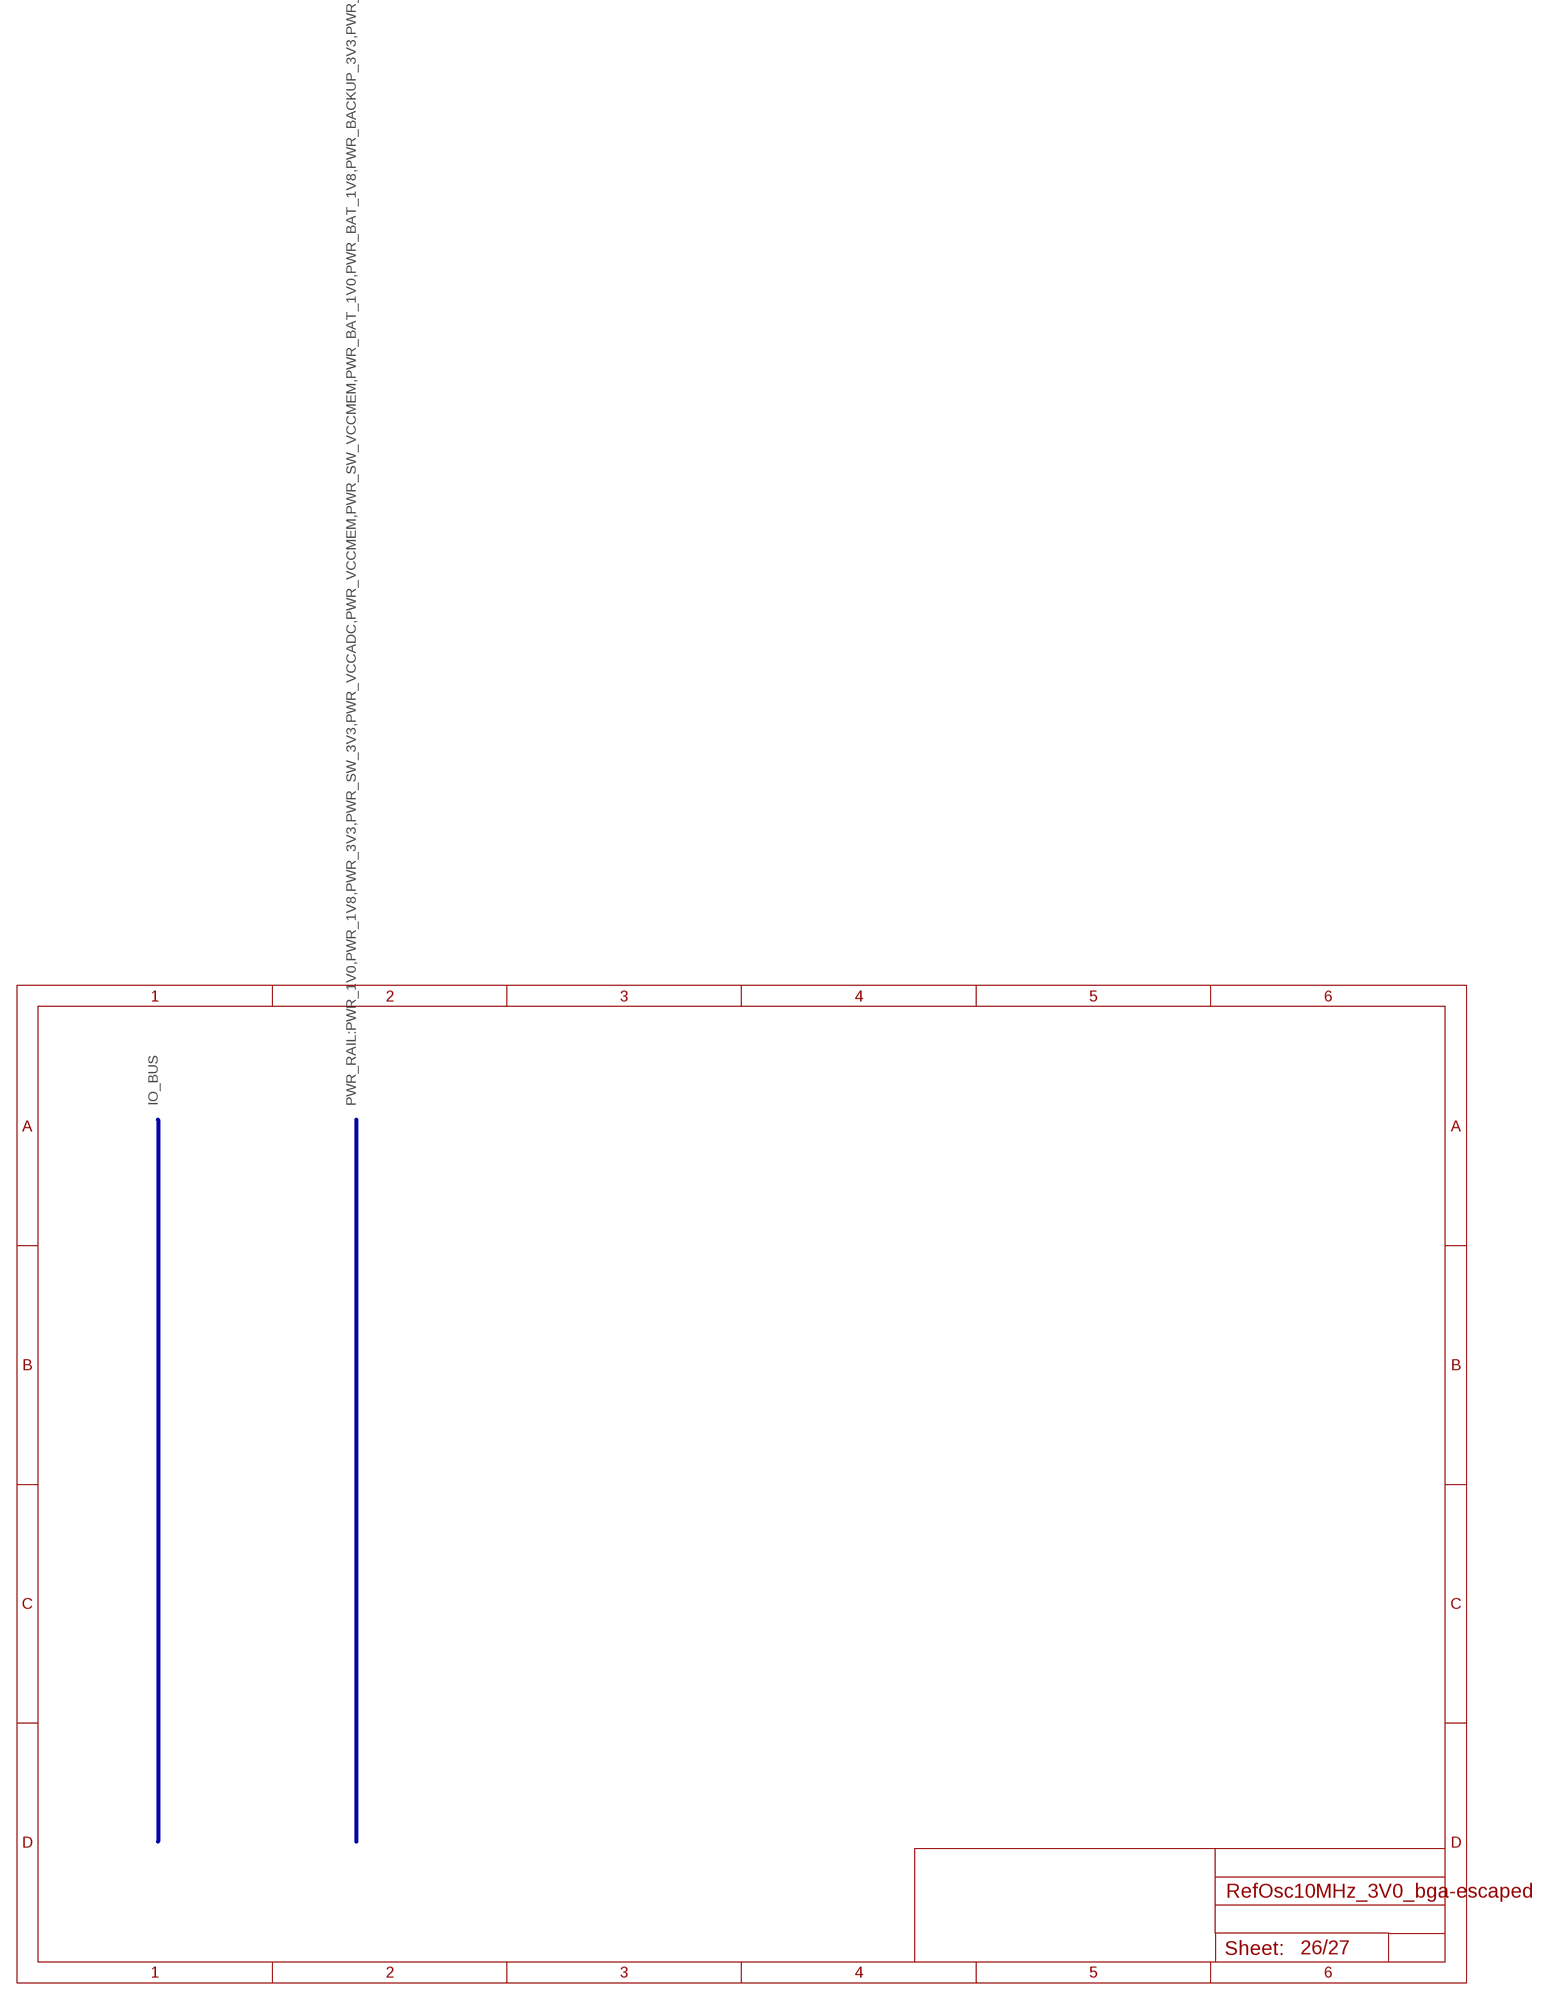
[diagram p25: schematic, sheet 26]
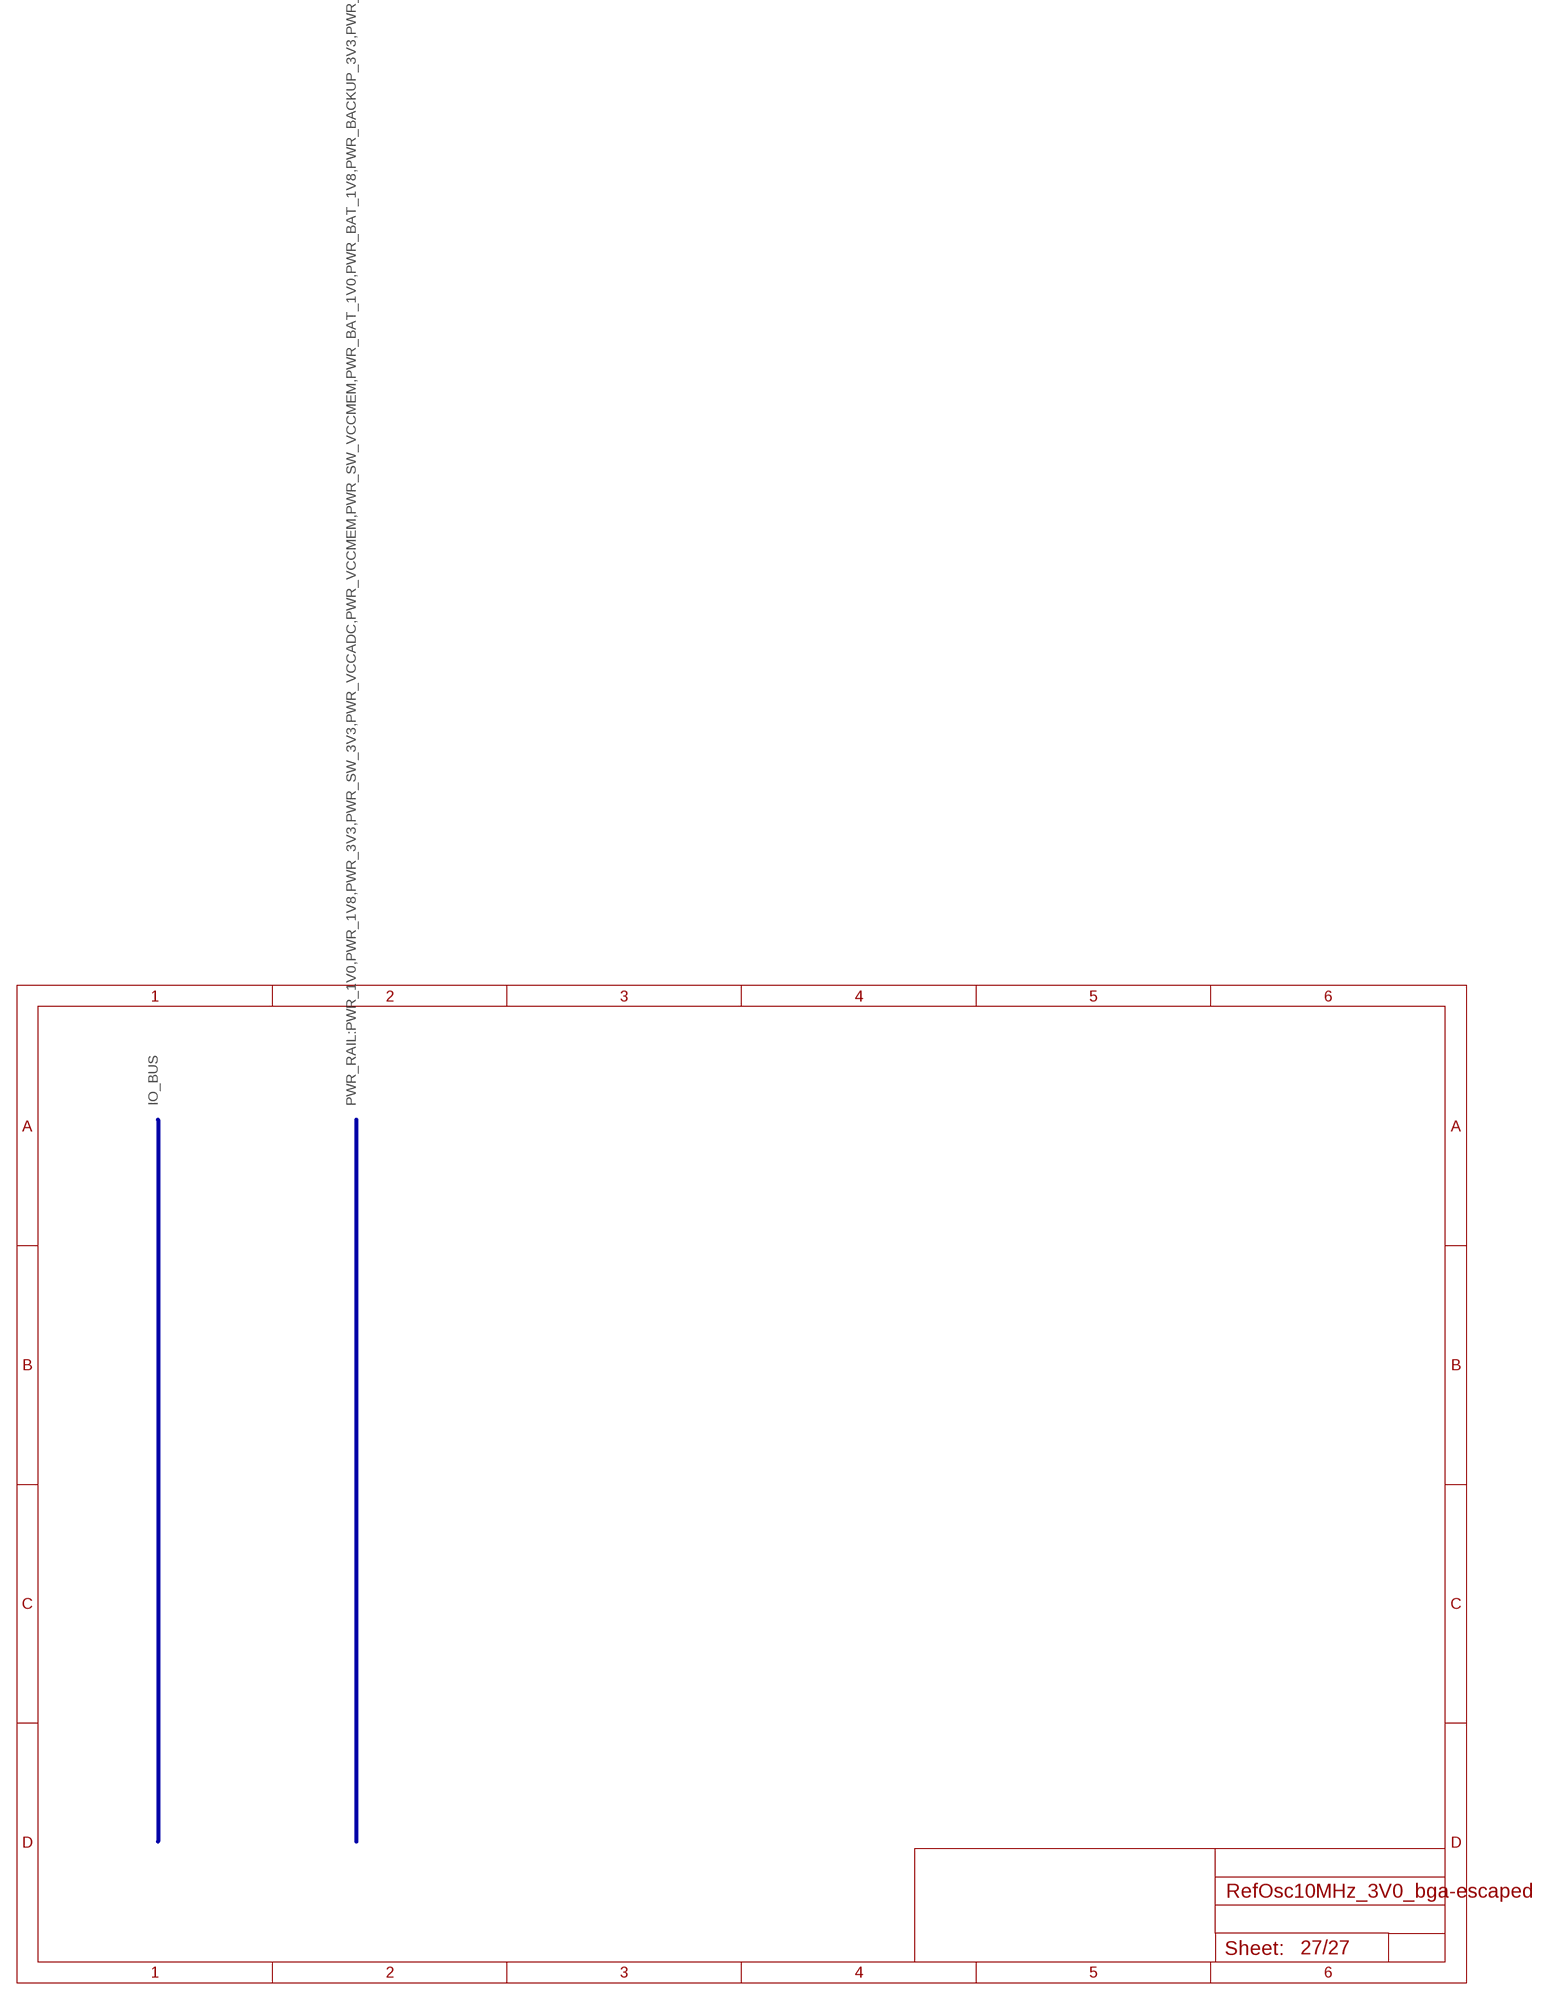
[diagram p26: schematic, sheet 27]

(export (version "E")
  (design (tool "Eeschema 10.0.6"))
  (components
    (comp (ref "C1001")
      (value "100uF")
      (footprint "eagle-import:C1206")
      (libsource (lib "eagle-import") (part "rcl_C-EUC1206"))
    )
    (comp (ref "C1002")
      (value "4.7uF")
      (footprint "eagle-import:C0402")
      (libsource (lib "eagle-import") (part "rcl_C-EUC0402"))
    )
    (comp (ref "C1003")
      (value "4.7uF")
      (footprint "eagle-import:C0402")
      (libsource (lib "eagle-import") (part "rcl_C-EUC0402"))
    )
    (comp (ref "C1004")
      (value "0.47uF")
      (footprint "eagle-import:C0402")
      (libsource (lib "eagle-import") (part "rcl_C-EUC0402"))
    )
    (comp (ref "C1005")
      (value "0.47uF")
      (footprint "eagle-import:C0402")
      (libsource (lib "eagle-import") (part "rcl_C-EUC0402"))
    )
    (comp (ref "C1006")
      (value "0.47uF")
      (footprint "eagle-import:C0402")
      (libsource (lib "eagle-import") (part "rcl_C-EUC0402"))
    )
    (comp (ref "C1011")
      (value "47uF")
      (footprint "eagle-import:C0805")
      (libsource (lib "eagle-import") (part "rcl_C-EUC0805"))
    )
    (comp (ref "C1012")
      (value "0.47uF")
      (footprint "eagle-import:C0402")
      (libsource (lib "eagle-import") (part "rcl_C-EUC0402"))
    )
    (comp (ref "C1021")
      (value "47uF")
      (footprint "eagle-import:C0805")
      (libsource (lib "eagle-import") (part "rcl_C-EUC0805"))
    )
    (comp (ref "C1022")
      (value "4.7uF")
      (footprint "eagle-import:C0402")
      (libsource (lib "eagle-import") (part "rcl_C-EUC0402"))
    )
    (comp (ref "C1023")
      (value "4.7uF")
      (footprint "eagle-import:C0402")
      (libsource (lib "eagle-import") (part "rcl_C-EUC0402"))
    )
    (comp (ref "C1024")
      (value "0.47uF")
      (footprint "eagle-import:C0402")
      (libsource (lib "eagle-import") (part "rcl_C-EUC0402"))
    )
    (comp (ref "C1025")
      (value "0.47uF")
      (footprint "eagle-import:C0402")
      (libsource (lib "eagle-import") (part "rcl_C-EUC0402"))
    )
    (comp (ref "C1026")
      (value "0.47uF")
      (footprint "eagle-import:C0402")
      (libsource (lib "eagle-import") (part "rcl_C-EUC0402"))
    )
    (comp (ref "R101")
      (value "0")
      (footprint "eagle-import:R0402")
      (libsource (lib "eagle-import") (part "R-EU_R0402"))
    )
    (comp (ref "R102")
      (value "0")
      (footprint "eagle-import:R0402")
      (libsource (lib "eagle-import") (part "R-EU_R0402"))
    )
    (comp (ref "R103")
      (value "0")
      (footprint "eagle-import:R0402")
      (libsource (lib "eagle-import") (part "R-EU_R0402"))
    )
    (comp (ref "R104")
      (value "0")
      (footprint "eagle-import:R0402")
      (libsource (lib "eagle-import") (part "R-EU_R0402"))
    )
    (comp (ref "R105")
      (value "0")
      (footprint "eagle-import:R0402")
      (libsource (lib "eagle-import") (part "R-EU_R0402"))
    )
    (comp (ref "U0401")
      (value "XC7A35TFTG256")
      (footprint "eagle-import:FTG256_0MM4")
      (libsource (lib "eagle-import") (part "XC7A35TFTG256"))
    )
    (comp (ref "H191")
      (value "MOUNT-PAD-ROUND2.8")
      (footprint "eagle-import:2,8-PAD")
      (libsource (lib "eagle-import") (part "MOUNT-PAD-ROUND2.8"))
    )
    (comp (ref "H192")
      (value "MOUNT-PAD-ROUND2.8")
      (footprint "eagle-import:2,8-PAD")
      (libsource (lib "eagle-import") (part "MOUNT-PAD-ROUND2.8"))
    )
    (comp (ref "H193")
      (value "MOUNT-PAD-ROUND2.8")
      (footprint "eagle-import:2,8-PAD")
      (libsource (lib "eagle-import") (part "MOUNT-PAD-ROUND2.8"))
    )
    (comp (ref "H194")
      (value "MOUNT-PAD-ROUND2.8")
      (footprint "eagle-import:2,8-PAD")
      (libsource (lib "eagle-import") (part "MOUNT-PAD-ROUND2.8"))
    )
    (comp (ref "C0211")
      (value "4.7uF")
      (footprint "eagle-import:C0805")
      (libsource (lib "eagle-import") (part "rcl_C-EUC0805"))
    )
    (comp (ref "C0212")
      (value "22uF")
      (footprint "eagle-import:C0805")
      (libsource (lib "eagle-import") (part "rcl_C-EUC0805"))
    )
    (comp (ref "C0221")
      (value "4.7uF")
      (footprint "eagle-import:C0805")
      (libsource (lib "eagle-import") (part "rcl_C-EUC0805"))
    )
    (comp (ref "C0222")
      (value "22uF")
      (footprint "eagle-import:C0805")
      (libsource (lib "eagle-import") (part "rcl_C-EUC0805"))
    )
    (comp (ref "C0231")
      (value "4.7uF")
      (footprint "eagle-import:C0805")
      (libsource (lib "eagle-import") (part "rcl_C-EUC0805"))
    )
    (comp (ref "C0232")
      (value "22uF")
      (footprint "eagle-import:C0805")
      (libsource (lib "eagle-import") (part "rcl_C-EUC0805"))
    )
    (comp (ref "C0241")
      (value "4.7uF")
      (footprint "eagle-import:C0805")
      (libsource (lib "eagle-import") (part "rcl_C-EUC0805"))
    )
    (comp (ref "C0242")
      (value "100uF")
      (footprint "eagle-import:C0805")
      (libsource (lib "eagle-import") (part "rcl_C-EUC0805"))
    )
    (comp (ref "C0243")
      (value "100nF")
      (footprint "eagle-import:C0805")
      (libsource (lib "eagle-import") (part "rcl_C-EUC0805"))
    )
    (comp (ref "C0251")
      (value "22uF")
      (footprint "eagle-import:C0805")
      (libsource (lib "eagle-import") (part "rcl_C-EUC0805"))
    )
    (comp (ref "C0261")
      (value "22uF")
      (footprint "eagle-import:C0805")
      (libsource (lib "eagle-import") (part "rcl_C-EUC0805"))
    )
    (comp (ref "C0271")
      (value "4.7uF")
      (footprint "eagle-import:C0805")
      (libsource (lib "eagle-import") (part "rcl_C-EUC0805"))
    )
    (comp (ref "C0272")
      (value "4.7uF")
      (footprint "eagle-import:C0805")
      (libsource (lib "eagle-import") (part "rcl_C-EUC0805"))
    )
    (comp (ref "C0273")
      (value "0.22F")
      (footprint "eagle-import:PANASONIC_C")
      (libsource (lib "eagle-import") (part "CPOL-EUC"))
    )
    (comp (ref "C0281")
      (value "22uF")
      (footprint "eagle-import:C0805")
      (libsource (lib "eagle-import") (part "rcl_C-EUC0805"))
    )
    (comp (ref "C0282")
      (value "22uF")
      (footprint "eagle-import:C0805")
      (libsource (lib "eagle-import") (part "rcl_C-EUC0805"))
    )
    (comp (ref "C0283")
      (value "22uF")
      (footprint "eagle-import:C0805")
      (libsource (lib "eagle-import") (part "rcl_C-EUC0805"))
    )
    (comp (ref "C0291")
      (value "1uF")
      (footprint "eagle-import:C0805")
      (libsource (lib "eagle-import") (part "rcl_C-EUC0805"))
    )
    (comp (ref "C0292")
      (value "100nF")
      (footprint "eagle-import:C0805")
      (libsource (lib "eagle-import") (part "rcl_C-EUC0805"))
    )
    (comp (ref "D0271")
      (value "CRS08")
      (footprint "eagle-import:SOT23")
      (libsource (lib "eagle-import") (part "ZENER-DIODESOT23"))
    )
    (comp (ref "L021")
      (value "1.5uH")
      (footprint "eagle-import:L1812")
      (libsource (lib "eagle-import") (part "rcl_L-EUL1812"))
    )
    (comp (ref "L022")
      (value "1.5uH")
      (footprint "eagle-import:L1812")
      (libsource (lib "eagle-import") (part "rcl_L-EUL1812"))
    )
    (comp (ref "L023")
      (value "1.5uH")
      (footprint "eagle-import:L1812")
      (libsource (lib "eagle-import") (part "rcl_L-EUL1812"))
    )
    (comp (ref "L024")
      (value "1.5uH")
      (footprint "eagle-import:L1812")
      (libsource (lib "eagle-import") (part "rcl_L-EUL1812"))
    )
    (comp (ref "L025")
      (value "10uH")
      (footprint "eagle-import:L1812")
      (libsource (lib "eagle-import") (part "rcl_L-EUL1812"))
    )
    (comp (ref "L026")
      (value "10uH")
      (footprint "eagle-import:L1812")
      (libsource (lib "eagle-import") (part "rcl_L-EUL1812"))
    )
    (comp (ref "R0271")
      (value "1.5k")
      (footprint "eagle-import:R0603")
      (libsource (lib "eagle-import") (part "R-EU_R0603"))
    )
    (comp (ref "R0272")
      (value "1.5k")
      (footprint "eagle-import:R0603")
      (libsource (lib "eagle-import") (part "R-EU_R0603"))
    )
    (comp (ref "R0281")
      (value "100k")
      (footprint "eagle-import:R0603")
      (libsource (lib "eagle-import") (part "R-EU_R0603"))
    )
    (comp (ref "R0282")
      (value "100k")
      (footprint "eagle-import:R0603")
      (libsource (lib "eagle-import") (part "R-EU_R0603"))
    )
    (comp (ref "R0283")
      (value "100k")
      (footprint "eagle-import:R0603")
      (libsource (lib "eagle-import") (part "R-EU_R0603"))
    )
    (comp (ref "R0284")
      (value "47k")
      (footprint "eagle-import:R0603")
      (libsource (lib "eagle-import") (part "R-EU_R0603"))
    )
    (comp (ref "R0285")
      (value "10k")
      (footprint "eagle-import:R0603")
      (libsource (lib "eagle-import") (part "R-EU_R0603"))
    )
    (comp (ref "R0291")
      (value "100k")
      (footprint "eagle-import:R0603")
      (libsource (lib "eagle-import") (part "R-EU_R0603"))
    )
    (comp (ref "R0292")
      (value "100k")
      (footprint "eagle-import:R0603")
      (libsource (lib "eagle-import") (part "R-EU_R0603"))
    )
    (comp (ref "R0293")
      (value "100k")
      (footprint "eagle-import:R0603")
      (libsource (lib "eagle-import") (part "R-EU_R0603"))
    )
    (comp (ref "R0294")
      (value "100k")
      (footprint "eagle-import:R0603")
      (libsource (lib "eagle-import") (part "R-EU_R0603"))
    )
    (comp (ref "R0299")
      (value "0")
      (footprint "eagle-import:R0805")
      (libsource (lib "eagle-import") (part "R-EU_R0805"))
    )
    (comp (ref "U021")
      (value "TPS65218")
      (footprint "eagle-import:QFP50P900X900X120-49N2")
      (libsource (lib "eagle-import") (part "TPS65218"))
    )
    (comp (ref "R111")
      (value "4.7k")
      (footprint "eagle-import:R0805")
      (libsource (lib "eagle-import") (part "R-EU_R0805"))
    )
    (comp (ref "R112")
      (value "100k")
      (footprint "eagle-import:R0805")
      (libsource (lib "eagle-import") (part "R-EU_R0805"))
    )
    (comp (ref "R113")
      (value "100k")
      (footprint "eagle-import:R0805")
      (libsource (lib "eagle-import") (part "R-EU_R0805"))
    )
    (comp (ref "U111")
      (value "N25Q128A13ESE40F")
      (footprint "eagle-import:SOP2-8")
      (libsource (lib "eagle-import") (part "N25Q128A13ESE40F"))
    )
    (comp (ref "C141")
      (value "47uF")
      (footprint "eagle-import:C0805")
      (libsource (lib "eagle-import") (part "rcl_C-EUC0805"))
    )
    (comp (ref "C142")
      (value "100n")
      (footprint "eagle-import:C0805")
      (libsource (lib "eagle-import") (part "rcl_C-EUC0805"))
    )
    (comp (ref "CON141")
      (value "TYCO-AMP_USBUSB-B_SMT")
      (footprint "eagle-import:TYCO-AMP_USB-B_SMT")
      (fields (field (name "MF") "TYCO-AMP") (field (name "MPN") "1734346"))
      (libsource (lib "eagle-import") (part "TYCO-AMP_USBUSB-B_SMT"))
    )
    (comp (ref "D141")
      (value "BZX84-C3V6")
      (footprint "eagle-import:TO236")
      (libsource (lib "eagle-import") (part "BZX84CSMD"))
    )
    (comp (ref "D142")
      (value "BZX84-C3V6")
      (footprint "eagle-import:TO236")
      (libsource (lib "eagle-import") (part "BZX84CSMD"))
    )
    (comp (ref "R141")
      (value "68")
      (footprint "eagle-import:R0805")
      (libsource (lib "eagle-import") (part "R-EU_R0805"))
    )
    (comp (ref "R142")
      (value "68")
      (footprint "eagle-import:R0805")
      (libsource (lib "eagle-import") (part "R-EU_R0805"))
    )
    (comp (ref "R143")
      (value "1M")
      (footprint "eagle-import:R0805")
      (libsource (lib "eagle-import") (part "R-EU_R0805"))
    )
    (comp (ref "R144")
      (value "1.5k")
      (footprint "eagle-import:R0805")
      (libsource (lib "eagle-import") (part "R-EU_R0805"))
    )
    (comp (ref "RP141")
      (value "1206L025YR_0.5A")
      (footprint "eagle-import:M1206")
      (libsource (lib "eagle-import") (part "R-EU_M1206"))
    )
    (comp (ref "C062")
      (value "4.7uF")
      (footprint "eagle-import:C0402")
      (libsource (lib "eagle-import") (part "rcl_C-EUC0402"))
    )
    (comp (ref "C063")
      (value "4.7uF")
      (footprint "eagle-import:C0402")
      (libsource (lib "eagle-import") (part "rcl_C-EUC0402"))
    )
    (comp (ref "C064")
      (value "0.47uF")
      (footprint "eagle-import:C0402")
      (libsource (lib "eagle-import") (part "rcl_C-EUC0402"))
    )
    (comp (ref "C065")
      (value "0.47uF")
      (footprint "eagle-import:C0402")
      (libsource (lib "eagle-import") (part "rcl_C-EUC0402"))
    )
    (comp (ref "C066")
      (value "0.47uF")
      (footprint "eagle-import:C0402")
      (libsource (lib "eagle-import") (part "rcl_C-EUC0402"))
    )
    (comp (ref "C067")
      (value "0.47uF")
      (footprint "eagle-import:C0402")
      (libsource (lib "eagle-import") (part "rcl_C-EUC0402"))
    )
    (comp (ref "R061")
      (value "0")
      (footprint "eagle-import:R0402")
      (libsource (lib "eagle-import") (part "R-EU_R0402"))
    )
    (comp (ref "C091")
      (value "4.7uF")
      (footprint "eagle-import:C0402")
      (libsource (lib "eagle-import") (part "rcl_C-EUC0402"))
    )
    (comp (ref "C092")
      (value "0.47uF")
      (footprint "eagle-import:C0402")
      (libsource (lib "eagle-import") (part "rcl_C-EUC0402"))
    )
    (comp (ref "R091")
      (value "0")
      (footprint "eagle-import:R0402")
      (libsource (lib "eagle-import") (part "R-EU_R0402"))
    )
    (comp (ref "C0401")
      (value "47uF")
      (footprint "eagle-import:C0805")
      (libsource (lib "eagle-import") (part "rcl_C-EUC0805"))
    )
    (comp (ref "CON0401")
      (value "AVR-JTAG-10SMD")
      (footprint "eagle-import:2X5SMD")
      (libsource (lib "eagle-import") (part "AVR-JTAG-10SMD"))
    )
    (comp (ref "LED0441")
      (value "LED")
      (footprint "eagle-import:SMARTLED-TTW")
      (libsource (lib "eagle-import") (part "LED"))
    )
    (comp (ref "LED0442")
      (value "LED")
      (footprint "eagle-import:SMARTLED-TTW")
      (libsource (lib "eagle-import") (part "LED"))
    )
    (comp (ref "R0401")
      (value "0")
      (footprint "eagle-import:R0402")
      (libsource (lib "eagle-import") (part "R-EU_R0402"))
    )
    (comp (ref "R0402")
      (value "0")
      (footprint "eagle-import:R0402")
      (libsource (lib "eagle-import") (part "R-EU_R0402"))
    )
    (comp (ref "R0411")
      (value "4.7k")
      (footprint "eagle-import:R0805")
      (libsource (lib "eagle-import") (part "R-EU_R0805"))
    )
    (comp (ref "R0412")
      (value "4.7k")
      (footprint "eagle-import:R0805")
      (libsource (lib "eagle-import") (part "R-EU_R0805"))
    )
    (comp (ref "R0413")
      (value "4.7k")
      (footprint "eagle-import:R0805")
      (libsource (lib "eagle-import") (part "R-EU_R0805"))
    )
    (comp (ref "R0414")
      (value "4.7k")
      (footprint "eagle-import:R0805")
      (libsource (lib "eagle-import") (part "R-EU_R0805"))
    )
    (comp (ref "R0415")
      (value "4.7k")
      (footprint "eagle-import:R0805")
      (libsource (lib "eagle-import") (part "R-EU_R0805"))
    )
    (comp (ref "R0421")
      (value "22")
      (footprint "eagle-import:R0805")
      (libsource (lib "eagle-import") (part "R-EU_R0805"))
    )
    (comp (ref "R0431")
      (value "150")
      (footprint "eagle-import:R0805")
      (libsource (lib "eagle-import") (part "R-EU_R0805"))
    )
    (comp (ref "R0441")
      (value "470")
      (footprint "eagle-import:R0805")
      (libsource (lib "eagle-import") (part "R-EU_R0805"))
    )
    (comp (ref "R0443")
      (value "470")
      (footprint "eagle-import:R0805")
      (libsource (lib "eagle-import") (part "R-EU_R0805"))
    )
    (comp (ref "R0451")
      (value "4.7k")
      (footprint "eagle-import:R0805")
      (libsource (lib "eagle-import") (part "R-EU_R0805"))
    )
    (comp (ref "R0452")
      (value "4.7k")
      (footprint "eagle-import:R0805")
      (libsource (lib "eagle-import") (part "R-EU_R0805"))
    )
    (comp (ref "R0453")
      (value "4.7k")
      (footprint "eagle-import:R0805")
      (libsource (lib "eagle-import") (part "R-EU_R0805"))
    )
    (comp (ref "R0454")
      (value "4.7k")
      (footprint "eagle-import:R0805")
      (libsource (lib "eagle-import") (part "R-EU_R0805"))
    )
    (comp (ref "R0455")
      (value "4.7k")
      (footprint "eagle-import:R0805")
      (libsource (lib "eagle-import") (part "R-EU_R0805"))
    )
    (comp (ref "R0456")
      (value "4.7k")
      (footprint "eagle-import:R0805")
      (libsource (lib "eagle-import") (part "R-EU_R0805"))
    )
    (comp (ref "S0401")
      (value "SWS008")
      (footprint "eagle-import:SMS-008")
      (libsource (lib "eagle-import") (part "SWS008"))
    )
    (comp (ref "CON181")
      (value "MCX-J-P-X-RA-SM1")
      (footprint "eagle-import:MCX-J-P-X-RA-SM1")
      (libsource (lib "eagle-import") (part "MCX-J-P-X-RA-SM1"))
    )
    (comp (ref "CON182")
      (value "SD-73100-0105")
      (footprint "eagle-import:MOLEX_BNC-JACK-50R_SD-73100-0105")
      (fields (field (name "MF") "MOLEX"))
      (libsource (lib "eagle-import") (part "MOLEX_BNC-JACK-50R_SD-73100-0105"))
    )
    (comp (ref "CON183")
      (value "MCX-J-P-X-RA-SM1")
      (footprint "eagle-import:MCX-J-P-X-RA-SM1")
      (libsource (lib "eagle-import") (part "MCX-J-P-X-RA-SM1"))
    )
    (comp (ref "CON184")
      (value "MCX-J-P-X-RA-SM1")
      (footprint "eagle-import:MCX-J-P-X-RA-SM1")
      (libsource (lib "eagle-import") (part "MCX-J-P-X-RA-SM1"))
    )
    (comp (ref "CON185")
      (value "MCX-J-P-X-RA-SM1")
      (footprint "eagle-import:MCX-J-P-X-RA-SM1")
      (libsource (lib "eagle-import") (part "MCX-J-P-X-RA-SM1"))
    )
    (comp (ref "CON186")
      (value "MCX-J-P-X-RA-SM1")
      (footprint "eagle-import:MCX-J-P-X-RA-SM1")
      (libsource (lib "eagle-import") (part "MCX-J-P-X-RA-SM1"))
    )
    (comp (ref "R181")
      (value "51")
      (footprint "eagle-import:R0805")
      (libsource (lib "eagle-import") (part "R-EU_R0805"))
    )
    (comp (ref "R182")
      (value "120")
      (footprint "eagle-import:R0805")
      (libsource (lib "eagle-import") (part "R-EU_R0805"))
    )
    (comp (ref "R183")
      (value "120")
      (footprint "eagle-import:R0805")
      (libsource (lib "eagle-import") (part "R-EU_R0805"))
    )
    (comp (ref "U181")
      (value "OPA357")
      (footprint "eagle-import:SOT-23-6")
      (fields (field (name "MPN") "OPA357AIDBVTG4"))
      (libsource (lib "eagle-import") (part "OPA357"))
    )
    (comp (ref "C082")
      (value "4.7uF")
      (footprint "eagle-import:C0402")
      (libsource (lib "eagle-import") (part "rcl_C-EUC0402"))
    )
    (comp (ref "C083")
      (value "4.7uF")
      (footprint "eagle-import:C0402")
      (libsource (lib "eagle-import") (part "rcl_C-EUC0402"))
    )
    (comp (ref "C084")
      (value "0.47uF")
      (footprint "eagle-import:C0402")
      (libsource (lib "eagle-import") (part "rcl_C-EUC0402"))
    )
    (comp (ref "C085")
      (value "0.47uF")
      (footprint "eagle-import:C0402")
      (libsource (lib "eagle-import") (part "rcl_C-EUC0402"))
    )
    (comp (ref "C086")
      (value "0.47uF")
      (footprint "eagle-import:C0402")
      (libsource (lib "eagle-import") (part "rcl_C-EUC0402"))
    )
    (comp (ref "C087")
      (value "0.47uF")
      (footprint "eagle-import:C0402")
      (libsource (lib "eagle-import") (part "rcl_C-EUC0402"))
    )
    (comp (ref "R081")
      (value "0")
      (footprint "eagle-import:R0402")
      (libsource (lib "eagle-import") (part "R-EU_R0402"))
    )
    (comp (ref "C031")
      (value "100n")
      (footprint "eagle-import:C0805")
      (libsource (lib "eagle-import") (part "rcl_C-EUC0805"))
    )
    (comp (ref "C032")
      (value "10uF")
      (footprint "eagle-import:C0805")
      (libsource (lib "eagle-import") (part "rcl_C-EUC0805"))
    )
    (comp (ref "D031")
      (value "BZX84-C3V0")
      (footprint "eagle-import:TO236")
      (libsource (lib "eagle-import") (part "BZX84CSMD"))
    )
    (comp (ref "D032")
      (value "BZX84-C3V6")
      (footprint "eagle-import:TO236")
      (libsource (lib "eagle-import") (part "BZX84CSMD"))
    )
    (comp (ref "D033")
      (value "BZX84-C3V6")
      (footprint "eagle-import:TO236")
      (libsource (lib "eagle-import") (part "BZX84CSMD"))
    )
    (comp (ref "R031")
      (value "56")
      (footprint "eagle-import:R0805")
      (libsource (lib "eagle-import") (part "R-EU_R0805"))
    )
    (comp (ref "R034")
      (value "15k")
      (footprint "eagle-import:R0603")
      (libsource (lib "eagle-import") (part "R-EU_R0603"))
    )
    (comp (ref "U031")
      (value "CFPT-141")
      (footprint "eagle-import:CFPT-141")
      (fields (field (name "MF") "IQD-FREQUENCY-PRODUCTS") (field (name "MPN") "LFTVXO022175"))
      (libsource (lib "eagle-import") (part "CFPT-141"))
    )
    (comp (ref "C151")
      (value "100n")
      (footprint "eagle-import:C0805")
      (libsource (lib "eagle-import") (part "C-EUC0805"))
    )
    (comp (ref "CON151")
      (value "HEADER-2X5SMD")
      (footprint "eagle-import:2X5SMD")
      (libsource (lib "eagle-import") (part "HEADER-2X5SMD"))
    )
    (comp (ref "LP151")
      (value "WE-CBF_300R")
      (footprint "eagle-import:L3216C")
      (libsource (lib "eagle-import") (part "L-EUL3216C"))
    )
    (comp (ref "R151")
      (value "100k")
      (footprint "eagle-import:R0805")
      (libsource (lib "eagle-import") (part "R-EU_R0805"))
    )
    (comp (ref "R152")
      (value "100k")
      (footprint "eagle-import:R0805")
      (libsource (lib "eagle-import") (part "R-EU_R0805"))
    )
    (comp (ref "RP151")
      (value "1206L012WR_0.1A")
      (footprint "eagle-import:M1206")
      (libsource (lib "eagle-import") (part "R-EU_M1206"))
    )
    (comp (ref "U151")
      (value "TJ1513MTBD")
      (footprint "eagle-import:TJ1513MTBD")
      (libsource (lib "eagle-import") (part "TJ1513MTBD"))
    )
    (comp (ref "C051")
      (value "100uF")
      (footprint "eagle-import:C1206")
      (libsource (lib "eagle-import") (part "rcl_C-EUC1206"))
    )
    (comp (ref "C052")
      (value "4.7uF")
      (footprint "eagle-import:C0402")
      (libsource (lib "eagle-import") (part "rcl_C-EUC0402"))
    )
    (comp (ref "C053")
      (value "4.7uF")
      (footprint "eagle-import:C0402")
      (libsource (lib "eagle-import") (part "rcl_C-EUC0402"))
    )
    (comp (ref "C054")
      (value "0.47uF")
      (footprint "eagle-import:C0402")
      (libsource (lib "eagle-import") (part "rcl_C-EUC0402"))
    )
    (comp (ref "C055")
      (value "0.47uF")
      (footprint "eagle-import:C0402")
      (libsource (lib "eagle-import") (part "rcl_C-EUC0402"))
    )
    (comp (ref "C056")
      (value "0.47uF")
      (footprint "eagle-import:C0402")
      (libsource (lib "eagle-import") (part "rcl_C-EUC0402"))
    )
    (comp (ref "C057")
      (value "0.47uF")
      (footprint "eagle-import:C0402")
      (libsource (lib "eagle-import") (part "rcl_C-EUC0402"))
    )
    (comp (ref "CON051")
      (value "HEADER-2X3SMD")
      (footprint "eagle-import:2X03SMD")
      (libsource (lib "eagle-import") (part "HEADER-2X3SMD"))
    )
    (comp (ref "R051")
      (value "0")
      (footprint "eagle-import:R0402")
      (libsource (lib "eagle-import") (part "R-EU_R0402"))
    )
    (comp (ref "C071")
      (value "4.7uF")
      (footprint "eagle-import:C0402")
      (libsource (lib "eagle-import") (part "rcl_C-EUC0402"))
    )
    (comp (ref "C072")
      (value "0.47uF")
      (footprint "eagle-import:C0402")
      (libsource (lib "eagle-import") (part "rcl_C-EUC0402"))
    )
    (comp (ref "C073")
      (value "0.47uF")
      (footprint "eagle-import:C0402")
      (libsource (lib "eagle-import") (part "rcl_C-EUC0402"))
    )
    (comp (ref "R071")
      (value "0")
      (footprint "eagle-import:R0402")
      (libsource (lib "eagle-import") (part "R-EU_R0402"))
    )
  )
  (nets
    (net (code "310") (name "AD4N") (class "Default")
      (node (ref "U0401") (pin "A7") (pinfunction "IO_L1N_T0_AD4N_35_A7") (pintype "bidirectional"))
    )
    (net (code "311") (name "AD4P") (class "Default")
      (node (ref "U0401") (pin "B7") (pinfunction "IO_L1P_T0_AD4P_35_B7") (pintype "bidirectional"))
    )
    (net (code "312") (name "AD5N") (class "Default")
      (node (ref "U0401") (pin "A4") (pinfunction "IO_L3N_T0_DQS_AD5N_35_A4") (pintype "bidirectional"))
    )
    (net (code "313") (name "AD5P") (class "Default")
      (node (ref "U0401") (pin "A5") (pinfunction "IO_L3P_T0_DQS_AD5P_35_A5") (pintype "bidirectional"))
    )
    (net (code "314") (name "AD12N") (class "Default")
      (node (ref "U0401") (pin "B5") (pinfunction "IO_L2N_T0_AD12N_35_B5") (pintype "bidirectional"))
    )
    (net (code "315") (name "AD12P") (class "Default")
      (node (ref "U0401") (pin "B6") (pinfunction "IO_L2P_T0_AD12P_35_B6") (pintype "bidirectional"))
    )
    (net (code "316") (name "AGND") (class "Default")
      (node (ref "R0299") (pin "1") (pinfunction "1_1") (pintype "passive"))
      (node (ref "U0401") (pin "G7") (pinfunction "GNDADC_0_G7") (pintype "bidirectional"))
      (node (ref "U0401") (pin "H7") (pinfunction "VREFN_0_H7") (pintype "bidirectional"))
      (node (ref "U0401") (pin "J7") (pinfunction "VN_0_J7") (pintype "bidirectional"))
    )
    (net (code "317") (name "DAC1B0") (class "Default")
      (node (ref "U0401") (pin "A3") (pinfunction "IO_L4N_T0_35_A3") (pintype "bidirectional"))
    )
    (net (code "318") (name "DAC1B1") (class "Default")
      (node (ref "U0401") (pin "C7") (pinfunction "IO_L5P_T0_AD13P_35_C7") (pintype "bidirectional"))
    )
    (net (code "319") (name "DAC1B2") (class "Default")
      (node (ref "U0401") (pin "C6") (pinfunction "IO_L5N_T0_AD13N_35_C6") (pintype "bidirectional"))
    )
    (net (code "320") (name "DAC1B3") (class "Default")
      (node (ref "U0401") (pin "D6") (pinfunction "IO_L6P_T0_35_D6") (pintype "bidirectional"))
    )
    (net (code "321") (name "DAC1B4") (class "Default")
      (node (ref "U0401") (pin "D5") (pinfunction "IO_L6N_T0_VREF_35_D5") (pintype "bidirectional"))
    )
    (net (code "322") (name "DAC1B5") (class "Default")
      (node (ref "U0401") (pin "C3") (pinfunction "IO_L7P_T1_AD6P_35_C3") (pintype "bidirectional"))
    )
    (net (code "323") (name "DAC1B6") (class "Default")
      (node (ref "U0401") (pin "C2") (pinfunction "IO_L7N_T1_AD6N_35_C2") (pintype "bidirectional"))
    )
    (net (code "324") (name "DAC1B7") (class "Default")
      (node (ref "U0401") (pin "B2") (pinfunction "IO_L8P_T1_AD14P_35_B2") (pintype "bidirectional"))
    )
    (net (code "325") (name "DAC1B8") (class "Default")
      (node (ref "U0401") (pin "A2") (pinfunction "IO_L8N_T1_AD14N_35_A2") (pintype "bidirectional"))
    )
    (net (code "326") (name "DAC1B9") (class "Default")
      (node (ref "U0401") (pin "C1") (pinfunction "IO_L9P_T1_DQS_AD7P_35_C1") (pintype "bidirectional"))
    )
    (net (code "327") (name "DAC1C") (class "Default")
      (node (ref "U0401") (pin "B4") (pinfunction "IO_L4P_T0_35_B4") (pintype "bidirectional"))
    )
    (net (code "328") (name "DAC1G0") (class "Default")
      (node (ref "U0401") (pin "P3") (pinfunction "IO_L5N_T0_34_P3") (pintype "bidirectional"))
    )
    (net (code "329") (name "DAC1G1") (class "Default")
      (node (ref "U0401") (pin "M5") (pinfunction "IO_L6P_T0_34_M5") (pintype "bidirectional"))
    )
    (net (code "330") (name "DAC1G2") (class "Default")
      (node (ref "U0401") (pin "N4") (pinfunction "IO_L6N_T0_VREF_34_N4") (pintype "bidirectional"))
    )
    (net (code "331") (name "DAC1G3") (class "Default")
      (node (ref "U0401") (pin "R2") (pinfunction "IO_L7P_T1_34_R2") (pintype "bidirectional"))
    )
    (net (code "332") (name "DAC1G4") (class "Default")
      (node (ref "U0401") (pin "R1") (pinfunction "IO_L7N_T1_34_R1") (pintype "bidirectional"))
    )
    (net (code "333") (name "DAC1G5") (class "Default")
      (node (ref "U0401") (pin "R3") (pinfunction "IO_L8P_T1_34_R3") (pintype "bidirectional"))
    )
    (net (code "334") (name "DAC1G6") (class "Default")
      (node (ref "U0401") (pin "T2") (pinfunction "IO_L8N_T1_34_T2") (pintype "bidirectional"))
    )
    (net (code "335") (name "DAC1G7") (class "Default")
      (node (ref "U0401") (pin "T4") (pinfunction "IO_L9P_T1_DQS_34_T4") (pintype "bidirectional"))
    )
    (net (code "336") (name "DAC1G8") (class "Default")
      (node (ref "U0401") (pin "T3") (pinfunction "IO_L9N_T1_DQS_34_T3") (pintype "bidirectional"))
    )
    (net (code "337") (name "DAC1G9") (class "Default")
      (node (ref "U0401") (pin "P5") (pinfunction "IO_L10P_T1_34_P5") (pintype "bidirectional"))
    )
    (net (code "338") (name "DAC1NPS") (class "Default")
      (node (ref "U0401") (pin "E6") (pinfunction "IO_0_35_E6") (pintype "bidirectional"))
    )
    (net (code "339") (name "DAC1R0") (class "Default")
      (node (ref "U0401") (pin "L5") (pinfunction "IO_0_34_L5") (pintype "bidirectional"))
    )
    (net (code "340") (name "DAC1R1") (class "Default")
      (node (ref "U0401") (pin "L4") (pinfunction "IO_L1P_T0_34_L4") (pintype "bidirectional"))
    )
    (net (code "341") (name "DAC1R2") (class "Default")
      (node (ref "U0401") (pin "M4") (pinfunction "IO_L1N_T0_34_M4") (pintype "bidirectional"))
    )
    (net (code "342") (name "DAC1R3") (class "Default")
      (node (ref "U0401") (pin "M2") (pinfunction "IO_L2P_T0_34_M2") (pintype "bidirectional"))
    )
    (net (code "343") (name "DAC1R4") (class "Default")
      (node (ref "U0401") (pin "M1") (pinfunction "IO_L2N_T0_34_M1") (pintype "bidirectional"))
    )
    (net (code "344") (name "DAC1R5") (class "Default")
      (node (ref "U0401") (pin "N3") (pinfunction "IO_L3P_T0_DQS_34_N3") (pintype "bidirectional"))
    )
    (net (code "345") (name "DAC1R6") (class "Default")
      (node (ref "U0401") (pin "N2") (pinfunction "IO_L3N_T0_DQS_34_N2") (pintype "bidirectional"))
    )
    (net (code "346") (name "DAC1R7") (class "Default")
      (node (ref "U0401") (pin "N1") (pinfunction "IO_L4P_T0_34_N1") (pintype "bidirectional"))
    )
    (net (code "347") (name "DAC1R8") (class "Default")
      (node (ref "U0401") (pin "P1") (pinfunction "IO_L4N_T0_34_P1") (pintype "bidirectional"))
    )
    (net (code "348") (name "DAC1R9") (class "Default")
      (node (ref "U0401") (pin "P4") (pinfunction "IO_L5P_T0_34_P4") (pintype "bidirectional"))
    )
    (net (code "349") (name "DAC2B0") (class "Default")
      (node (ref "U0401") (pin "H1") (pinfunction "IO_L20N_T3_35_H1") (pintype "bidirectional"))
    )
    (net (code "350") (name "DAC2B1") (class "Default")
      (node (ref "U0401") (pin "J3") (pinfunction "IO_L21P_T3_DQS_35_J3") (pintype "bidirectional"))
    )
    (net (code "351") (name "DAC2B2") (class "Default")
      (node (ref "U0401") (pin "H3") (pinfunction "IO_L21N_T3_DQS_35_H3") (pintype "bidirectional"))
    )
    (net (code "352") (name "DAC2B3") (class "Default")
      (node (ref "U0401") (pin "K1") (pinfunction "IO_L22P_T3_35_K1") (pintype "bidirectional"))
    )
    (net (code "353") (name "DAC2B4") (class "Default")
      (node (ref "U0401") (pin "J1") (pinfunction "IO_L22N_T3_35_J1") (pintype "bidirectional"))
    )
    (net (code "354") (name "DAC2B5") (class "Default")
      (node (ref "U0401") (pin "L3") (pinfunction "IO_L23P_T3_35_L3") (pintype "bidirectional"))
    )
    (net (code "355") (name "DAC2B6") (class "Default")
      (node (ref "U0401") (pin "L2") (pinfunction "IO_L23N_T3_35_L2") (pintype "bidirectional"))
    )
    (net (code "356") (name "DAC2B7") (class "Default")
      (node (ref "U0401") (pin "K3") (pinfunction "IO_L24P_T3_35_K3") (pintype "bidirectional"))
    )
    (net (code "357") (name "DAC2B8") (class "Default")
      (node (ref "U0401") (pin "K2") (pinfunction "IO_L24N_T3_35_K2") (pintype "bidirectional"))
    )
    (net (code "358") (name "DAC2B9") (class "Default")
      (node (ref "U0401") (pin "K5") (pinfunction "IO_25_35_K5") (pintype "bidirectional"))
    )
    (net (code "359") (name "DAC2C") (class "Default")
      (node (ref "U0401") (pin "E2") (pinfunction "IO_L10P_T1_AD15P_35_E2") (pintype "bidirectional"))
    )
    (net (code "360") (name "DAC2G0") (class "Default")
      (node (ref "U0401") (pin "E1") (pinfunction "IO_L15N_T2_DQS_35_E1") (pintype "bidirectional"))
    )
    (net (code "361") (name "DAC2G1") (class "Default")
      (node (ref "U0401") (pin "G5") (pinfunction "IO_L16P_T2_35_G5") (pintype "bidirectional"))
    )
    (net (code "362") (name "DAC2G2") (class "Default")
      (node (ref "U0401") (pin "G4") (pinfunction "IO_L16N_T2_35_G4") (pintype "bidirectional"))
    )
    (net (code "363") (name "DAC2G3") (class "Default")
      (node (ref "U0401") (pin "G2") (pinfunction "IO_L17P_T2_35_G2") (pintype "bidirectional"))
    )
    (net (code "364") (name "DAC2G4") (class "Default")
      (node (ref "U0401") (pin "G1") (pinfunction "IO_L17N_T2_35_G1") (pintype "bidirectional"))
    )
    (net (code "365") (name "DAC2G5") (class "Default")
      (node (ref "U0401") (pin "H5") (pinfunction "IO_L18P_T2_35_H5") (pintype "bidirectional"))
    )
    (net (code "366") (name "DAC2G6") (class "Default")
      (node (ref "U0401") (pin "H4") (pinfunction "IO_L18N_T2_35_H4") (pintype "bidirectional"))
    )
    (net (code "367") (name "DAC2G7") (class "Default")
      (node (ref "U0401") (pin "J5") (pinfunction "IO_L19P_T3_35_J5") (pintype "bidirectional"))
    )
    (net (code "368") (name "DAC2G8") (class "Default")
      (node (ref "U0401") (pin "J4") (pinfunction "IO_L19N_T3_VREF_35_J4") (pintype "bidirectional"))
    )
    (net (code "369") (name "DAC2G9") (class "Default")
      (node (ref "U0401") (pin "H2") (pinfunction "IO_L20P_T3_35_H2") (pintype "bidirectional"))
    )
    (net (code "370") (name "DAC2NPS") (class "Default")
      (node (ref "U0401") (pin "B1") (pinfunction "IO_L9N_T1_DQS_AD7N_35_B1") (pintype "bidirectional"))
    )
    (net (code "371") (name "DAC2R0") (class "Default")
      (node (ref "U0401") (pin "D1") (pinfunction "IO_L10N_T1_AD15N_35_D1") (pintype "bidirectional"))
    )
    (net (code "372") (name "DAC2R1") (class "Default")
      (node (ref "U0401") (pin "E3") (pinfunction "IO_L11P_T1_SRCC_35_E3") (pintype "bidirectional"))
    )
    (net (code "373") (name "DAC2R2") (class "Default")
      (node (ref "U0401") (pin "D3") (pinfunction "IO_L11N_T1_SRCC_35_D3") (pintype "bidirectional"))
    )
    (net (code "374") (name "DAC2R3") (class "Default")
      (node (ref "U0401") (pin "D4") (pinfunction "IO_L12P_T1_MRCC_35_D4") (pintype "bidirectional"))
    )
    (net (code "375") (name "DAC2R4") (class "Default")
      (node (ref "U0401") (pin "C4") (pinfunction "IO_L12N_T1_MRCC_35_C4") (pintype "bidirectional"))
    )
    (net (code "376") (name "DAC2R5") (class "Default")
      (node (ref "U0401") (pin "F5") (pinfunction "IO_L13P_T2_MRCC_35_F5") (pintype "bidirectional"))
    )
    (net (code "377") (name "DAC2R6") (class "Default")
      (node (ref "U0401") (pin "E5") (pinfunction "IO_L13N_T2_MRCC_35_E5") (pintype "bidirectional"))
    )
    (net (code "378") (name "DAC2R7") (class "Default")
      (node (ref "U0401") (pin "F4") (pinfunction "IO_L14P_T2_SRCC_35_F4") (pintype "bidirectional"))
    )
    (net (code "379") (name "DAC2R8") (class "Default")
      (node (ref "U0401") (pin "F3") (pinfunction "IO_L14N_T2_SRCC_35_F3") (pintype "bidirectional"))
    )
    (net (code "380") (name "DAC2R9") (class "Default")
      (node (ref "U0401") (pin "F2") (pinfunction "IO_L15P_T2_DQS_35_F2") (pintype "bidirectional"))
    )
    (net (code "381") (name "FPGA_ADC_VP_0") (class "Default")
      (node (ref "U0401") (pin "H8") (pinfunction "VP_0_H8") (pintype "bidirectional"))
    )
    (net (code "382") (name "FPGA_CFG_0") (class "Default")
      (node (ref "R0456") (pin "1") (pinfunction "1_1") (pintype "passive"))
      (node (ref "S0401") (pin "11") (pinfunction "11_11") (pintype "passive"))
      (node (ref "U0401") (pin "P10") (pinfunction "IO_L14P_T2_SRCC_14_P10") (pintype "bidirectional"))
    )
    (net (code "383") (name "FPGA_CFG_1") (class "Default")
      (node (ref "R0455") (pin "1") (pinfunction "1_1") (pintype "passive"))
      (node (ref "S0401") (pin "12") (pinfunction "12_12") (pintype "passive"))
      (node (ref "U0401") (pin "P11") (pinfunction "IO_L14N_T2_SRCC_14_P11") (pintype "bidirectional"))
    )
    (net (code "384") (name "FPGA_CFG_2") (class "Default")
      (node (ref "R0454") (pin "1") (pinfunction "1_1") (pintype "passive"))
      (node (ref "S0401") (pin "13") (pinfunction "13_13") (pintype "passive"))
      (node (ref "U0401") (pin "R12") (pinfunction "IO_L15P_T2_DQS_RDWR_B_14_R12") (pintype "bidirectional"))
    )
    (net (code "385") (name "FPGA_CFG_3") (class "Default")
      (node (ref "R0453") (pin "1") (pinfunction "1_1") (pintype "passive"))
      (node (ref "S0401") (pin "14") (pinfunction "14_14") (pintype "passive"))
      (node (ref "U0401") (pin "T13") (pinfunction "IO_L16N_T2_A15_D31_14_T13") (pintype "bidirectional"))
    )
    (net (code "386") (name "FPGA_CFG_4") (class "Default")
      (node (ref "R0452") (pin "1") (pinfunction "1_1") (pintype "passive"))
      (node (ref "S0401") (pin "15") (pinfunction "15_15") (pintype "passive"))
      (node (ref "U0401") (pin "R10") (pinfunction "IO_L17P_T2_A14_D30_14_R10") (pintype "bidirectional"))
    )
    (net (code "387") (name "FPGA_CFG_5") (class "Default")
      (node (ref "R0451") (pin "1") (pinfunction "1_1") (pintype "passive"))
      (node (ref "S0401") (pin "16") (pinfunction "16_16") (pintype "passive"))
      (node (ref "U0401") (pin "R11") (pinfunction "IO_L17N_T2_A13_D29_14_R11") (pintype "bidirectional"))
    )
    (net (code "388") (name "FPGA_JTAG_TCK") (class "Default")
      (node (ref "CON0401") (pin "1") (pinfunction "1_1") (pintype "passive"))
      (node (ref "R0412") (pin "2") (pinfunction "2_2") (pintype "passive"))
      (node (ref "U0401") (pin "L7") (pinfunction "TCK_0_L7") (pintype "input"))
    )
    (net (code "389") (name "FPGA_JTAG_TDI") (class "Default")
      (node (ref "CON0401") (pin "9") (pinfunction "9_9") (pintype "passive"))
      (node (ref "R0414") (pin "2") (pinfunction "2_2") (pintype "passive"))
      (node (ref "U0401") (pin "N7") (pinfunction "TDI_0_N7") (pintype "input"))
    )
    (net (code "390") (name "FPGA_JTAG_TDO") (class "Default")
      (node (ref "CON0401") (pin "3") (pinfunction "3_3") (pintype "passive"))
      (node (ref "U0401") (pin "N8") (pinfunction "TDO_0_N8") (pintype "output"))
    )
    (net (code "391") (name "FPGA_JTAG_TMS") (class "Default")
      (node (ref "CON0401") (pin "5") (pinfunction "5_5") (pintype "passive"))
      (node (ref "R0413") (pin "2") (pinfunction "2_2") (pintype "passive"))
      (node (ref "U0401") (pin "M7") (pinfunction "TMS_0_M7") (pintype "input"))
    )
    (net (code "392") (name "FPGA_RS0") (class "Default")
      (node (ref "U0401") (pin "G15") (pinfunction "IO_L24N_T3_RS0_15_G15") (pintype "bidirectional"))
    )
    (net (code "393") (name "FPGA_RS1") (class "Default")
      (node (ref "U0401") (pin "H14") (pinfunction "IO_L24P_T3_RS1_15_H14") (pintype "bidirectional"))
    )
    (net (code "394") (name "FPGA_SPI_CCLK") (class "Default")
      (node (ref "R0421") (pin "2") (pinfunction "2_2") (pintype "passive"))
      (node (ref "U111") (pin "6") (pinfunction "C_6") (pintype "input"))
    )
    (net (code "395") (name "FPGA_SPI_D00_MOSI") (class "Default")
      (node (ref "U0401") (pin "J13") (pinfunction "IO_L1P_T0_D00_MOSI_14_J13") (pintype "bidirectional"))
      (node (ref "U111") (pin "5") (pinfunction "DQ0_5") (pintype "bidirectional"))
    )
    (net (code "396") (name "FPGA_SPI_D01_DIN") (class "Default")
      (node (ref "U0401") (pin "J14") (pinfunction "IO_L1N_T0_D01_DIN_14_J14") (pintype "bidirectional"))
      (node (ref "U111") (pin "2") (pinfunction "DQ1_2") (pintype "bidirectional"))
    )
    (net (code "397") (name "FPGA_SPI_D02") (class "Default")
      (node (ref "R112") (pin "1") (pinfunction "1_1") (pintype "passive"))
      (node (ref "U0401") (pin "K15") (pinfunction "IO_L2P_T0_D02_14_K15") (pintype "bidirectional"))
      (node (ref "U111") (pin "3") (pinfunction "W#_VPP_DQ2_3") (pintype "bidirectional"))
    )
    (net (code "398") (name "FPGA_SPI_D03") (class "Default")
      (node (ref "R113") (pin "1") (pinfunction "1_1") (pintype "passive"))
      (node (ref "U0401") (pin "K16") (pinfunction "IO_L2N_T0_D03_14_K16") (pintype "bidirectional"))
      (node (ref "U111") (pin "7") (pinfunction "HOLD#/DQ3_7") (pintype "bidirectional"))
    )
    (net (code "399") (name "FPGA_SPI_DONE") (class "Default")
      (node (ref "LED0442") (pin "A@1") (pinfunction "A_A@1") (pintype "passive"))
      (node (ref "R0443") (pin "1") (pinfunction "1_1") (pintype "passive"))
      (node (ref "U0401") (pin "H10") (pinfunction "DONE_0_H10") (pintype "bidirectional"))
    )
    (net (code "400") (name "FPGA_SPI_FCS_B#") (class "Default")
      (node (ref "R111") (pin "1") (pinfunction "1_1") (pintype "passive"))
      (node (ref "U0401") (pin "L12") (pinfunction "IO_L6P_T0_FCS_B_14_L12") (pintype "bidirectional"))
      (node (ref "U111") (pin "1") (pinfunction "S#_1") (pintype "input"))
    )
    (net (code "401") (name "FPGA_SPI_INIT_B#") (class "Default")
      (node (ref "CON0401") (pin "6") (pinfunction "6_6") (pintype "passive"))
      (node (ref "R0411") (pin "1") (pinfunction "1_1") (pintype "passive"))
      (node (ref "S0401") (pin "9") (pinfunction "9_9") (pintype "passive"))
      (node (ref "U0401") (pin "K10") (pinfunction "INIT_B_0_K10") (pintype "open_collector"))
    )
    (net (code "402") (name "FPGA_SPI_PROGRAM_B#") (class "Default")
      (node (ref "LED0441") (pin "C@1") (pinfunction "C_C@1") (pintype "passive"))
      (node (ref "R0415") (pin "2") (pinfunction "2_2") (pintype "passive"))
      (node (ref "S0401") (pin "10") (pinfunction "10_10") (pintype "passive"))
      (node (ref "U0401") (pin "L9") (pinfunction "PROGRAM_B_0_L9") (pintype "input"))
    )
    (net (code "403") (name "GND") (class "Default")
      (node (ref "C0211") (pin "2") (pinfunction "2_2") (pintype "passive"))
      (node (ref "C0212") (pin "2") (pinfunction "2_2") (pintype "passive"))
      (node (ref "C0221") (pin "2") (pinfunction "2_2") (pintype "passive"))
      (node (ref "C0222") (pin "2") (pinfunction "2_2") (pintype "passive"))
      (node (ref "C0231") (pin "2") (pinfunction "2_2") (pintype "passive"))
      (node (ref "C0232") (pin "2") (pinfunction "2_2") (pintype "passive"))
      (node (ref "C0241") (pin "2") (pinfunction "2_2") (pintype "passive"))
      (node (ref "C0242") (pin "2") (pinfunction "2_2") (pintype "passive"))
      (node (ref "C0243") (pin "2") (pinfunction "2_2") (pintype "passive"))
      (node (ref "C0251") (pin "2") (pinfunction "2_2") (pintype "passive"))
      (node (ref "C0261") (pin "2") (pinfunction "2_2") (pintype "passive"))
      (node (ref "C0271") (pin "2") (pinfunction "2_2") (pintype "passive"))
      (node (ref "C0272") (pin "2") (pinfunction "2_2") (pintype "passive"))
      (node (ref "C0273") (pin "-") (pinfunction "-_-") (pintype "passive"))
      (node (ref "C0281") (pin "2") (pinfunction "2_2") (pintype "passive"))
      (node (ref "C0282") (pin "2") (pinfunction "2_2") (pintype "passive"))
      (node (ref "C0283") (pin "2") (pinfunction "2_2") (pintype "passive"))
      (node (ref "C0291") (pin "2") (pinfunction "2_2") (pintype "passive"))
      (node (ref "C0292") (pin "2") (pinfunction "2_2") (pintype "passive"))
      (node (ref "C031") (pin "2") (pinfunction "2_2") (pintype "passive"))
      (node (ref "C032") (pin "2") (pinfunction "2_2") (pintype "passive"))
      (node (ref "C0401") (pin "2") (pinfunction "2_2") (pintype "passive"))
      (node (ref "C051") (pin "2") (pinfunction "2_2") (pintype "passive"))
      (node (ref "C052") (pin "2") (pinfunction "2_2") (pintype "passive"))
      (node (ref "C053") (pin "2") (pinfunction "2_2") (pintype "passive"))
      (node (ref "C054") (pin "2") (pinfunction "2_2") (pintype "passive"))
      (node (ref "C055") (pin "2") (pinfunction "2_2") (pintype "passive"))
      (node (ref "C056") (pin "2") (pinfunction "2_2") (pintype "passive"))
      (node (ref "C057") (pin "2") (pinfunction "2_2") (pintype "passive"))
      (node (ref "C062") (pin "2") (pinfunction "2_2") (pintype "passive"))
      (node (ref "C063") (pin "2") (pinfunction "2_2") (pintype "passive"))
      (node (ref "C064") (pin "2") (pinfunction "2_2") (pintype "passive"))
      (node (ref "C065") (pin "2") (pinfunction "2_2") (pintype "passive"))
      (node (ref "C066") (pin "2") (pinfunction "2_2") (pintype "passive"))
      (node (ref "C067") (pin "2") (pinfunction "2_2") (pintype "passive"))
      (node (ref "C071") (pin "2") (pinfunction "2_2") (pintype "passive"))
      (node (ref "C072") (pin "2") (pinfunction "2_2") (pintype "passive"))
      (node (ref "C073") (pin "2") (pinfunction "2_2") (pintype "passive"))
      (node (ref "C082") (pin "2") (pinfunction "2_2") (pintype "passive"))
      (node (ref "C083") (pin "2") (pinfunction "2_2") (pintype "passive"))
      (node (ref "C084") (pin "2") (pinfunction "2_2") (pintype "passive"))
      (node (ref "C085") (pin "2") (pinfunction "2_2") (pintype "passive"))
      (node (ref "C086") (pin "2") (pinfunction "2_2") (pintype "passive"))
      (node (ref "C087") (pin "2") (pinfunction "2_2") (pintype "passive"))
      (node (ref "C091") (pin "2") (pinfunction "2_2") (pintype "passive"))
      (node (ref "C092") (pin "2") (pinfunction "2_2") (pintype "passive"))
      (node (ref "C1001") (pin "2") (pinfunction "2_2") (pintype "passive"))
      (node (ref "C1002") (pin "2") (pinfunction "2_2") (pintype "passive"))
      (node (ref "C1003") (pin "2") (pinfunction "2_2") (pintype "passive"))
      (node (ref "C1004") (pin "2") (pinfunction "2_2") (pintype "passive"))
      (node (ref "C1005") (pin "2") (pinfunction "2_2") (pintype "passive"))
      (node (ref "C1006") (pin "2") (pinfunction "2_2") (pintype "passive"))
      (node (ref "C1011") (pin "2") (pinfunction "2_2") (pintype "passive"))
      (node (ref "C1012") (pin "2") (pinfunction "2_2") (pintype "passive"))
      (node (ref "C1021") (pin "2") (pinfunction "2_2") (pintype "passive"))
      (node (ref "C1022") (pin "2") (pinfunction "2_2") (pintype "passive"))
      (node (ref "C1023") (pin "2") (pinfunction "2_2") (pintype "passive"))
      (node (ref "C1024") (pin "2") (pinfunction "2_2") (pintype "passive"))
      (node (ref "C1025") (pin "2") (pinfunction "2_2") (pintype "passive"))
      (node (ref "C1026") (pin "2") (pinfunction "2_2") (pintype "passive"))
      (node (ref "C141") (pin "2") (pinfunction "2_2") (pintype "passive"))
      (node (ref "C142") (pin "2") (pinfunction "2_2") (pintype "passive"))
      (node (ref "C151") (pin "2") (pinfunction "2_2") (pintype "passive"))
      (node (ref "CON0401") (pin "10") (pinfunction "10_10") (pintype "passive"))
      (node (ref "CON0401") (pin "2") (pinfunction "2_2") (pintype "passive"))
      (node (ref "CON051") (pin "1") (pinfunction "1_1") (pintype "passive"))
      (node (ref "CON051") (pin "6") (pinfunction "6_6") (pintype "passive"))
      (node (ref "CON141") (pin "4") (pinfunction "GND_4") (pintype "bidirectional"))
      (node (ref "CON151") (pin "1") (pinfunction "1_1") (pintype "passive"))
      (node (ref "CON151") (pin "10") (pinfunction "10_10") (pintype "passive"))
      (node (ref "CON151") (pin "9") (pinfunction "9_9") (pintype "passive"))
      (node (ref "CON181") (pin "2") (pinfunction "2_2") (pintype "passive"))
      (node (ref "CON181") (pin "3") (pinfunction "3_3") (pintype "passive"))
      (node (ref "CON181") (pin "4") (pinfunction "4_4") (pintype "passive"))
      (node (ref "CON181") (pin "5") (pinfunction "5_5") (pintype "passive"))
      (node (ref "CON182") (pin "2") (pinfunction "2_2") (pintype "passive"))
      (node (ref "CON182") (pin "3") (pinfunction "3_3") (pintype "passive"))
      (node (ref "CON183") (pin "2") (pinfunction "2_2") (pintype "passive"))
      (node (ref "CON183") (pin "3") (pinfunction "3_3") (pintype "passive"))
      (node (ref "CON183") (pin "4") (pinfunction "4_4") (pintype "passive"))
      (node (ref "CON183") (pin "5") (pinfunction "5_5") (pintype "passive"))
      (node (ref "CON184") (pin "2") (pinfunction "2_2") (pintype "passive"))
      (node (ref "CON184") (pin "3") (pinfunction "3_3") (pintype "passive"))
      (node (ref "CON184") (pin "4") (pinfunction "4_4") (pintype "passive"))
      (node (ref "CON184") (pin "5") (pinfunction "5_5") (pintype "passive"))
      (node (ref "CON185") (pin "2") (pinfunction "2_2") (pintype "passive"))
      (node (ref "CON185") (pin "3") (pinfunction "3_3") (pintype "passive"))
      (node (ref "CON185") (pin "4") (pinfunction "4_4") (pintype "passive"))
      (node (ref "CON185") (pin "5") (pinfunction "5_5") (pintype "passive"))
      (node (ref "CON186") (pin "2") (pinfunction "2_2") (pintype "passive"))
      (node (ref "CON186") (pin "3") (pinfunction "3_3") (pintype "passive"))
      (node (ref "CON186") (pin "4") (pinfunction "4_4") (pintype "passive"))
      (node (ref "CON186") (pin "5") (pinfunction "5_5") (pintype "passive"))
      (node (ref "D031") (pin "A") (pinfunction "A_A") (pintype "passive"))
      (node (ref "D032") (pin "A") (pinfunction "A_A") (pintype "passive"))
      (node (ref "D141") (pin "A") (pinfunction "A_A") (pintype "passive"))
      (node (ref "D142") (pin "A") (pinfunction "A_A") (pintype "passive"))
      (node (ref "H191") (pin "B2,8") (pinfunction "MOUNT_B2,8") (pintype "passive"))
      (node (ref "H192") (pin "B2,8") (pinfunction "MOUNT_B2,8") (pintype "passive"))
      (node (ref "H193") (pin "B2,8") (pinfunction "MOUNT_B2,8") (pintype "passive"))
      (node (ref "H194") (pin "B2,8") (pinfunction "MOUNT_B2,8") (pintype "passive"))
      (node (ref "LED0442") (pin "C@1") (pinfunction "C_C@1") (pintype "passive"))
      (node (ref "R0285") (pin "2") (pinfunction "2_2") (pintype "passive"))
      (node (ref "R0299") (pin "2") (pinfunction "2_2") (pintype "passive"))
      (node (ref "R104") (pin "2") (pinfunction "2_2") (pintype "passive"))
      (node (ref "R105") (pin "2") (pinfunction "2_2") (pintype "passive"))
      (node (ref "R143") (pin "1") (pinfunction "1_1") (pintype "passive"))
      (node (ref "R182") (pin "1") (pinfunction "1_1") (pintype "passive"))
      (node (ref "R183") (pin "1") (pinfunction "1_1") (pintype "passive"))
      (node (ref "S0401") (pin "1") (pinfunction "1_1") (pintype "passive"))
      (node (ref "S0401") (pin "2") (pinfunction "2_2") (pintype "passive"))
      (node (ref "S0401") (pin "3") (pinfunction "3_3") (pintype "passive"))
      (node (ref "S0401") (pin "4") (pinfunction "4_4") (pintype "passive"))
      (node (ref "S0401") (pin "5") (pinfunction "5_5") (pintype "passive"))
      (node (ref "S0401") (pin "6") (pinfunction "6_6") (pintype "passive"))
      (node (ref "S0401") (pin "7") (pinfunction "7_7") (pintype "passive"))
      (node (ref "S0401") (pin "8") (pinfunction "8_8") (pintype "passive"))
      (node (ref "U021") (pin "17") (pinfunction "DC34_SEL_17") (pintype "input"))
      (node (ref "U021") (pin "49") (pinfunction "TPAD_49") (pintype "bidirectional"))
      (node (ref "U031") (pin "2") (pinfunction "GND_2") (pintype "power_in"))
      (node (ref "U0401") (pin "A1") (pinfunction "GND_A1") (pintype "power_in"))
      (node (ref "U0401") (pin "A11") (pinfunction "GND_A11") (pintype "power_in"))
      (node (ref "U0401") (pin "B8") (pinfunction "GND_B8") (pintype "power_in"))
      (node (ref "U0401") (pin "C15") (pinfunction "GND_C15") (pintype "power_in"))
      (node (ref "U0401") (pin "C5") (pinfunction "GND_C5") (pintype "power_in"))
      (node (ref "U0401") (pin "D12") (pinfunction "GND_D12") (pintype "power_in"))
      (node (ref "U0401") (pin "D2") (pinfunction "GND_D2") (pintype "power_in"))
      (node (ref "U0401") (pin "E9") (pinfunction "GND_E9") (pintype "power_in"))
      (node (ref "U0401") (pin "F10") (pinfunction "GND_F10") (pintype "power_in"))
      (node (ref "U0401") (pin "F16") (pinfunction "GND_F16") (pintype "power_in"))
      (node (ref "U0401") (pin "F6") (pinfunction "GND_F6") (pintype "power_in"))
      (node (ref "U0401") (pin "G13") (pinfunction "GND_G13") (pintype "power_in"))
      (node (ref "U0401") (pin "G3") (pinfunction "GND_G3") (pintype "power_in"))
      (node (ref "U0401") (pin "G9") (pinfunction "GND_G9") (pintype "power_in"))
      (node (ref "U0401") (pin "H6") (pinfunction "GND_H6") (pintype "power_in"))
      (node (ref "U0401") (pin "J11") (pinfunction "GND_J11") (pintype "power_in"))
      (node (ref "U0401") (pin "J9") (pinfunction "GND_J9") (pintype "power_in"))
      (node (ref "U0401") (pin "K14") (pinfunction "GND_K14") (pintype "power_in"))
      (node (ref "U0401") (pin "K4") (pinfunction "GND_K4") (pintype "power_in"))
      (node (ref "U0401") (pin "K6") (pinfunction "GND_K6") (pintype "power_in"))
      (node (ref "U0401") (pin "L1") (pinfunction "GND_L1") (pintype "power_in"))
      (node (ref "U0401") (pin "L11") (pinfunction "GND_L11") (pintype "power_in"))
      (node (ref "U0401") (pin "L15") (pinfunction "IO_L3P_T0_DQS_PUDC_B_14_L15") (pintype "bidirectional"))
      (node (ref "U0401") (pin "M10") (pinfunction "M1_0_M10") (pintype "input"))
      (node (ref "U0401") (pin "M11") (pinfunction "M2_0_M11") (pintype "input"))
      (node (ref "U0401") (pin "M8") (pinfunction "GND_M8") (pintype "power_in"))
      (node (ref "U0401") (pin "N15") (pinfunction "GND_N15") (pintype "power_in"))
      (node (ref "U0401") (pin "N5") (pinfunction "GND_N5") (pintype "power_in"))
      (node (ref "U0401") (pin "P12") (pinfunction "GND_P12") (pintype "power_in"))
      (node (ref "U0401") (pin "P2") (pinfunction "GND_P2") (pintype "power_in"))
      (node (ref "U0401") (pin "R9") (pinfunction "GND_R9") (pintype "power_in"))
      (node (ref "U0401") (pin "T16") (pinfunction "GND_T16") (pintype "power_in"))
      (node (ref "U0401") (pin "T6") (pinfunction "GND_T6") (pintype "power_in"))
      (node (ref "U111") (pin "4") (pinfunction "VSS_4") (pintype "power_in"))
      (node (ref "U151") (pin "17") (pinfunction "GND_17") (pintype "power_in"))
      (node (ref "U151") (pin "20") (pinfunction "GND_20") (pintype "power_in"))
      (node (ref "U151") (pin "22") (pinfunction "GND_22") (pintype "power_in"))
      (node (ref "U151") (pin "6") (pinfunction "GND_6") (pintype "power_in"))
      (node (ref "U181") (pin "2") (pinfunction "V-_2") (pintype "power_in"))
    )
    (net (code "404") (name "GPS_2ND_RX") (class "Default")
      (node (ref "U0401") (pin "T15") (pinfunction "IO_L10N_T1_D15_14_T15") (pintype "bidirectional"))
    )
    (net (code "405") (name "GPS_2ND_TX") (class "Default")
      (node (ref "U0401") (pin "T14") (pinfunction "IO_L10P_T1_D14_14_T14") (pintype "bidirectional"))
    )
    (net (code "406") (name "GPS_3DFIX") (class "Default")
      (node (ref "U0401") (pin "N13") (pinfunction "IO_L11P_T1_SRCC_14_N13") (pintype "bidirectional"))
    )
    (net (code "407") (name "GPS_ANT") (class "Default")
      (node (ref "CON181") (pin "1") (pinfunction "1_1") (pintype "passive"))
      (node (ref "LP151") (pin "1") (pinfunction "1_1") (pintype "passive"))
      (node (ref "U151") (pin "21") (pinfunction "RF_IN_21") (pintype "input"))
    )
    (net (code "408") (name "GPS_NMEA_RX") (class "Default")
      (node (ref "CON151") (pin "5") (pinfunction "5_5") (pintype "passive"))
      (node (ref "R152") (pin "1") (pinfunction "1_1") (pintype "passive"))
      (node (ref "U0401") (pin "R16") (pinfunction "IO_L9N_T1_DQS_D13_14_R16") (pintype "bidirectional"))
      (node (ref "U151") (pin "5") (pinfunction "RXD1_5") (pintype "input"))
    )
    (net (code "409") (name "GPS_NMEA_TX") (class "Default")
      (node (ref "CON151") (pin "6") (pinfunction "6_6") (pintype "passive"))
      (node (ref "U0401") (pin "R15") (pinfunction "IO_L9P_T1_DQS_14_R15") (pintype "bidirectional"))
      (node (ref "U151") (pin "4") (pinfunction "TXD1_4") (pintype "output"))
    )
    (net (code "410") (name "GPS_PPS") (class "Default")
      (node (ref "CON151") (pin "7") (pinfunction "7_7") (pintype "passive"))
      (node (ref "U0401") (pin "N11") (pinfunction "IO_L13P_T2_MRCC_14_N11") (pintype "bidirectional"))
      (node (ref "U151") (pin "3") (pinfunction "TIMEPULSE_3") (pintype "output"))
    )
    (net (code "411") (name "GPS_RESET") (class "Default")
      (node (ref "R151") (pin "1") (pinfunction "1_1") (pintype "passive"))
      (node (ref "U0401") (pin "P13") (pinfunction "IO_L11N_T1_SRCC_14_P13") (pintype "bidirectional"))
      (node (ref "U151") (pin "11") (pinfunction "RESET_11") (pintype "passive"))
    )
    (net (code "412") (name "Net-(C051-Pad1)") (class "Default")
      (node (ref "C051") (pin "1") (pinfunction "1_1") (pintype "passive"))
      (node (ref "C052") (pin "1") (pinfunction "1_1") (pintype "passive"))
      (node (ref "C053") (pin "1") (pinfunction "1_1") (pintype "passive"))
      (node (ref "C054") (pin "1") (pinfunction "1_1") (pintype "passive"))
      (node (ref "C055") (pin "1") (pinfunction "1_1") (pintype "passive"))
      (node (ref "C056") (pin "1") (pinfunction "1_1") (pintype "passive"))
      (node (ref "C057") (pin "1") (pinfunction "1_1") (pintype "passive"))
      (node (ref "R051") (pin "1") (pinfunction "1_1") (pintype "passive"))
      (node (ref "U0401") (pin "L16") (pinfunction "VCCO_14_L16") (pintype "input"))
      (node (ref "U0401") (pin "M13") (pinfunction "VCCO_14_M13") (pintype "input"))
      (node (ref "U0401") (pin "N10") (pinfunction "VCCO_14_N10") (pintype "input"))
      (node (ref "U0401") (pin "P7") (pinfunction "VCCO_14_P7") (pintype "input"))
      (node (ref "U0401") (pin "R14") (pinfunction "VCCO_14_R14") (pintype "input"))
      (node (ref "U0401") (pin "T11") (pinfunction "VCCO_14_T11") (pintype "input"))
    )
    (net (code "413") (name "Net-(C062-Pad1)") (class "Default")
      (node (ref "C062") (pin "1") (pinfunction "1_1") (pintype "passive"))
      (node (ref "C063") (pin "1") (pinfunction "1_1") (pintype "passive"))
      (node (ref "C064") (pin "1") (pinfunction "1_1") (pintype "passive"))
      (node (ref "C065") (pin "1") (pinfunction "1_1") (pintype "passive"))
      (node (ref "C066") (pin "1") (pinfunction "1_1") (pintype "passive"))
      (node (ref "C067") (pin "1") (pinfunction "1_1") (pintype "passive"))
      (node (ref "R061") (pin "1") (pinfunction "1_1") (pintype "passive"))
      (node (ref "U0401") (pin "A16") (pinfunction "VCCO_15_A16") (pintype "input"))
      (node (ref "U0401") (pin "B13") (pinfunction "VCCO_15_B13") (pintype "input"))
      (node (ref "U0401") (pin "C10") (pinfunction "VCCO_15_C10") (pintype "input"))
      (node (ref "U0401") (pin "E14") (pinfunction "VCCO_15_E14") (pintype "input"))
      (node (ref "U0401") (pin "H15") (pinfunction "VCCO_15_H15") (pintype "input"))
      (node (ref "U0401") (pin "J12") (pinfunction "VCCO_15_J12") (pintype "input"))
    )
    (net (code "414") (name "Net-(C071-Pad1)") (class "Default")
      (node (ref "C071") (pin "1") (pinfunction "1_1") (pintype "passive"))
      (node (ref "C072") (pin "1") (pinfunction "1_1") (pintype "passive"))
      (node (ref "C073") (pin "1") (pinfunction "1_1") (pintype "passive"))
      (node (ref "R071") (pin "1") (pinfunction "1_1") (pintype "passive"))
      (node (ref "U0401") (pin "M3") (pinfunction "VCCO_34_M3") (pintype "input"))
      (node (ref "U0401") (pin "R4") (pinfunction "VCCO_34_R4") (pintype "input"))
      (node (ref "U0401") (pin "T1") (pinfunction "VCCO_34_T1") (pintype "input"))
    )
    (net (code "415") (name "Net-(C082-Pad1)") (class "Default")
      (node (ref "C082") (pin "1") (pinfunction "1_1") (pintype "passive"))
      (node (ref "C083") (pin "1") (pinfunction "1_1") (pintype "passive"))
      (node (ref "C084") (pin "1") (pinfunction "1_1") (pintype "passive"))
      (node (ref "C085") (pin "1") (pinfunction "1_1") (pintype "passive"))
      (node (ref "C086") (pin "1") (pinfunction "1_1") (pintype "passive"))
      (node (ref "C087") (pin "1") (pinfunction "1_1") (pintype "passive"))
      (node (ref "R081") (pin "1") (pinfunction "1_1") (pintype "passive"))
      (node (ref "U0401") (pin "A6") (pinfunction "VCCO_35_A6") (pintype "input"))
      (node (ref "U0401") (pin "B3") (pinfunction "VCCO_35_B3") (pintype "input"))
      (node (ref "U0401") (pin "D7") (pinfunction "VCCO_35_D7") (pintype "input"))
      (node (ref "U0401") (pin "E4") (pinfunction "VCCO_35_E4") (pintype "input"))
      (node (ref "U0401") (pin "F1") (pinfunction "VCCO_35_F1") (pintype "input"))
      (node (ref "U0401") (pin "J2") (pinfunction "VCCO_35_J2") (pintype "input"))
    )
    (net (code "416") (name "Net-(C1001-Pad1)") (class "Default")
      (node (ref "C1001") (pin "1") (pinfunction "1_1") (pintype "passive"))
      (node (ref "C1002") (pin "1") (pinfunction "1_1") (pintype "passive"))
      (node (ref "C1003") (pin "1") (pinfunction "1_1") (pintype "passive"))
      (node (ref "C1004") (pin "1") (pinfunction "1_1") (pintype "passive"))
      (node (ref "C1005") (pin "1") (pinfunction "1_1") (pintype "passive"))
      (node (ref "C1006") (pin "1") (pinfunction "1_1") (pintype "passive"))
      (node (ref "R101") (pin "1") (pinfunction "1_1") (pintype "passive"))
      (node (ref "U0401") (pin "F7") (pinfunction "VCCINT_F7") (pintype "input"))
      (node (ref "U0401") (pin "F9") (pinfunction "VCCINT_F9") (pintype "input"))
      (node (ref "U0401") (pin "G6") (pinfunction "VCCINT_G6") (pintype "input"))
      (node (ref "U0401") (pin "H9") (pinfunction "VCCINT_H9") (pintype "input"))
      (node (ref "U0401") (pin "J6") (pinfunction "VCCINT_J6") (pintype "input"))
      (node (ref "U0401") (pin "K9") (pinfunction "VCCINT_K9") (pintype "input"))
      (node (ref "U0401") (pin "L8") (pinfunction "VCCINT_L8") (pintype "input"))
    )
    (net (code "417") (name "Net-(C1011-Pad1)") (class "Default")
      (node (ref "C1011") (pin "1") (pinfunction "1_1") (pintype "passive"))
      (node (ref "C1012") (pin "1") (pinfunction "1_1") (pintype "passive"))
      (node (ref "R102") (pin "1") (pinfunction "1_1") (pintype "passive"))
      (node (ref "U0401") (pin "E10") (pinfunction "VCCBRAM_E10") (pintype "input"))
      (node (ref "U0401") (pin "F11") (pinfunction "VCCBRAM_F11") (pintype "input"))
    )
    (net (code "418") (name "Net-(C1021-Pad1)") (class "Default")
      (node (ref "C1021") (pin "1") (pinfunction "1_1") (pintype "passive"))
      (node (ref "C1022") (pin "1") (pinfunction "1_1") (pintype "passive"))
      (node (ref "C1023") (pin "1") (pinfunction "1_1") (pintype "passive"))
      (node (ref "C1024") (pin "1") (pinfunction "1_1") (pintype "passive"))
      (node (ref "C1025") (pin "1") (pinfunction "1_1") (pintype "passive"))
      (node (ref "C1026") (pin "1") (pinfunction "1_1") (pintype "passive"))
      (node (ref "R103") (pin "1") (pinfunction "1_1") (pintype "passive"))
      (node (ref "U0401") (pin "G10") (pinfunction "VCCAUX_G10") (pintype "input"))
      (node (ref "U0401") (pin "J10") (pinfunction "VCCAUX_J10") (pintype "input"))
      (node (ref "U0401") (pin "K11") (pinfunction "VCCAUX_K11") (pintype "input"))
      (node (ref "U0401") (pin "L10") (pinfunction "VCCAUX_L10") (pintype "input"))
    )
    (net (code "419") (name "Net-(CON141-D+)") (class "Default")
      (node (ref "CON141") (pin "3") (pinfunction "D+_3") (pintype "bidirectional"))
      (node (ref "D141") (pin "C") (pinfunction "C_C") (pintype "passive"))
      (node (ref "R141") (pin "1") (pinfunction "1_1") (pintype "passive"))
      (node (ref "R143") (pin "2") (pinfunction "2_2") (pintype "passive"))
    )
    (net (code "420") (name "Net-(CON141-D-)") (class "Default")
      (node (ref "CON141") (pin "2") (pinfunction "D-_2") (pintype "bidirectional"))
      (node (ref "D142") (pin "C") (pinfunction "C_C") (pintype "passive"))
      (node (ref "R142") (pin "1") (pinfunction "1_1") (pintype "passive"))
      (node (ref "R144") (pin "1") (pinfunction "1_1") (pintype "passive"))
    )
    (net (code "421") (name "Net-(CON141-VBUS)") (class "Default")
      (node (ref "CON141") (pin "1") (pinfunction "VBUS_1") (pintype "bidirectional"))
      (node (ref "RP141") (pin "1") (pinfunction "1_1") (pintype "passive"))
    )
    (net (code "422") (name "Net-(CON182-Pad1)") (class "Default")
      (node (ref "CON182") (pin "1") (pinfunction "1_1") (pintype "passive"))
      (node (ref "R181") (pin "2") (pinfunction "2_2") (pintype "passive"))
    )
    (net (code "423") (name "Net-(CON0401-Pad4)") (class "Default")
      (node (ref "CON0401") (pin "4") (pinfunction "4_4") (pintype "passive"))
      (node (ref "R0431") (pin "1") (pinfunction "1_1") (pintype "passive"))
    )
    (net (code "424") (name "Net-(LED0441-A)") (class "Default")
      (node (ref "LED0441") (pin "A@1") (pinfunction "A_A@1") (pintype "passive"))
      (node (ref "R0441") (pin "1") (pinfunction "1_1") (pintype "passive"))
    )
    (net (code "425") (name "Net-(U021-INT_LDO)") (class "Default")
      (node (ref "C0292") (pin "1") (pinfunction "1_1") (pintype "passive"))
      (node (ref "U021") (pin "35") (pinfunction "INT_LDO_35") (pintype "bidirectional"))
    )
    (net (code "426") (name "Net-(U021-L1)") (class "Default")
      (node (ref "L021") (pin "2") (pinfunction "2_2") (pintype "passive"))
      (node (ref "U021") (pin "48") (pinfunction "L1_48") (pintype "output"))
    )
    (net (code "427") (name "Net-(U021-L2)") (class "Default")
      (node (ref "L022") (pin "2") (pinfunction "2_2") (pintype "passive"))
      (node (ref "U021") (pin "42") (pinfunction "L2_42") (pintype "output"))
    )
    (net (code "428") (name "Net-(U021-L3)") (class "Default")
      (node (ref "L023") (pin "1") (pinfunction "1_1") (pintype "passive"))
      (node (ref "U021") (pin "38") (pinfunction "L3_38") (pintype "output"))
    )
    (net (code "429") (name "Net-(U021-L4A)") (class "Default")
      (node (ref "L024") (pin "1") (pinfunction "1_1") (pintype "passive"))
      (node (ref "U021") (pin "13") (pinfunction "L4A_13") (pintype "bidirectional"))
    )
    (net (code "430") (name "Net-(U021-L4B)") (class "Default")
      (node (ref "L024") (pin "2") (pinfunction "2_2") (pintype "passive"))
      (node (ref "U021") (pin "14") (pinfunction "L4B_14") (pintype "bidirectional"))
    )
    (net (code "431") (name "Net-(U021-L5)") (class "Default")
      (node (ref "L025") (pin "2") (pinfunction "2_2") (pintype "passive"))
      (node (ref "U021") (pin "20") (pinfunction "L5_20") (pintype "output"))
    )
    (net (code "432") (name "Net-(U021-L6)") (class "Default")
      (node (ref "L026") (pin "2") (pinfunction "2_2") (pintype "passive"))
      (node (ref "U021") (pin "23") (pinfunction "L6_23") (pintype "output"))
    )
    (net (code "433") (name "Net-(U021-PFI)") (class "Default")
      (node (ref "R0284") (pin "1") (pinfunction "1_1") (pintype "passive"))
      (node (ref "R0285") (pin "1") (pinfunction "1_1") (pintype "passive"))
      (node (ref "U021") (pin "16") (pinfunction "PFI_16") (pintype "input"))
    )
    (net (code "434") (name "Net-(U021-SYS_BU)") (class "Default")
      (node (ref "C0291") (pin "1") (pinfunction "1_1") (pintype "passive"))
      (node (ref "U021") (pin "24") (pinfunction "SYS_BU_24") (pintype "bidirectional"))
    )
    (net (code "435") (name "Net-(U031-VC)") (class "Default")
      (node (ref "C032") (pin "1") (pinfunction "1_1") (pintype "passive"))
      (node (ref "D032") (pin "C") (pinfunction "C_C") (pintype "passive"))
      (node (ref "D033") (pin "A") (pinfunction "A_A") (pintype "passive"))
      (node (ref "R034") (pin "1") (pinfunction "1_1") (pintype "passive"))
      (node (ref "U031") (pin "1") (pinfunction "VC_1") (pintype "input"))
    )
    (net (code "436") (name "Net-(U031-VCC_3V0)") (class "Default")
      (node (ref "C031") (pin "1") (pinfunction "1_1") (pintype "passive"))
      (node (ref "D031") (pin "C") (pinfunction "C_C") (pintype "passive"))
      (node (ref "D033") (pin "C") (pinfunction "C_C") (pintype "passive"))
      (node (ref "R031") (pin "2") (pinfunction "2_2") (pintype "passive"))
      (node (ref "U031") (pin "4") (pinfunction "VCC_3V0_4") (pintype "power_in"))
    )
    (net (code "437") (name "Net-(U151-VCC)") (class "Default")
      (node (ref "C151") (pin "1") (pinfunction "1_1") (pintype "passive"))
      (node (ref "CON151") (pin "4") (pinfunction "4_4") (pintype "passive"))
      (node (ref "R151") (pin "2") (pinfunction "2_2") (pintype "passive"))
      (node (ref "R152") (pin "2") (pinfunction "2_2") (pintype "passive"))
      (node (ref "RP151") (pin "2") (pinfunction "2_2") (pintype "passive"))
      (node (ref "U151") (pin "13") (pinfunction "VCC_13") (pintype "power_in"))
    )
    (net (code "438") (name "Net-(U151-VCC_RF)") (class "Default")
      (node (ref "LP151") (pin "2") (pinfunction "2_2") (pintype "passive"))
      (node (ref "U151") (pin "19") (pinfunction "VCC_RF_19") (pintype "output"))
    )
    (net (code "439") (name "Net-(U181-OUT)") (class "Default")
      (node (ref "R181") (pin "1") (pinfunction "1_1") (pintype "passive"))
      (node (ref "U181") (pin "1") (pinfunction "OUT_1") (pintype "output"))
    )
    (net (code "440") (name "Net-(U0401A-CCLK_0)") (class "Default")
      (node (ref "R0421") (pin "1") (pinfunction "1_1") (pintype "passive"))
      (node (ref "U0401") (pin "E8") (pinfunction "CCLK_0_E8") (pintype "bidirectional"))
    )
    (net (code "441") (name "Net-(U0401A-CFGBVS_0)") (class "Default")
      (node (ref "C0401") (pin "1") (pinfunction "1_1") (pintype "passive"))
      (node (ref "R0402") (pin "1") (pinfunction "1_1") (pintype "passive"))
      (node (ref "R0431") (pin "2") (pinfunction "2_2") (pintype "passive"))
      (node (ref "U0401") (pin "E7") (pinfunction "CFGBVS_0_E7") (pintype "input"))
      (node (ref "U0401") (pin "L6") (pinfunction "VCCO_0_L6") (pintype "input"))
    )
    (net (code "442") (name "Net-(U0401A-VCCBATT_0)") (class "Default")
      (node (ref "R0401") (pin "1") (pinfunction "1_1") (pintype "passive"))
      (node (ref "U0401") (pin "F8") (pinfunction "VCCBATT_0_F8") (pintype "input"))
    )
    (net (code "443") (name "Net-(U0401G-DXN_0)") (class "Default")
      (node (ref "R105") (pin "1") (pinfunction "1_1") (pintype "passive"))
      (node (ref "U0401") (pin "K7") (pinfunction "DXN_0_K7") (pintype "bidirectional"))
    )
    (net (code "444") (name "Net-(U0401G-DXP_0)") (class "Default")
      (node (ref "R104") (pin "1") (pinfunction "1_1") (pintype "passive"))
      (node (ref "U0401") (pin "K8") (pinfunction "DXP_0_K8") (pintype "bidirectional"))
    )
    (net (code "445") (name "Net-(U0401K-VCCADC_0)") (class "Default")
      (node (ref "C091") (pin "1") (pinfunction "1_1") (pintype "passive"))
      (node (ref "C092") (pin "1") (pinfunction "1_1") (pintype "passive"))
      (node (ref "R091") (pin "1") (pinfunction "1_1") (pintype "passive"))
      (node (ref "U0401") (pin "G8") (pinfunction "VCCADC_0_G8") (pintype "input"))
    )
    (net (code "446") (name "PMU_AC_DET") (class "Default")
      (node (ref "R0283") (pin "1") (pinfunction "1_1") (pintype "passive"))
      (node (ref "U021") (pin "9") (pinfunction "AC_DET_9") (pintype "input"))
    )
    (net (code "447") (name "PMU_GPIO1") (class "Default")
      (node (ref "U021") (pin "11") (pinfunction "GPIO1_11") (pintype "bidirectional"))
      (node (ref "U0401") (pin "T10") (pinfunction "IO_L22N_T3_A04_D20_14_T10") (pintype "bidirectional"))
    )
    (net (code "448") (name "PMU_GPIO2") (class "Default")
      (node (ref "U021") (pin "34") (pinfunction "GPIO2_34") (pintype "bidirectional"))
      (node (ref "U0401") (pin "R5") (pinfunction "IO_L23P_T3_A03_D19_14_R5") (pintype "bidirectional"))
    )
    (net (code "449") (name "PMU_GPIO3") (class "Default")
      (node (ref "U021") (pin "26") (pinfunction "GPIO3_26") (pintype "bidirectional"))
      (node (ref "U0401") (pin "T5") (pinfunction "IO_L23N_T3_A02_D18_14_T5") (pintype "bidirectional"))
    )
    (net (code "450") (name "PMU_INT#") (class "Default")
      (node (ref "R0294") (pin "1") (pinfunction "1_1") (pintype "passive"))
      (node (ref "U021") (pin "45") (pinfunction "NINT_45") (pintype "output"))
      (node (ref "U0401") (pin "T9") (pinfunction "IO_L22P_T3_A05_D21_14_T9") (pintype "bidirectional"))
    )
    (net (code "451") (name "PMU_IN_CC#") (class "Default")
      (node (ref "U021") (pin "18") (pinfunction "IN_NCC_18") (pintype "output"))
      (node (ref "U0401") (pin "T8") (pinfunction "IO_L21N_T3_DQS_A06_D22_14_T8") (pintype "bidirectional"))
    )
    (net (code "452") (name "PMU_PB") (class "Default")
      (node (ref "R0282") (pin "1") (pinfunction "1_1") (pintype "passive"))
      (node (ref "U021") (pin "44") (pinfunction "PB_44") (pintype "input"))
    )
    (net (code "453") (name "PMU_PFO#") (class "Default")
      (node (ref "R0291") (pin "1") (pinfunction "1_1") (pintype "passive"))
      (node (ref "U021") (pin "10") (pinfunction "NPFO_10") (pintype "output"))
      (node (ref "U0401") (pin "M6") (pinfunction "IO_L19P_T3_A10_D26_14_M6") (pintype "bidirectional"))
    )
    (net (code "454") (name "PMU_PGOOD") (class "Default")
      (node (ref "R0292") (pin "1") (pinfunction "1_1") (pintype "passive"))
      (node (ref "U021") (pin "8") (pinfunction "PGOOD_8") (pintype "output"))
      (node (ref "U0401") (pin "P8") (pinfunction "IO_L20P_T3_A08_D24_14_P8") (pintype "bidirectional"))
    )
    (net (code "455") (name "PMU_PGOOD_BU") (class "Default")
      (node (ref "U021") (pin "19") (pinfunction "PGOOD_BU_19") (pintype "output"))
      (node (ref "U0401") (pin "R8") (pinfunction "IO_L20N_T3_A07_D23_14_R8") (pintype "bidirectional"))
    )
    (net (code "456") (name "PMU_PWR_EN") (class "Default")
      (node (ref "R0281") (pin "1") (pinfunction "1_1") (pintype "passive"))
      (node (ref "U021") (pin "46") (pinfunction "PWR_EN_46") (pintype "input"))
      (node (ref "U0401") (pin "N9") (pinfunction "IO_L18P_T2_A12_D28_14_N9") (pintype "bidirectional"))
    )
    (net (code "457") (name "PMU_WAKEUP#") (class "Default")
      (node (ref "R0293") (pin "1") (pinfunction "1_1") (pintype "passive"))
      (node (ref "U021") (pin "40") (pinfunction "NWAKEUP_40") (pintype "output"))
      (node (ref "U0401") (pin "P9") (pinfunction "IO_L18N_T2_A11_D27_14_P9") (pintype "bidirectional"))
    )
    (net (code "458") (name "PWR_1V0") (class "Default")
      (node (ref "C0212") (pin "1") (pinfunction "1_1") (pintype "passive"))
      (node (ref "L021") (pin "1") (pinfunction "1_1") (pintype "passive"))
      (node (ref "R101") (pin "2") (pinfunction "2_2") (pintype "passive"))
      (node (ref "R102") (pin "2") (pinfunction "2_2") (pintype "passive"))
      (node (ref "U021") (pin "47") (pinfunction "FB1_47") (pintype "input"))
    )
    (net (code "459") (name "PWR_1V8") (class "Default")
      (node (ref "C0222") (pin "1") (pinfunction "1_1") (pintype "passive"))
      (node (ref "L022") (pin "1") (pinfunction "1_1") (pintype "passive"))
      (node (ref "R103") (pin "2") (pinfunction "2_2") (pintype "passive"))
      (node (ref "U021") (pin "41") (pinfunction "FB2_41") (pintype "input"))
    )
    (net (code "460") (name "PWR_1V25_PREC") (class "Default")
      (node (ref "U0401") (pin "J8") (pinfunction "VREFP_0_J8") (pintype "bidirectional"))
    )
    (net (code "461") (name "PWR_3V3") (class "Default")
      (node (ref "C0242") (pin "1") (pinfunction "1_1") (pintype "passive"))
      (node (ref "C0243") (pin "1") (pinfunction "1_1") (pintype "passive"))
      (node (ref "CON051") (pin "5") (pinfunction "5_5") (pintype "passive"))
      (node (ref "D0271") (pin "1") (pinfunction "A_1") (pintype "passive"))
      (node (ref "R0271") (pin "1") (pinfunction "1_1") (pintype "passive"))
      (node (ref "R0272") (pin "1") (pinfunction "1_1") (pintype "passive"))
      (node (ref "R0291") (pin "2") (pinfunction "2_2") (pintype "passive"))
      (node (ref "R0292") (pin "2") (pinfunction "2_2") (pintype "passive"))
      (node (ref "R0293") (pin "2") (pinfunction "2_2") (pintype "passive"))
      (node (ref "R0294") (pin "2") (pinfunction "2_2") (pintype "passive"))
      (node (ref "R031") (pin "1") (pinfunction "1_1") (pintype "passive"))
      (node (ref "R0402") (pin "2") (pinfunction "2_2") (pintype "passive"))
      (node (ref "R0411") (pin "2") (pinfunction "2_2") (pintype "passive"))
      (node (ref "R0412") (pin "1") (pinfunction "1_1") (pintype "passive"))
      (node (ref "R0413") (pin "1") (pinfunction "1_1") (pintype "passive"))
      (node (ref "R0414") (pin "1") (pinfunction "1_1") (pintype "passive"))
      (node (ref "R0415") (pin "1") (pinfunction "1_1") (pintype "passive"))
      (node (ref "R0441") (pin "2") (pinfunction "2_2") (pintype "passive"))
      (node (ref "R0443") (pin "2") (pinfunction "2_2") (pintype "passive"))
      (node (ref "R0451") (pin "2") (pinfunction "2_2") (pintype "passive"))
      (node (ref "R0452") (pin "2") (pinfunction "2_2") (pintype "passive"))
      (node (ref "R0453") (pin "2") (pinfunction "2_2") (pintype "passive"))
      (node (ref "R0454") (pin "2") (pinfunction "2_2") (pintype "passive"))
      (node (ref "R0455") (pin "2") (pinfunction "2_2") (pintype "passive"))
      (node (ref "R0456") (pin "2") (pinfunction "2_2") (pintype "passive"))
      (node (ref "R051") (pin "2") (pinfunction "2_2") (pintype "passive"))
      (node (ref "R061") (pin "2") (pinfunction "2_2") (pintype "passive"))
      (node (ref "R071") (pin "2") (pinfunction "2_2") (pintype "passive"))
      (node (ref "R081") (pin "2") (pinfunction "2_2") (pintype "passive"))
      (node (ref "R111") (pin "2") (pinfunction "2_2") (pintype "passive"))
      (node (ref "R112") (pin "2") (pinfunction "2_2") (pintype "passive"))
      (node (ref "R113") (pin "2") (pinfunction "2_2") (pintype "passive"))
      (node (ref "RP151") (pin "1") (pinfunction "1_1") (pintype "passive"))
      (node (ref "U021") (pin "15") (pinfunction "DCDC4_15") (pintype "power_in"))
      (node (ref "U021") (pin "5") (pinfunction "IN_LDO1_5") (pintype "power_in"))
      (node (ref "U021") (pin "6") (pinfunction "IN_LS3_6") (pintype "power_in"))
      (node (ref "U0401") (pin "M9") (pinfunction "M0_0_M9") (pintype "input"))
      (node (ref "U111") (pin "8") (pinfunction "VDD_8") (pintype "power_in"))
    )
    (net (code "462") (name "PWR_5V0") (class "Default")
      (node (ref "C0211") (pin "1") (pinfunction "1_1") (pintype "passive"))
      (node (ref "C0221") (pin "1") (pinfunction "1_1") (pintype "passive"))
      (node (ref "C0231") (pin "1") (pinfunction "1_1") (pintype "passive"))
      (node (ref "C0241") (pin "1") (pinfunction "1_1") (pintype "passive"))
      (node (ref "C0271") (pin "1") (pinfunction "1_1") (pintype "passive"))
      (node (ref "C141") (pin "1") (pinfunction "1_1") (pintype "passive"))
      (node (ref "C142") (pin "1") (pinfunction "1_1") (pintype "passive"))
      (node (ref "CON051") (pin "3") (pinfunction "3_3") (pintype "passive"))
      (node (ref "CON151") (pin "3") (pinfunction "3_3") (pintype "passive"))
      (node (ref "R0281") (pin "2") (pinfunction "2_2") (pintype "passive"))
      (node (ref "R0282") (pin "2") (pinfunction "2_2") (pintype "passive"))
      (node (ref "R0283") (pin "2") (pinfunction "2_2") (pintype "passive"))
      (node (ref "R0284") (pin "2") (pinfunction "2_2") (pintype "passive"))
      (node (ref "RP141") (pin "2") (pinfunction "2_2") (pintype "passive"))
      (node (ref "U021") (pin "1") (pinfunction "IN_DCDC1_1") (pintype "power_in"))
      (node (ref "U021") (pin "12") (pinfunction "IN_DCDC4_12") (pintype "power_in"))
      (node (ref "U021") (pin "27") (pinfunction "IN_BU_27") (pintype "power_in"))
      (node (ref "U021") (pin "32") (pinfunction "IN_LS2_32") (pintype "power_in"))
      (node (ref "U021") (pin "36") (pinfunction "IN_BIAS_36") (pintype "bidirectional"))
      (node (ref "U021") (pin "37") (pinfunction "IN_DCDC3_37") (pintype "power_in"))
      (node (ref "U021") (pin "43") (pinfunction "IN_DCDC2_43") (pintype "power_in"))
      (node (ref "U181") (pin "6") (pinfunction "V+_6") (pintype "power_in"))
    )
    (net (code "463") (name "PWR_BACKUP_3V3") (class "Default")
      (node (ref "C0272") (pin "1") (pinfunction "1_1") (pintype "passive"))
      (node (ref "C0273") (pin "+") (pinfunction "+_+") (pintype "passive"))
      (node (ref "CON151") (pin "2") (pinfunction "2_2") (pintype "passive"))
      (node (ref "D0271") (pin "3") (pinfunction "C_3") (pintype "passive"))
      (node (ref "U021") (pin "25") (pinfunction "CC_25") (pintype "bidirectional"))
      (node (ref "U151") (pin "12") (pinfunction "V_BAKP_12") (pintype "power_in"))
    )
    (net (code "464") (name "PWR_BAT_1V0") (class "Default")
      (node (ref "C0251") (pin "1") (pinfunction "1_1") (pintype "passive"))
      (node (ref "L025") (pin "1") (pinfunction "1_1") (pintype "passive"))
      (node (ref "U021") (pin "21") (pinfunction "FB5_21") (pintype "bidirectional"))
    )
    (net (code "465") (name "PWR_BAT_1V8") (class "Default")
      (node (ref "C0261") (pin "1") (pinfunction "1_1") (pintype "passive"))
      (node (ref "L026") (pin "1") (pinfunction "1_1") (pintype "passive"))
      (node (ref "R0401") (pin "2") (pinfunction "2_2") (pintype "passive"))
      (node (ref "U021") (pin "22") (pinfunction "FB6_22") (pintype "bidirectional"))
    )
    (net (code "466") (name "PWR_SW_3V3") (class "Default")
      (node (ref "C0283") (pin "1") (pinfunction "1_1") (pintype "passive"))
      (node (ref "U021") (pin "7") (pinfunction "LS3_7") (pintype "output"))
    )
    (net (code "467") (name "PWR_SW_5V0") (class "Default")
      (node (ref "C0282") (pin "1") (pinfunction "1_1") (pintype "passive"))
      (node (ref "U021") (pin "33") (pinfunction "LS2_33") (pintype "output"))
    )
    (net (code "468") (name "PWR_SW_VCCMEM") (class "Default")
      (node (ref "C0281") (pin "1") (pinfunction "1_1") (pintype "passive"))
      (node (ref "U021") (pin "30") (pinfunction "LS1_30") (pintype "output"))
    )
    (net (code "469") (name "PWR_VCCADC") (class "Default")
      (node (ref "R091") (pin "2") (pinfunction "2_2") (pintype "passive"))
      (node (ref "U021") (pin "4") (pinfunction "LDO1_4") (pintype "output"))
    )
    (net (code "470") (name "PWR_VCCMEM") (class "Default")
      (node (ref "C0232") (pin "1") (pinfunction "1_1") (pintype "passive"))
      (node (ref "L023") (pin "2") (pinfunction "2_2") (pintype "passive"))
      (node (ref "U021") (pin "31") (pinfunction "IN_LS1_31") (pintype "power_in"))
      (node (ref "U021") (pin "39") (pinfunction "FB3_39") (pintype "input"))
    )
    (net (code "471") (name "REFC_10MHZ_EN") (class "Default")
      (node (ref "U0401") (pin "P15") (pinfunction "IO_L8P_T1_D11_14_P15") (pintype "bidirectional"))
      (node (ref "U181") (pin "5") (pinfunction "ENABLE_5") (pintype "input"))
    )
    (net (code "472") (name "REFC_10MHZ_N") (class "Default")
      (node (ref "R183") (pin "2") (pinfunction "2_2") (pintype "passive"))
      (node (ref "U0401") (pin "N16") (pinfunction "IO_L7N_T1_D10_14_N16") (pintype "bidirectional"))
      (node (ref "U181") (pin "4") (pinfunction "-IN_4") (pintype "input"))
    )
    (net (code "473") (name "REFC_10MHZ_P") (class "Default")
      (node (ref "R182") (pin "2") (pinfunction "2_2") (pintype "passive"))
      (node (ref "U0401") (pin "M16") (pinfunction "IO_L7P_T1_D09_14_M16") (pintype "bidirectional"))
      (node (ref "U181") (pin "3") (pinfunction "+IN_3") (pintype "input"))
    )
    (net (code "474") (name "REFC_20MHZ") (class "Default")
      (node (ref "U031") (pin "3") (pinfunction "OUT_3") (pintype "output"))
      (node (ref "U0401") (pin "M15") (pinfunction "IO_L3N_T0_DQS_EMCCLK_14_M15") (pintype "bidirectional"))
      (node (ref "U0401") (pin "N12") (pinfunction "IO_L13N_T2_MRCC_14_N12") (pintype "bidirectional"))
    )
    (net (code "475") (name "SCL") (class "Default")
      (node (ref "CON051") (pin "2") (pinfunction "2_2") (pintype "passive"))
      (node (ref "R0271") (pin "2") (pinfunction "2_2") (pintype "passive"))
      (node (ref "U021") (pin "3") (pinfunction "SCL_3") (pintype "input"))
      (node (ref "U0401") (pin "R6") (pinfunction "IO_L24P_T3_A01_D17_14_R6") (pintype "bidirectional"))
    )
    (net (code "476") (name "SDA") (class "Default")
      (node (ref "CON051") (pin "4") (pinfunction "4_4") (pintype "passive"))
      (node (ref "R0272") (pin "2") (pinfunction "2_2") (pintype "passive"))
      (node (ref "U021") (pin "2") (pinfunction "SDA_2") (pintype "bidirectional"))
      (node (ref "U0401") (pin "R7") (pinfunction "IO_L24N_T3_A00_D16_14_R7") (pintype "bidirectional"))
    )
    (net (code "477") (name "SIG_CH0_I") (class "Default")
      (node (ref "CON183") (pin "1") (pinfunction "1_1") (pintype "passive"))
    )
    (net (code "478") (name "SIG_CH0_Q") (class "Default")
      (node (ref "CON184") (pin "1") (pinfunction "1_1") (pintype "passive"))
    )
    (net (code "479") (name "SIG_CH1_I") (class "Default")
      (node (ref "CON185") (pin "1") (pinfunction "1_1") (pintype "passive"))
    )
    (net (code "480") (name "SIG_CH1_Q") (class "Default")
      (node (ref "CON186") (pin "1") (pinfunction "1_1") (pintype "passive"))
    )
    (net (code "481") (name "USB_DISC") (class "Default")
      (node (ref "R144") (pin "2") (pinfunction "2_2") (pintype "passive"))
      (node (ref "U0401") (pin "K13") (pinfunction "IO_L5P_T0_D06_14_K13") (pintype "bidirectional"))
    )
    (net (code "482") (name "USB_D_MNS") (class "Default")
      (node (ref "R142") (pin "2") (pinfunction "2_2") (pintype "passive"))
      (node (ref "U0401") (pin "M14") (pinfunction "IO_L4N_T0_D05_14_M14") (pintype "bidirectional"))
    )
    (net (code "483") (name "USB_D_PLS") (class "Default")
      (node (ref "R141") (pin "2") (pinfunction "2_2") (pintype "passive"))
      (node (ref "U0401") (pin "L14") (pinfunction "IO_L4P_T0_D04_14_L14") (pintype "bidirectional"))
    )
    (net (code "484") (name "VCTCXO_PWM") (class "Default")
      (node (ref "R034") (pin "2") (pinfunction "2_2") (pintype "passive"))
      (node (ref "U0401") (pin "P6") (pinfunction "IO_25_14_P6") (pintype "bidirectional"))
    )
    (net (code "485") (name "unconnected-(CON151-Pad8)") (class "Default")
      (node (ref "CON151") (pin "8") (pinfunction "8_8") (pintype "passive"))
    )
    (net (code "486") (name "unconnected-(CON0401-Pad7)") (class "Default")
      (node (ref "CON0401") (pin "7") (pinfunction "7_7") (pintype "passive"))
    )
    (net (code "487") (name "unconnected-(CON0401-Pad8)") (class "Default")
      (node (ref "CON0401") (pin "8") (pinfunction "8_8") (pintype "passive"))
    )
    (net (code "488") (name "unconnected-(U151-BOOTSEL-Pad18)") (class "Default")
      (node (ref "U151") (pin "18") (pinfunction "BOOTSEL_18") (pintype "input"))
    )
    (net (code "489") (name "unconnected-(U151-RESERVED-Pad1)") (class "Default")
      (node (ref "U151") (pin "1") (pinfunction "RESERVED_1") (pintype "no_connect"))
    )
    (net (code "490") (name "unconnected-(U151-RESERVED-Pad2)") (class "Default")
      (node (ref "U151") (pin "2") (pinfunction "RESERVED_2") (pintype "no_connect"))
    )
    (net (code "491") (name "unconnected-(U151-RESERVED-Pad7)") (class "Default")
      (node (ref "U151") (pin "7") (pinfunction "RESERVED_7") (pintype "no_connect"))
    )
    (net (code "492") (name "unconnected-(U151-RESERVED-Pad8)") (class "Default")
      (node (ref "U151") (pin "8") (pinfunction "RESERVED_8") (pintype "no_connect"))
    )
    (net (code "493") (name "unconnected-(U151-RESERVED-Pad9)") (class "Default")
      (node (ref "U151") (pin "9") (pinfunction "RESERVED_9") (pintype "no_connect"))
    )
    (net (code "494") (name "unconnected-(U151-RESERVED-Pad10)") (class "Default")
      (node (ref "U151") (pin "10") (pinfunction "RESERVED_10") (pintype "no_connect"))
    )
    (net (code "495") (name "unconnected-(U151-RESERVED-Pad14)") (class "Default")
      (node (ref "U151") (pin "14") (pinfunction "RESERVED_14") (pintype "no_connect"))
    )
    (net (code "496") (name "unconnected-(U151-RESERVED-Pad15)") (class "Default")
      (node (ref "U151") (pin "15") (pinfunction "RESERVED_15") (pintype "no_connect"))
    )
    (net (code "497") (name "unconnected-(U151-RESERVED-Pad16)") (class "Default")
      (node (ref "U151") (pin "16") (pinfunction "RESERVED_16") (pintype "no_connect"))
    )
    (net (code "498") (name "unconnected-(U0401B-IO_0_14-PadK12)") (class "Default")
      (node (ref "U0401") (pin "K12") (pinfunction "IO_0_14_K12") (pintype "bidirectional"))
    )
    (net (code "499") (name "unconnected-(U0401B-IO_L5N_T0_D07_14-PadL13)") (class "Default")
      (node (ref "U0401") (pin "L13") (pinfunction "IO_L5N_T0_D07_14_L13") (pintype "bidirectional"))
    )
    (net (code "500") (name "unconnected-(U0401B-IO_L6N_T0_D08_VREF_14-PadM12)") (class "Default")
      (node (ref "U0401") (pin "M12") (pinfunction "IO_L6N_T0_D08_VREF_14_M12") (pintype "bidirectional"))
    )
    (net (code "501") (name "unconnected-(U0401B-IO_L8N_T1_D12_14-PadP16)") (class "Default")
      (node (ref "U0401") (pin "P16") (pinfunction "IO_L8N_T1_D12_14_P16") (pintype "bidirectional"))
    )
    (net (code "502") (name "unconnected-(U0401B-IO_L12N_T1_MRCC_14-PadP14)") (class "Default")
      (node (ref "U0401") (pin "P14") (pinfunction "IO_L12N_T1_MRCC_14_P14") (pintype "bidirectional"))
    )
    (net (code "503") (name "unconnected-(U0401B-IO_L12P_T1_MRCC_14-PadN14)") (class "Default")
      (node (ref "U0401") (pin "N14") (pinfunction "IO_L12P_T1_MRCC_14_N14") (pintype "bidirectional"))
    )
    (net (code "504") (name "unconnected-(U0401B-IO_L15N_T2_DQS_DOUT_CSO_B_14-PadT12)") (class "Default")
      (node (ref "U0401") (pin "T12") (pinfunction "IO_L15N_T2_DQS_DOUT_CSO_B_14_T12") (pintype "bidirectional"))
    )
    (net (code "505") (name "unconnected-(U0401B-IO_L16P_T2_CSI_B_14-PadR13)") (class "Default")
      (node (ref "U0401") (pin "R13") (pinfunction "IO_L16P_T2_CSI_B_14_R13") (pintype "bidirectional"))
    )
    (net (code "506") (name "unconnected-(U0401B-IO_L19N_T3_A09_D25_VREF_14-PadN6)") (class "Default")
      (node (ref "U0401") (pin "N6") (pinfunction "IO_L19N_T3_A09_D25_VREF_14_N6") (pintype "bidirectional"))
    )
    (net (code "507") (name "unconnected-(U0401B-IO_L21P_T3_DQS_14-PadT7)") (class "Default")
      (node (ref "U0401") (pin "T7") (pinfunction "IO_L21P_T3_DQS_14_T7") (pintype "bidirectional"))
    )
    (net (code "508") (name "unconnected-(U0401C-IO_0_15-PadD10)") (class "Default")
      (node (ref "U0401") (pin "D10") (pinfunction "IO_0_15_D10") (pintype "bidirectional"))
    )
    (net (code "509") (name "unconnected-(U0401C-IO_25_15-PadG11)") (class "Default")
      (node (ref "U0401") (pin "G11") (pinfunction "IO_25_15_G11") (pintype "bidirectional"))
    )
    (net (code "510") (name "unconnected-(U0401C-IO_L1N_T0_AD0N_15-PadC9)") (class "Default")
      (node (ref "U0401") (pin "C9") (pinfunction "IO_L1N_T0_AD0N_15_C9") (pintype "bidirectional"))
    )
    (net (code "511") (name "unconnected-(U0401C-IO_L1P_T0_AD0P_15-PadC8)") (class "Default")
      (node (ref "U0401") (pin "C8") (pinfunction "IO_L1P_T0_AD0P_15_C8") (pintype "bidirectional"))
    )
    (net (code "512") (name "unconnected-(U0401C-IO_L2N_T0_AD8N_15-PadA9)") (class "Default")
      (node (ref "U0401") (pin "A9") (pinfunction "IO_L2N_T0_AD8N_15_A9") (pintype "bidirectional"))
    )
    (net (code "513") (name "unconnected-(U0401C-IO_L2P_T0_AD8P_15-PadA8)") (class "Default")
      (node (ref "U0401") (pin "A8") (pinfunction "IO_L2P_T0_AD8P_15_A8") (pintype "bidirectional"))
    )
    (net (code "514") (name "unconnected-(U0401C-IO_L3N_T0_DQS_AD1N_15-PadA10)") (class "Default")
      (node (ref "U0401") (pin "A10") (pinfunction "IO_L3N_T0_DQS_AD1N_15_A10") (pintype "bidirectional"))
    )
    (net (code "515") (name "unconnected-(U0401C-IO_L3P_T0_DQS_AD1P_15-PadB9)") (class "Default")
      (node (ref "U0401") (pin "B9") (pinfunction "IO_L3P_T0_DQS_AD1P_15_B9") (pintype "bidirectional"))
    )
    (net (code "516") (name "unconnected-(U0401C-IO_L4N_T0_15-PadB11)") (class "Default")
      (node (ref "U0401") (pin "B11") (pinfunction "IO_L4N_T0_15_B11") (pintype "bidirectional"))
    )
    (net (code "517") (name "unconnected-(U0401C-IO_L4P_T0_15-PadB10)") (class "Default")
      (node (ref "U0401") (pin "B10") (pinfunction "IO_L4P_T0_15_B10") (pintype "bidirectional"))
    )
    (net (code "518") (name "unconnected-(U0401C-IO_L5N_T0_AD9N_15-PadA12)") (class "Default")
      (node (ref "U0401") (pin "A12") (pinfunction "IO_L5N_T0_AD9N_15_A12") (pintype "bidirectional"))
    )
    (net (code "519") (name "unconnected-(U0401C-IO_L5P_T0_AD9P_15-PadB12)") (class "Default")
      (node (ref "U0401") (pin "B12") (pinfunction "IO_L5P_T0_AD9P_15_B12") (pintype "bidirectional"))
    )
    (net (code "520") (name "unconnected-(U0401C-IO_L6N_T0_VREF_15-PadD9)") (class "Default")
      (node (ref "U0401") (pin "D9") (pinfunction "IO_L6N_T0_VREF_15_D9") (pintype "bidirectional"))
    )
    (net (code "521") (name "unconnected-(U0401C-IO_L6P_T0_15-PadD8)") (class "Default")
      (node (ref "U0401") (pin "D8") (pinfunction "IO_L6P_T0_15_D8") (pintype "bidirectional"))
    )
    (net (code "522") (name "unconnected-(U0401C-IO_L7N_T1_AD2N_15-PadA14)") (class "Default")
      (node (ref "U0401") (pin "A14") (pinfunction "IO_L7N_T1_AD2N_15_A14") (pintype "bidirectional"))
    )
    (net (code "523") (name "unconnected-(U0401C-IO_L7P_T1_AD2P_15-PadA13)") (class "Default")
      (node (ref "U0401") (pin "A13") (pinfunction "IO_L7P_T1_AD2P_15_A13") (pintype "bidirectional"))
    )
    (net (code "524") (name "unconnected-(U0401C-IO_L8N_T1_AD10N_15-PadB14)") (class "Default")
      (node (ref "U0401") (pin "B14") (pinfunction "IO_L8N_T1_AD10N_15_B14") (pintype "bidirectional"))
    )
    (net (code "525") (name "unconnected-(U0401C-IO_L8P_T1_AD10P_15-PadC14)") (class "Default")
      (node (ref "U0401") (pin "C14") (pinfunction "IO_L8P_T1_AD10P_15_C14") (pintype "bidirectional"))
    )
    (net (code "526") (name "unconnected-(U0401C-IO_L9N_T1_DQS_AD3N_15-PadA15)") (class "Default")
      (node (ref "U0401") (pin "A15") (pinfunction "IO_L9N_T1_DQS_AD3N_15_A15") (pintype "bidirectional"))
    )
    (net (code "527") (name "unconnected-(U0401C-IO_L9P_T1_DQS_AD3P_15-PadB15)") (class "Default")
      (node (ref "U0401") (pin "B15") (pinfunction "IO_L9P_T1_DQS_AD3P_15_B15") (pintype "bidirectional"))
    )
    (net (code "528") (name "unconnected-(U0401C-IO_L10N_T1_AD11N_15-PadB16)") (class "Default")
      (node (ref "U0401") (pin "B16") (pinfunction "IO_L10N_T1_AD11N_15_B16") (pintype "bidirectional"))
    )
    (net (code "529") (name "unconnected-(U0401C-IO_L10P_T1_AD11P_15-PadC16)") (class "Default")
      (node (ref "U0401") (pin "C16") (pinfunction "IO_L10P_T1_AD11P_15_C16") (pintype "bidirectional"))
    )
    (net (code "530") (name "unconnected-(U0401C-IO_L11N_T1_SRCC_15-PadC12)") (class "Default")
      (node (ref "U0401") (pin "C12") (pinfunction "IO_L11N_T1_SRCC_15_C12") (pintype "bidirectional"))
    )
    (net (code "531") (name "unconnected-(U0401C-IO_L11P_T1_SRCC_15-PadC11)") (class "Default")
      (node (ref "U0401") (pin "C11") (pinfunction "IO_L11P_T1_SRCC_15_C11") (pintype "bidirectional"))
    )
    (net (code "532") (name "unconnected-(U0401C-IO_L12N_T1_MRCC_15-PadC13)") (class "Default")
      (node (ref "U0401") (pin "C13") (pinfunction "IO_L12N_T1_MRCC_15_C13") (pintype "bidirectional"))
    )
    (net (code "533") (name "unconnected-(U0401C-IO_L12P_T1_MRCC_15-PadD13)") (class "Default")
      (node (ref "U0401") (pin "D13") (pinfunction "IO_L12P_T1_MRCC_15_D13") (pintype "bidirectional"))
    )
    (net (code "534") (name "unconnected-(U0401C-IO_L13N_T2_MRCC_15-PadE13)") (class "Default")
      (node (ref "U0401") (pin "E13") (pinfunction "IO_L13N_T2_MRCC_15_E13") (pintype "bidirectional"))
    )
    (net (code "535") (name "unconnected-(U0401C-IO_L13P_T2_MRCC_15-PadE12)") (class "Default")
      (node (ref "U0401") (pin "E12") (pinfunction "IO_L13P_T2_MRCC_15_E12") (pintype "bidirectional"))
    )
    (net (code "536") (name "unconnected-(U0401C-IO_L14N_T2_SRCC_15-PadD11)") (class "Default")
      (node (ref "U0401") (pin "D11") (pinfunction "IO_L14N_T2_SRCC_15_D11") (pintype "bidirectional"))
    )
    (net (code "537") (name "unconnected-(U0401C-IO_L14P_T2_SRCC_15-PadE11)") (class "Default")
      (node (ref "U0401") (pin "E11") (pinfunction "IO_L14P_T2_SRCC_15_E11") (pintype "bidirectional"))
    )
    (net (code "538") (name "unconnected-(U0401C-IO_L15N_T2_DQS_ADV_B_15-PadD15)") (class "Default")
      (node (ref "U0401") (pin "D15") (pinfunction "IO_L15N_T2_DQS_ADV_B_15_D15") (pintype "bidirectional"))
    )
    (net (code "539") (name "unconnected-(U0401C-IO_L15P_T2_DQS_15-PadD14)") (class "Default")
      (node (ref "U0401") (pin "D14") (pinfunction "IO_L15P_T2_DQS_15_D14") (pintype "bidirectional"))
    )
    (net (code "540") (name "unconnected-(U0401C-IO_L16N_T2_A27_15-PadF13)") (class "Default")
      (node (ref "U0401") (pin "F13") (pinfunction "IO_L16N_T2_A27_15_F13") (pintype "bidirectional"))
    )
    (net (code "541") (name "unconnected-(U0401C-IO_L16P_T2_A28_15-PadF12)") (class "Default")
      (node (ref "U0401") (pin "F12") (pinfunction "IO_L16P_T2_A28_15_F12") (pintype "bidirectional"))
    )
    (net (code "542") (name "unconnected-(U0401C-IO_L17N_T2_A25_15-PadD16)") (class "Default")
      (node (ref "U0401") (pin "D16") (pinfunction "IO_L17N_T2_A25_15_D16") (pintype "bidirectional"))
    )
    (net (code "543") (name "unconnected-(U0401C-IO_L17P_T2_A26_15-PadE16)") (class "Default")
      (node (ref "U0401") (pin "E16") (pinfunction "IO_L17P_T2_A26_15_E16") (pintype "bidirectional"))
    )
    (net (code "544") (name "unconnected-(U0401C-IO_L18N_T2_A23_15-PadE15)") (class "Default")
      (node (ref "U0401") (pin "E15") (pinfunction "IO_L18N_T2_A23_15_E15") (pintype "bidirectional"))
    )
    (net (code "545") (name "unconnected-(U0401C-IO_L18P_T2_A24_15-PadF15)") (class "Default")
      (node (ref "U0401") (pin "F15") (pinfunction "IO_L18P_T2_A24_15_F15") (pintype "bidirectional"))
    )
    (net (code "546") (name "unconnected-(U0401C-IO_L19N_T3_A21_VREF_15-PadG12)") (class "Default")
      (node (ref "U0401") (pin "G12") (pinfunction "IO_L19N_T3_A21_VREF_15_G12") (pintype "bidirectional"))
    )
    (net (code "547") (name "unconnected-(U0401C-IO_L19P_T3_A22_15-PadH11)") (class "Default")
      (node (ref "U0401") (pin "H11") (pinfunction "IO_L19P_T3_A22_15_H11") (pintype "bidirectional"))
    )
    (net (code "548") (name "unconnected-(U0401C-IO_L20N_T3_A19_15-PadH13)") (class "Default")
      (node (ref "U0401") (pin "H13") (pinfunction "IO_L20N_T3_A19_15_H13") (pintype "bidirectional"))
    )
    (net (code "549") (name "unconnected-(U0401C-IO_L20P_T3_A20_15-PadH12)") (class "Default")
      (node (ref "U0401") (pin "H12") (pinfunction "IO_L20P_T3_A20_15_H12") (pintype "bidirectional"))
    )
    (net (code "550") (name "unconnected-(U0401C-IO_L21N_T3_DQS_A18_15-PadF14)") (class "Default")
      (node (ref "U0401") (pin "F14") (pinfunction "IO_L21N_T3_DQS_A18_15_F14") (pintype "bidirectional"))
    )
    (net (code "551") (name "unconnected-(U0401C-IO_L21P_T3_DQS_15-PadG14)") (class "Default")
      (node (ref "U0401") (pin "G14") (pinfunction "IO_L21P_T3_DQS_15_G14") (pintype "bidirectional"))
    )
    (net (code "552") (name "unconnected-(U0401C-IO_L22N_T3_A16_15-PadG16)") (class "Default")
      (node (ref "U0401") (pin "G16") (pinfunction "IO_L22N_T3_A16_15_G16") (pintype "bidirectional"))
    )
    (net (code "553") (name "unconnected-(U0401C-IO_L22P_T3_A17_15-PadH16)") (class "Default")
      (node (ref "U0401") (pin "H16") (pinfunction "IO_L22P_T3_A17_15_H16") (pintype "bidirectional"))
    )
    (net (code "554") (name "unconnected-(U0401C-IO_L23N_T3_FWE_B_15-PadJ16)") (class "Default")
      (node (ref "U0401") (pin "J16") (pinfunction "IO_L23N_T3_FWE_B_15_J16") (pintype "bidirectional"))
    )
    (net (code "555") (name "unconnected-(U0401C-IO_L23P_T3_FOE_B_15-PadJ15)") (class "Default")
      (node (ref "U0401") (pin "J15") (pinfunction "IO_L23P_T3_FOE_B_15_J15") (pintype "bidirectional"))
    )
  )
)
